# backplane.net
KiCad netlist of a schematic drawn in EAGLE
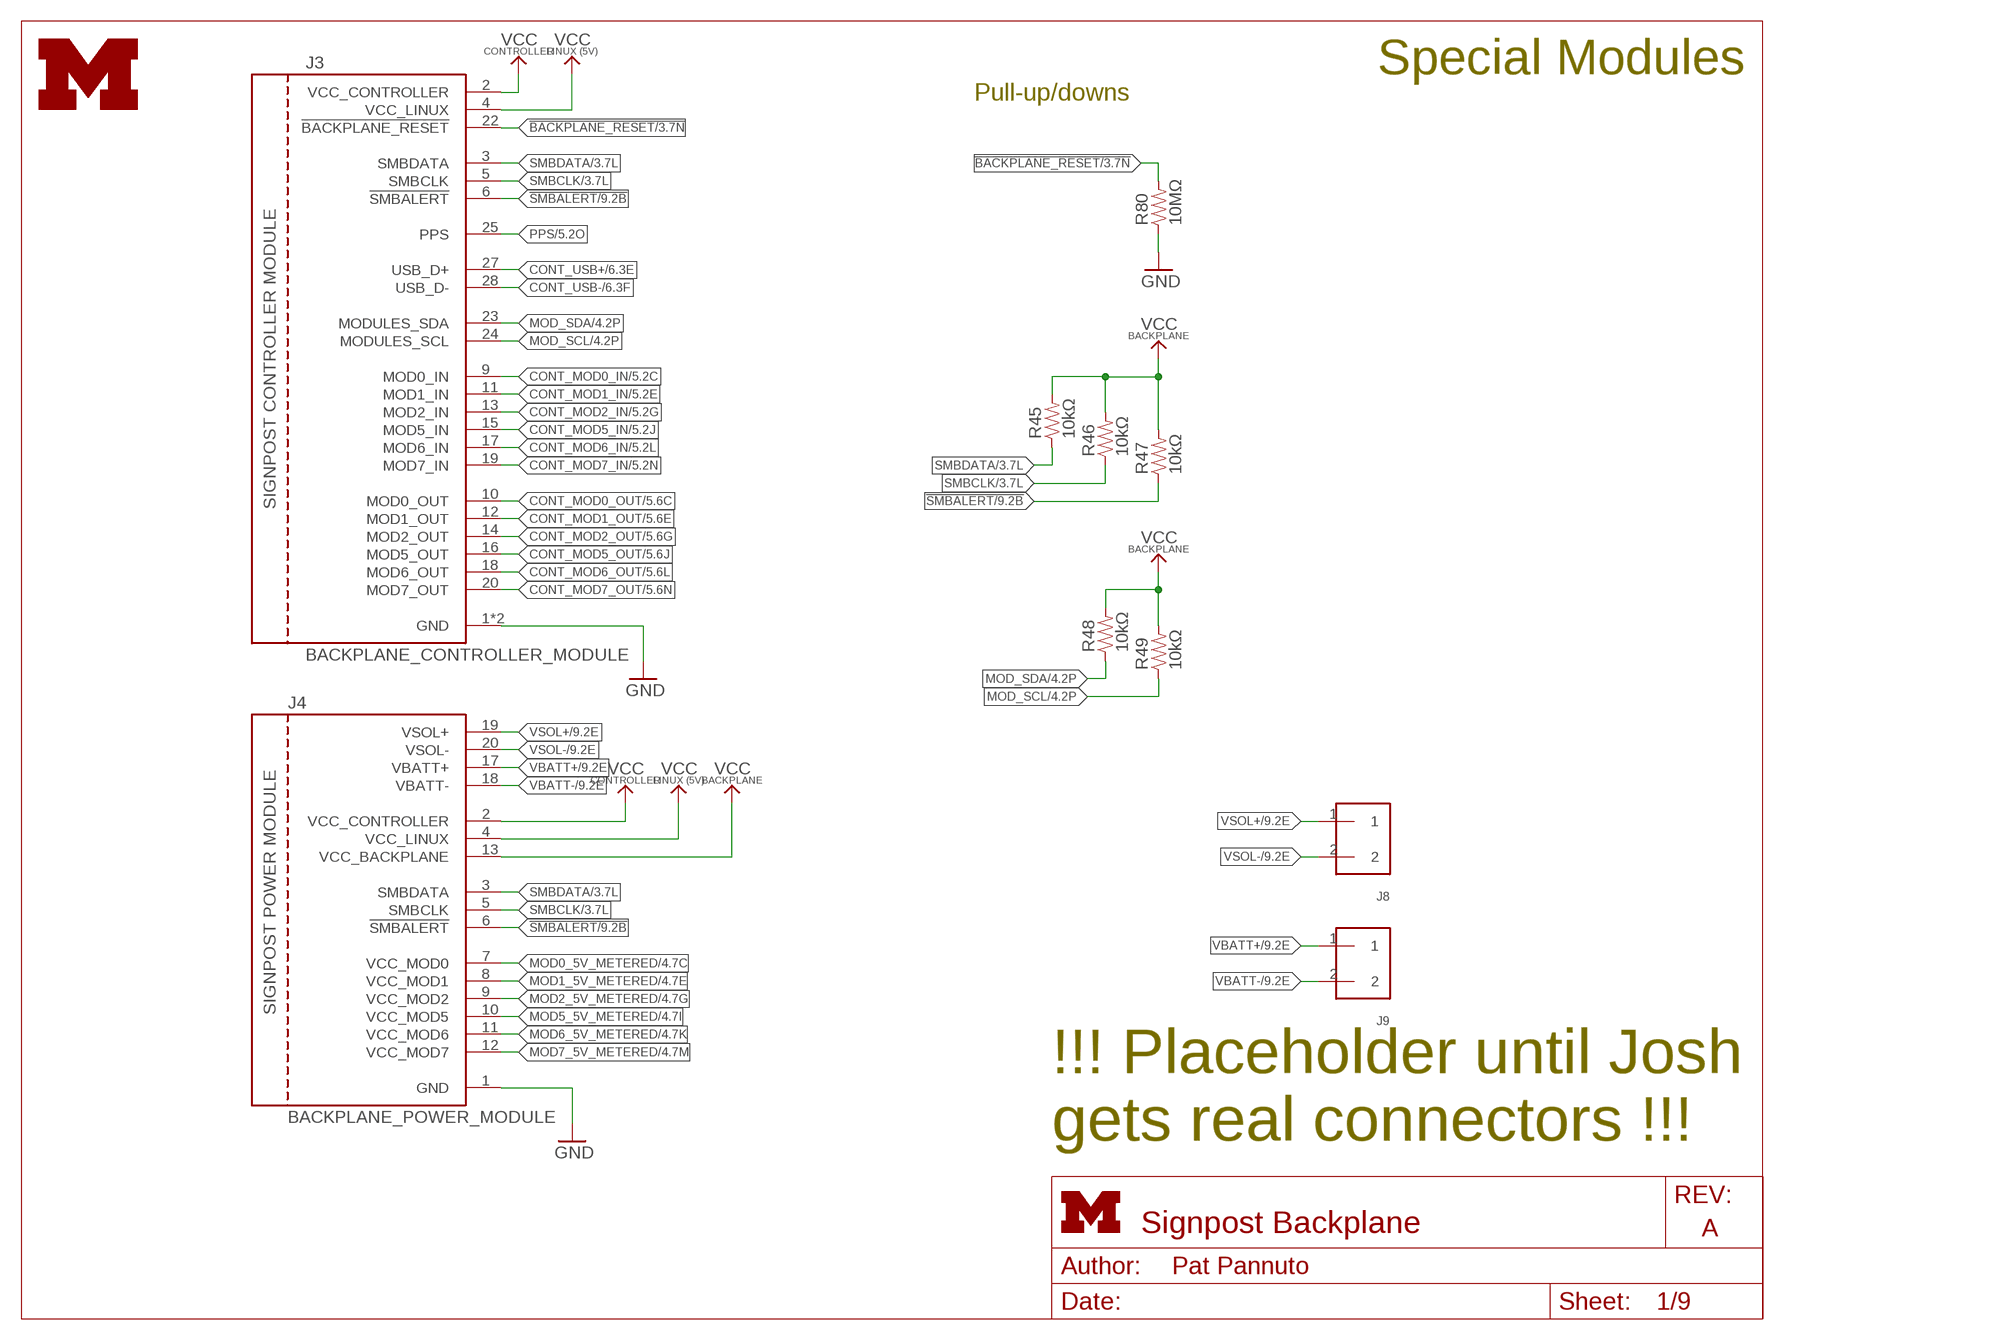
[diagram p0: schematic, sheet 1]
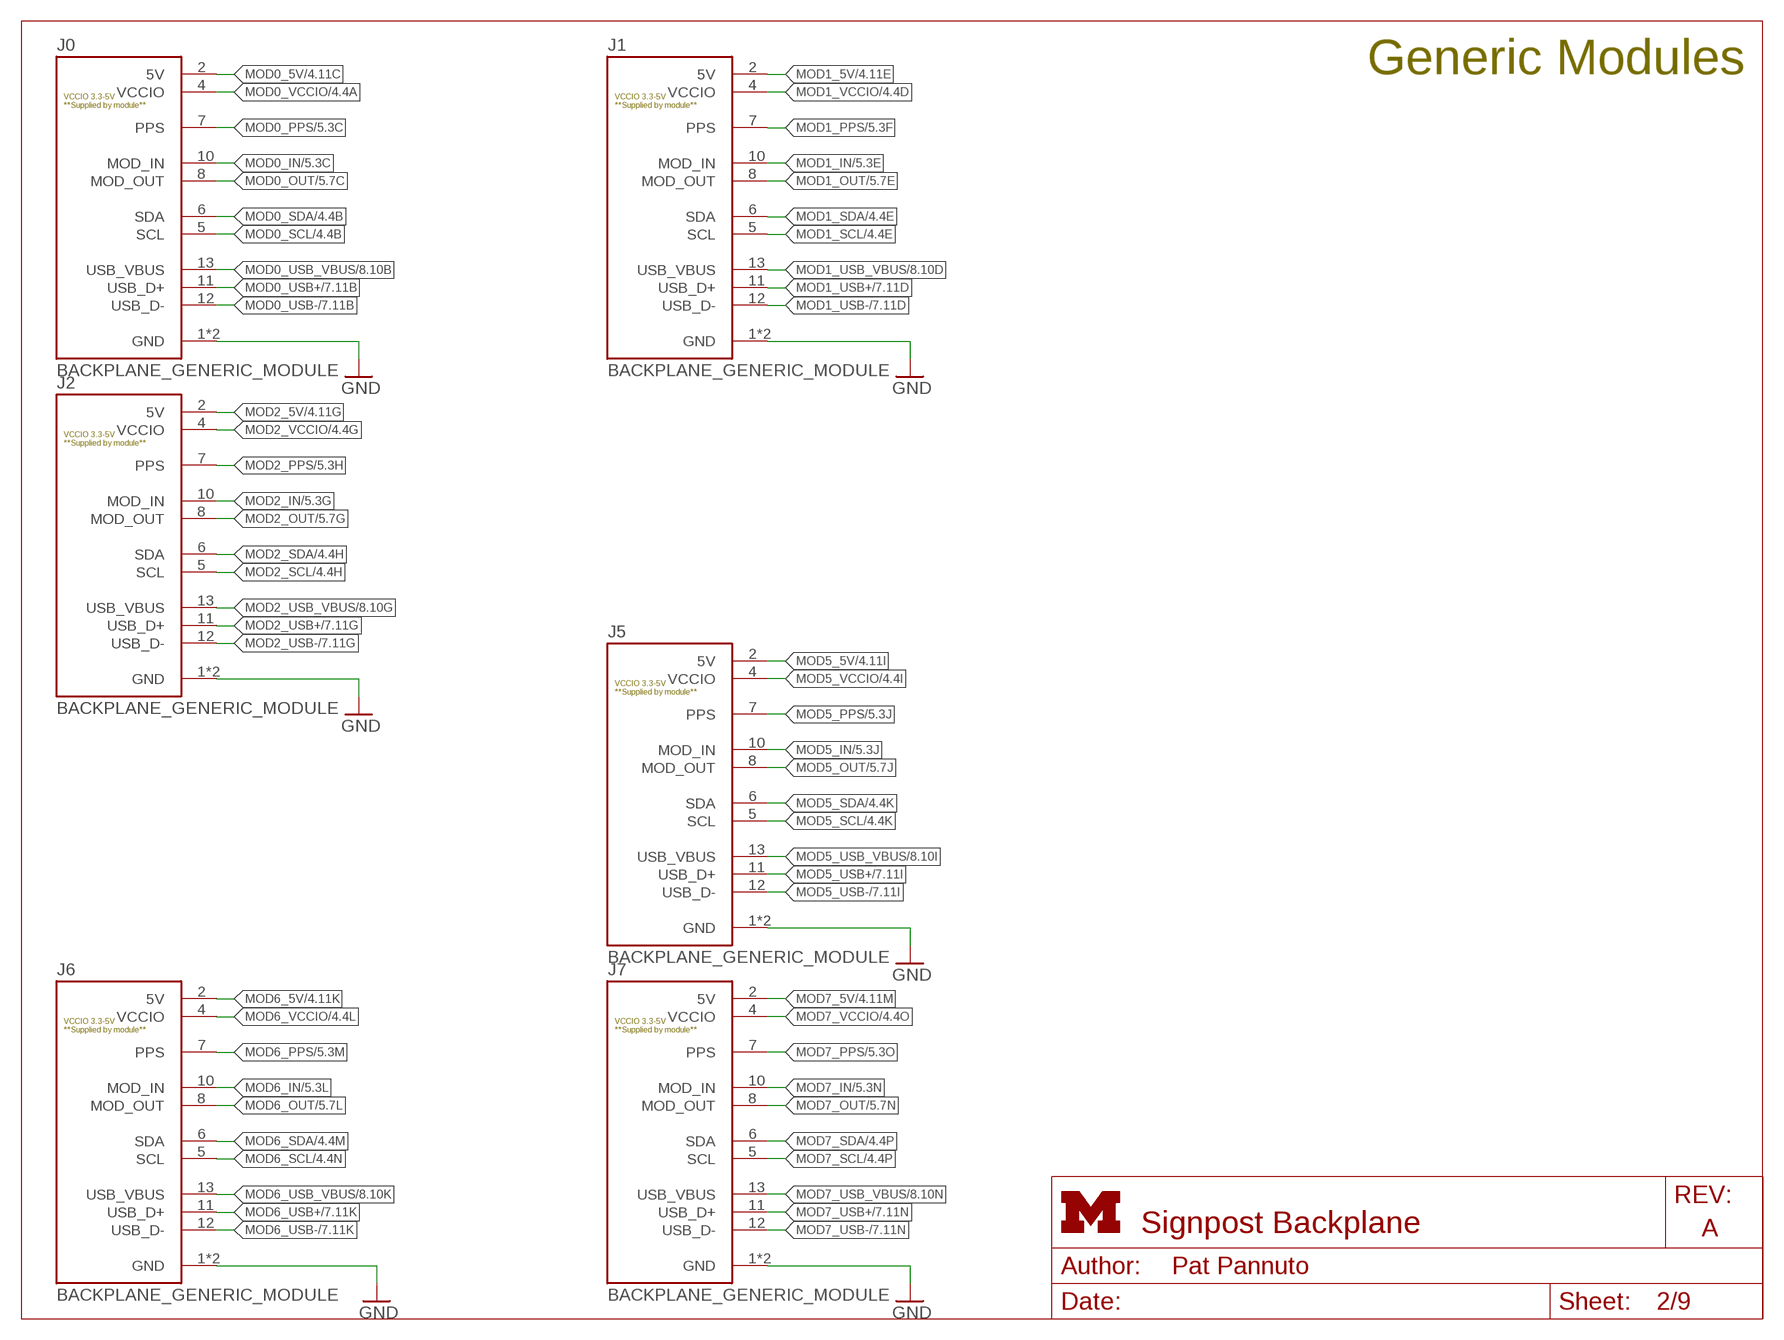
[diagram p1: schematic, sheet 2]
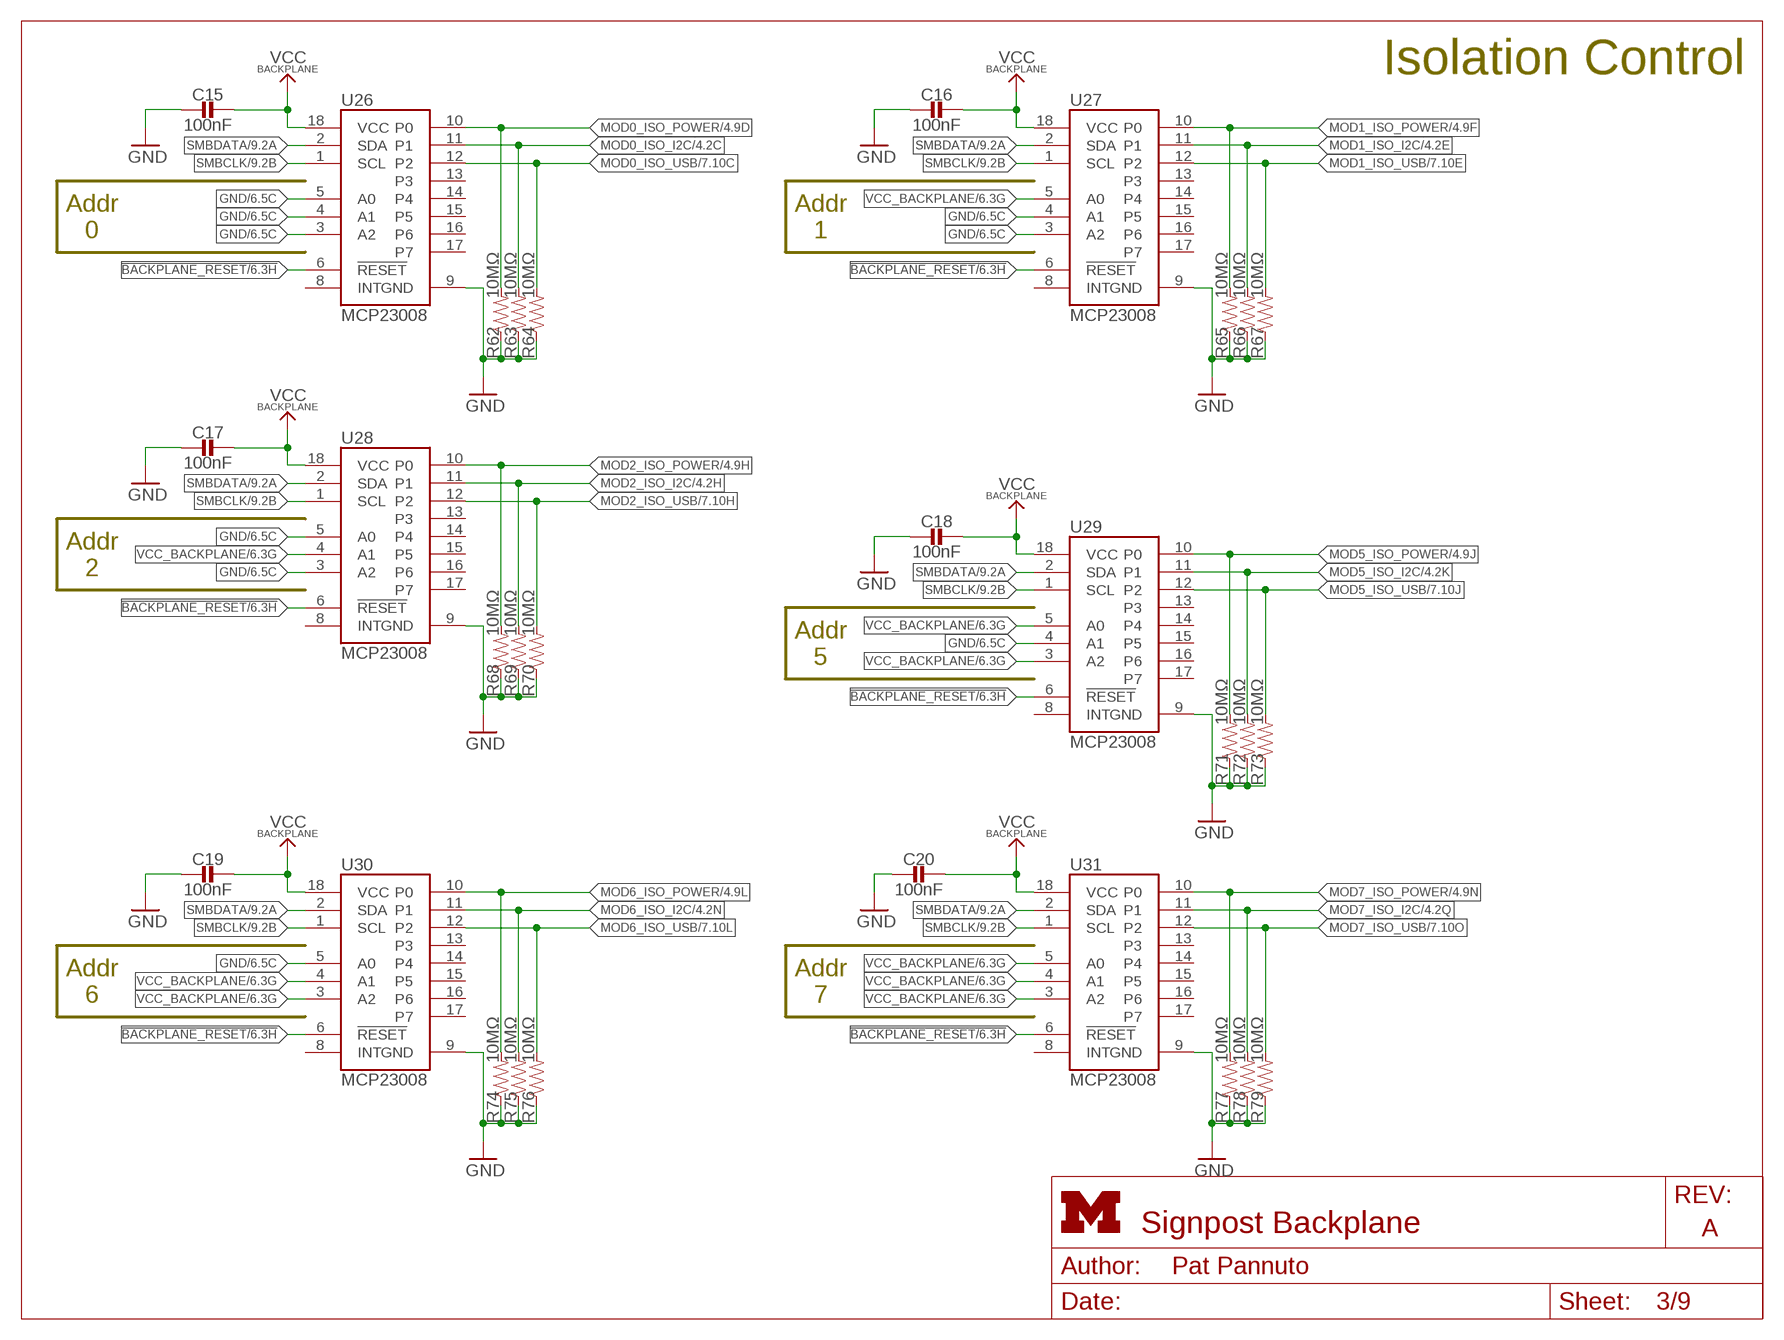
[diagram p2: schematic, sheet 3]
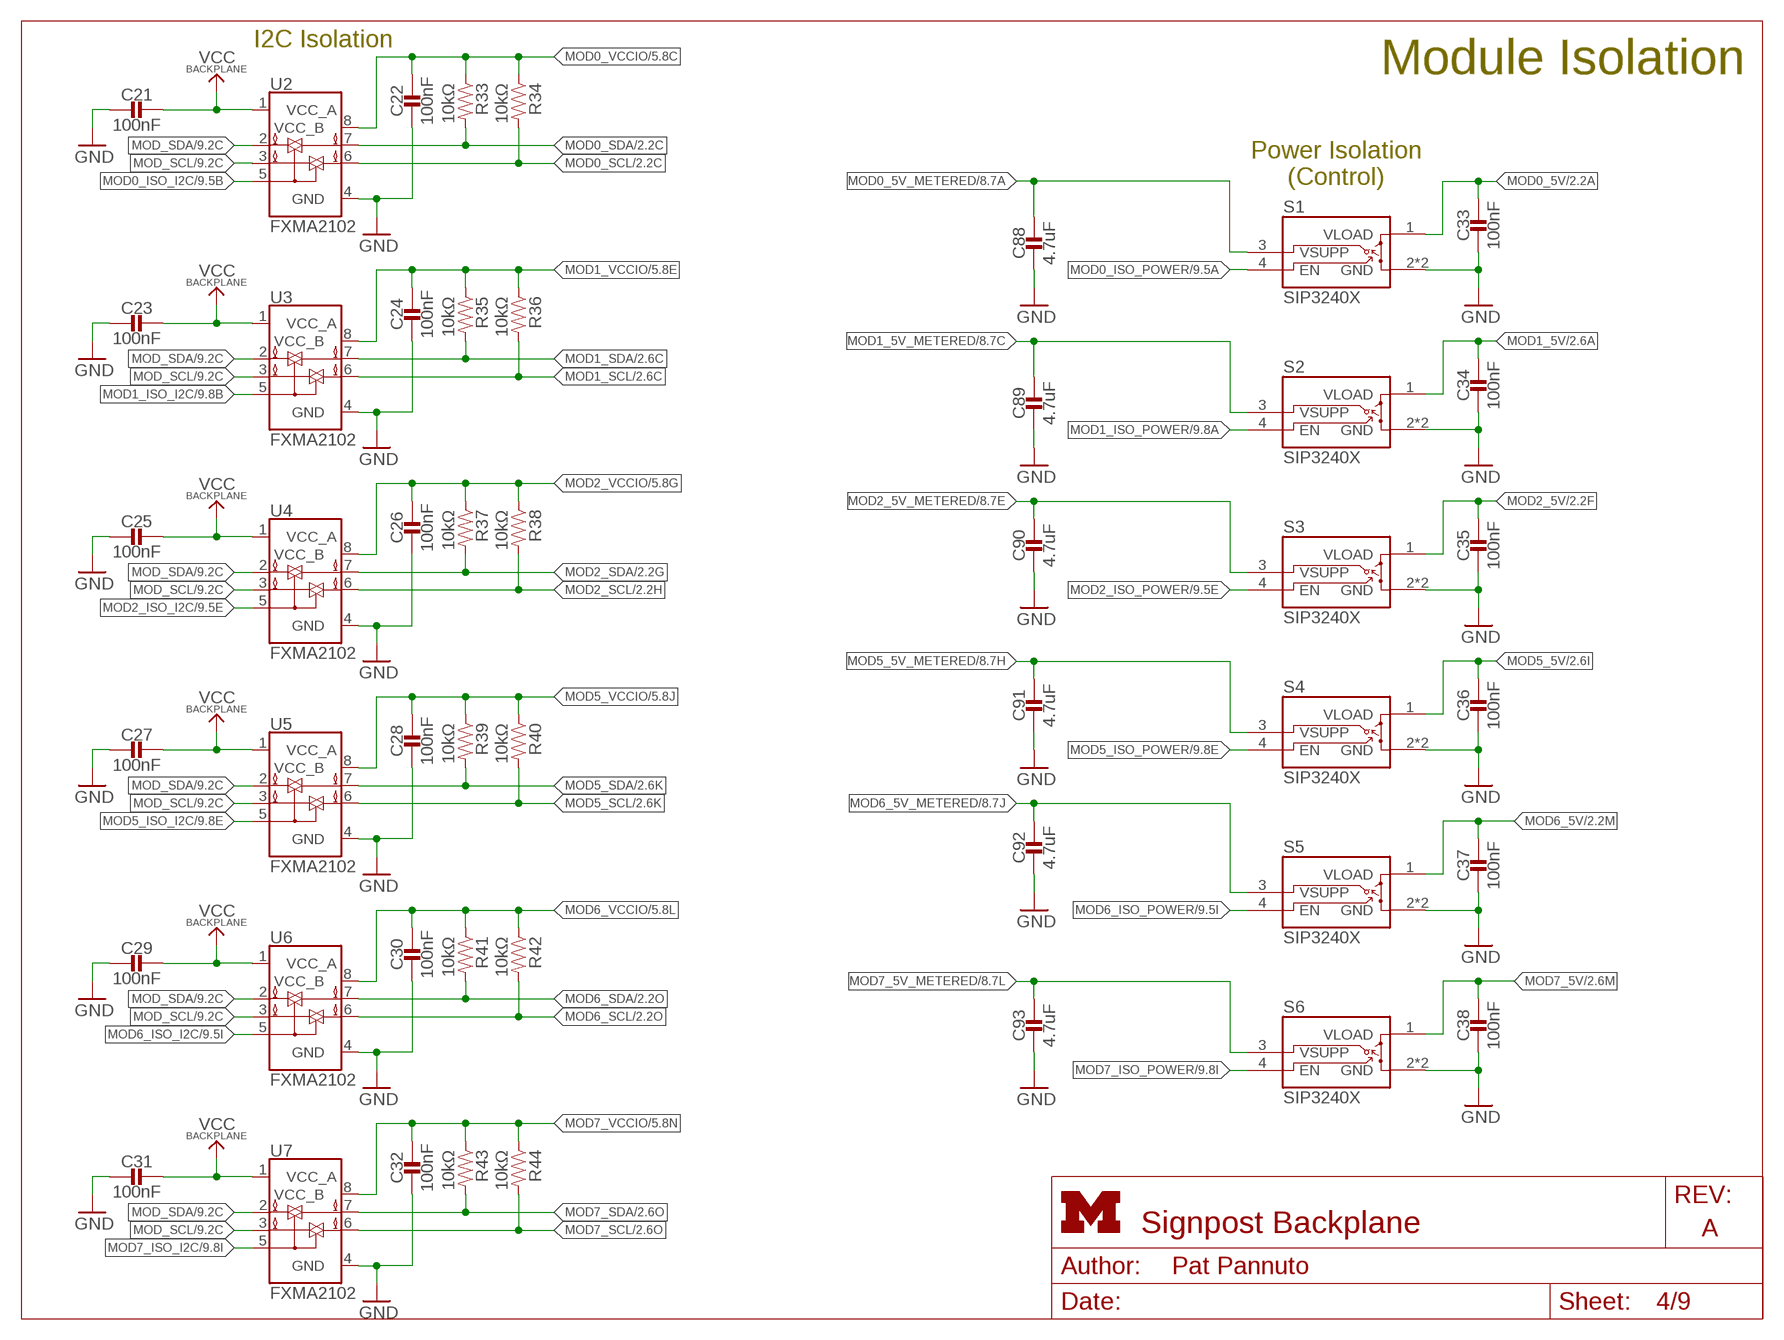
[diagram p3: schematic, sheet 4]
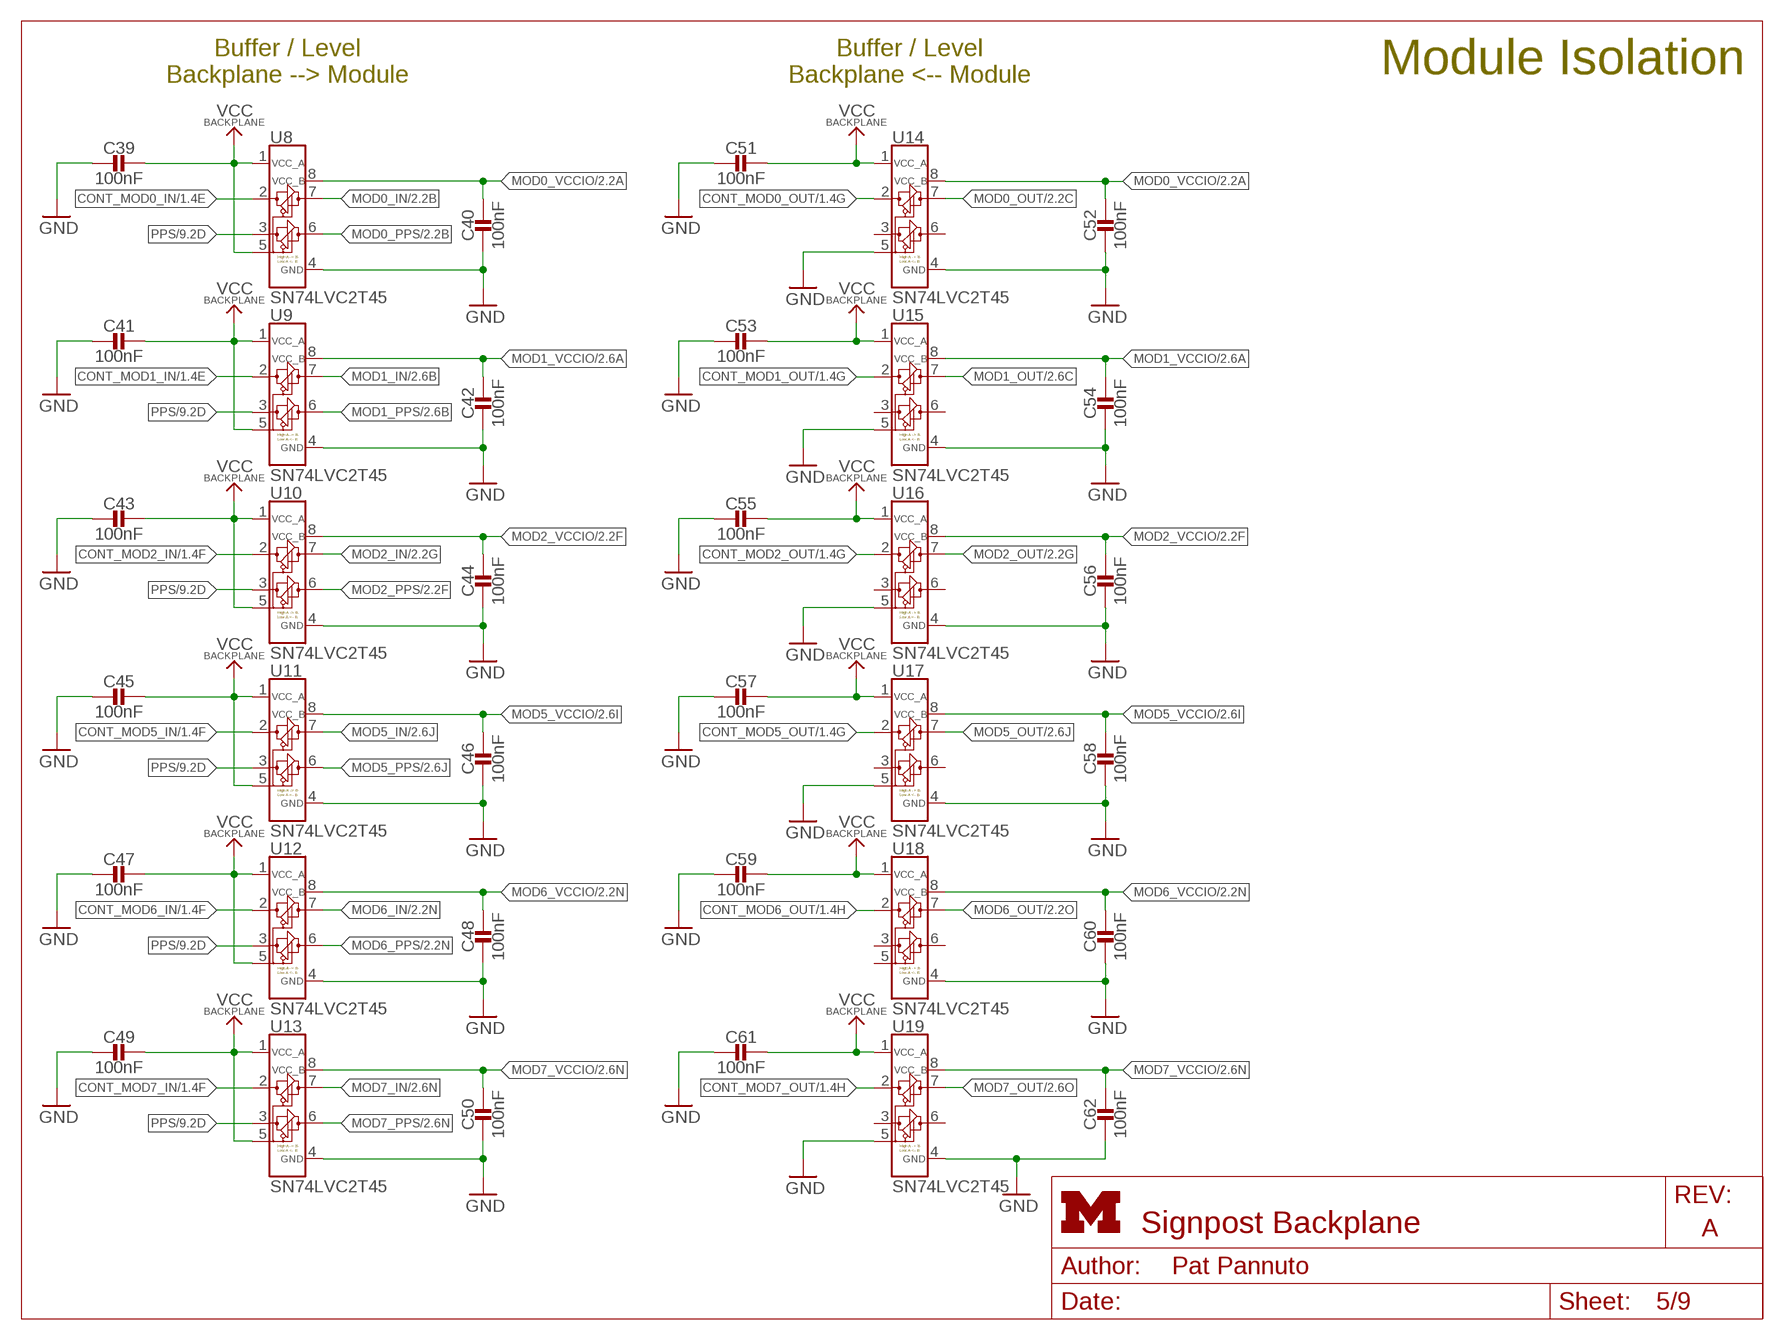
[diagram p4: schematic, sheet 5]
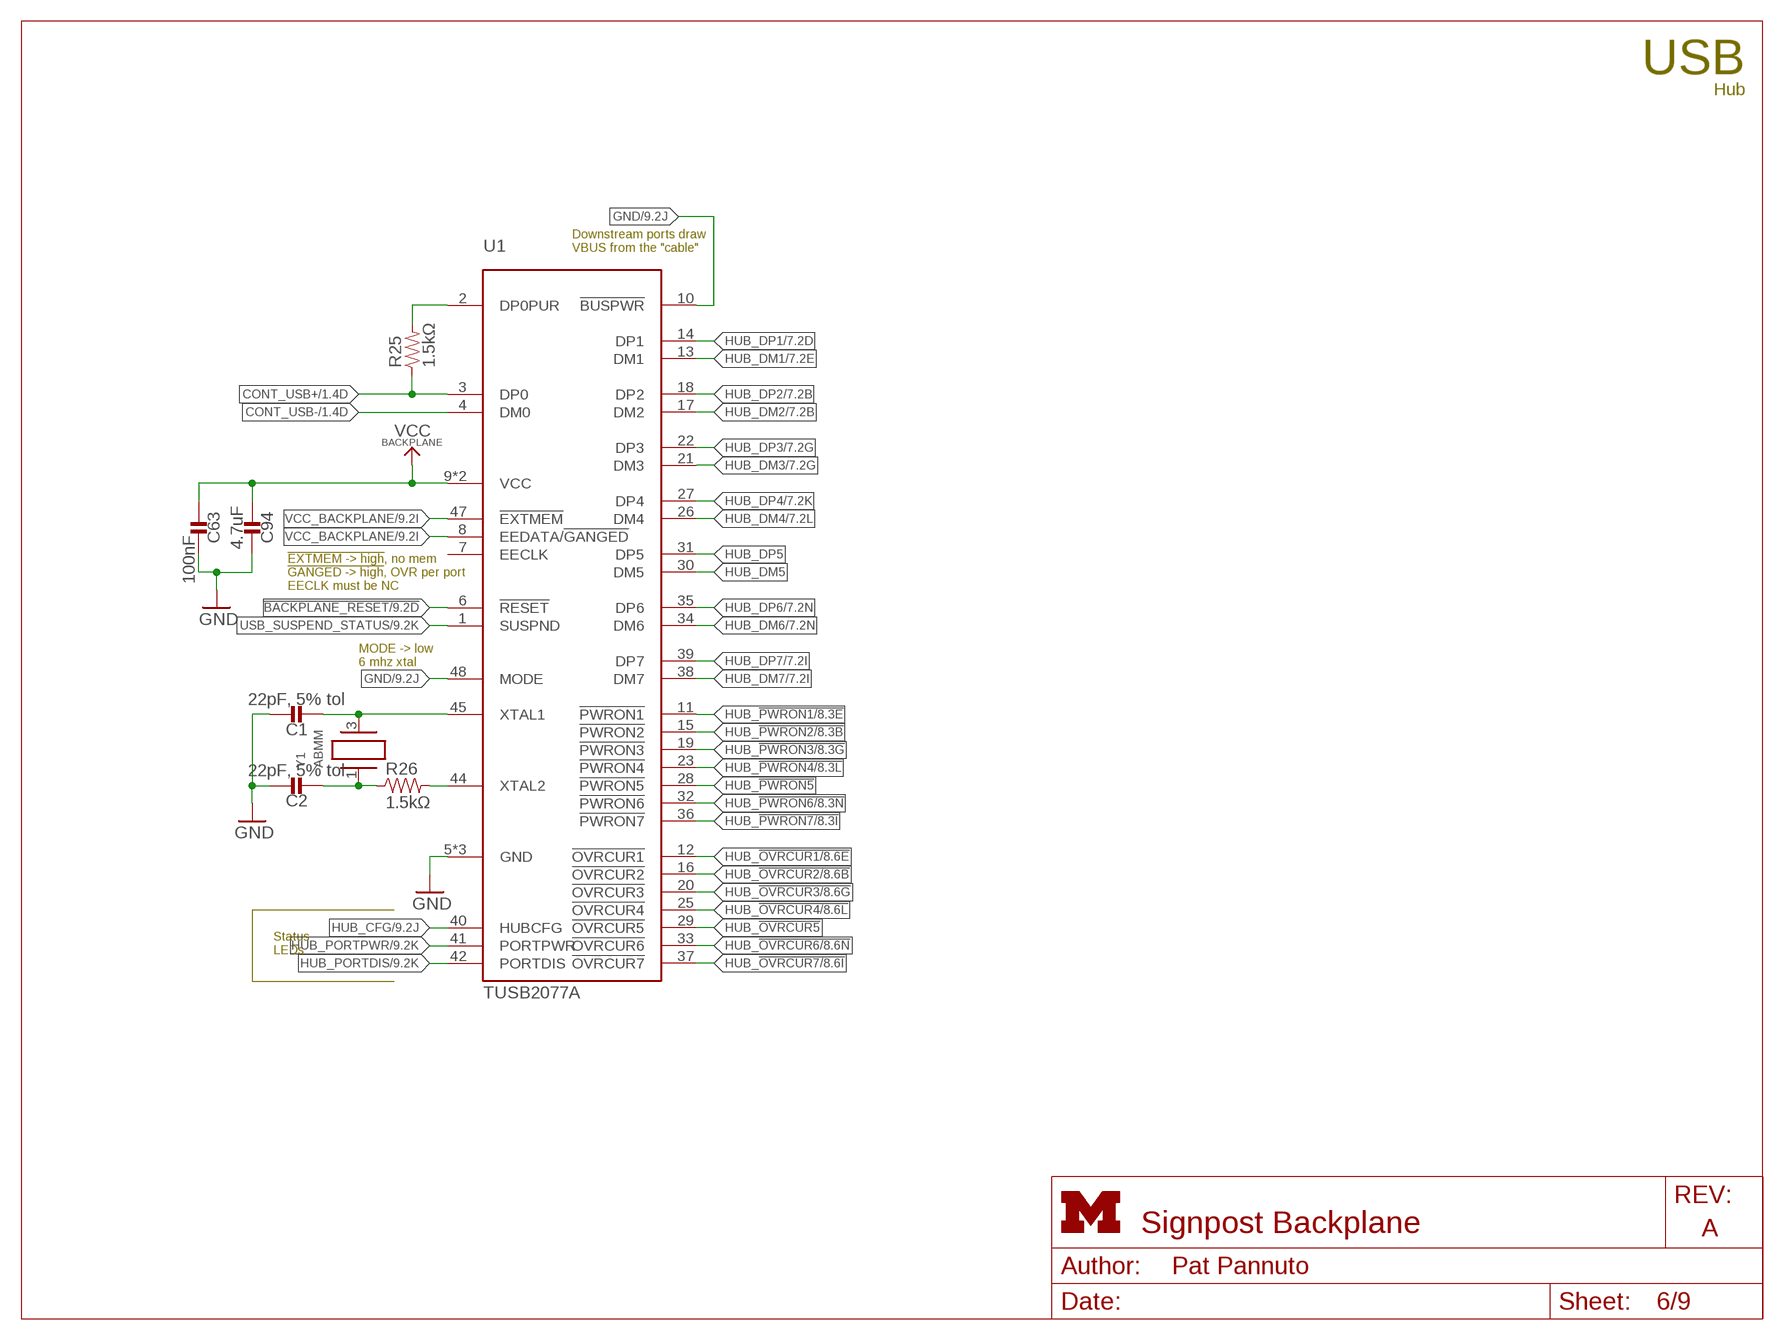
[diagram p5: schematic, sheet 6]
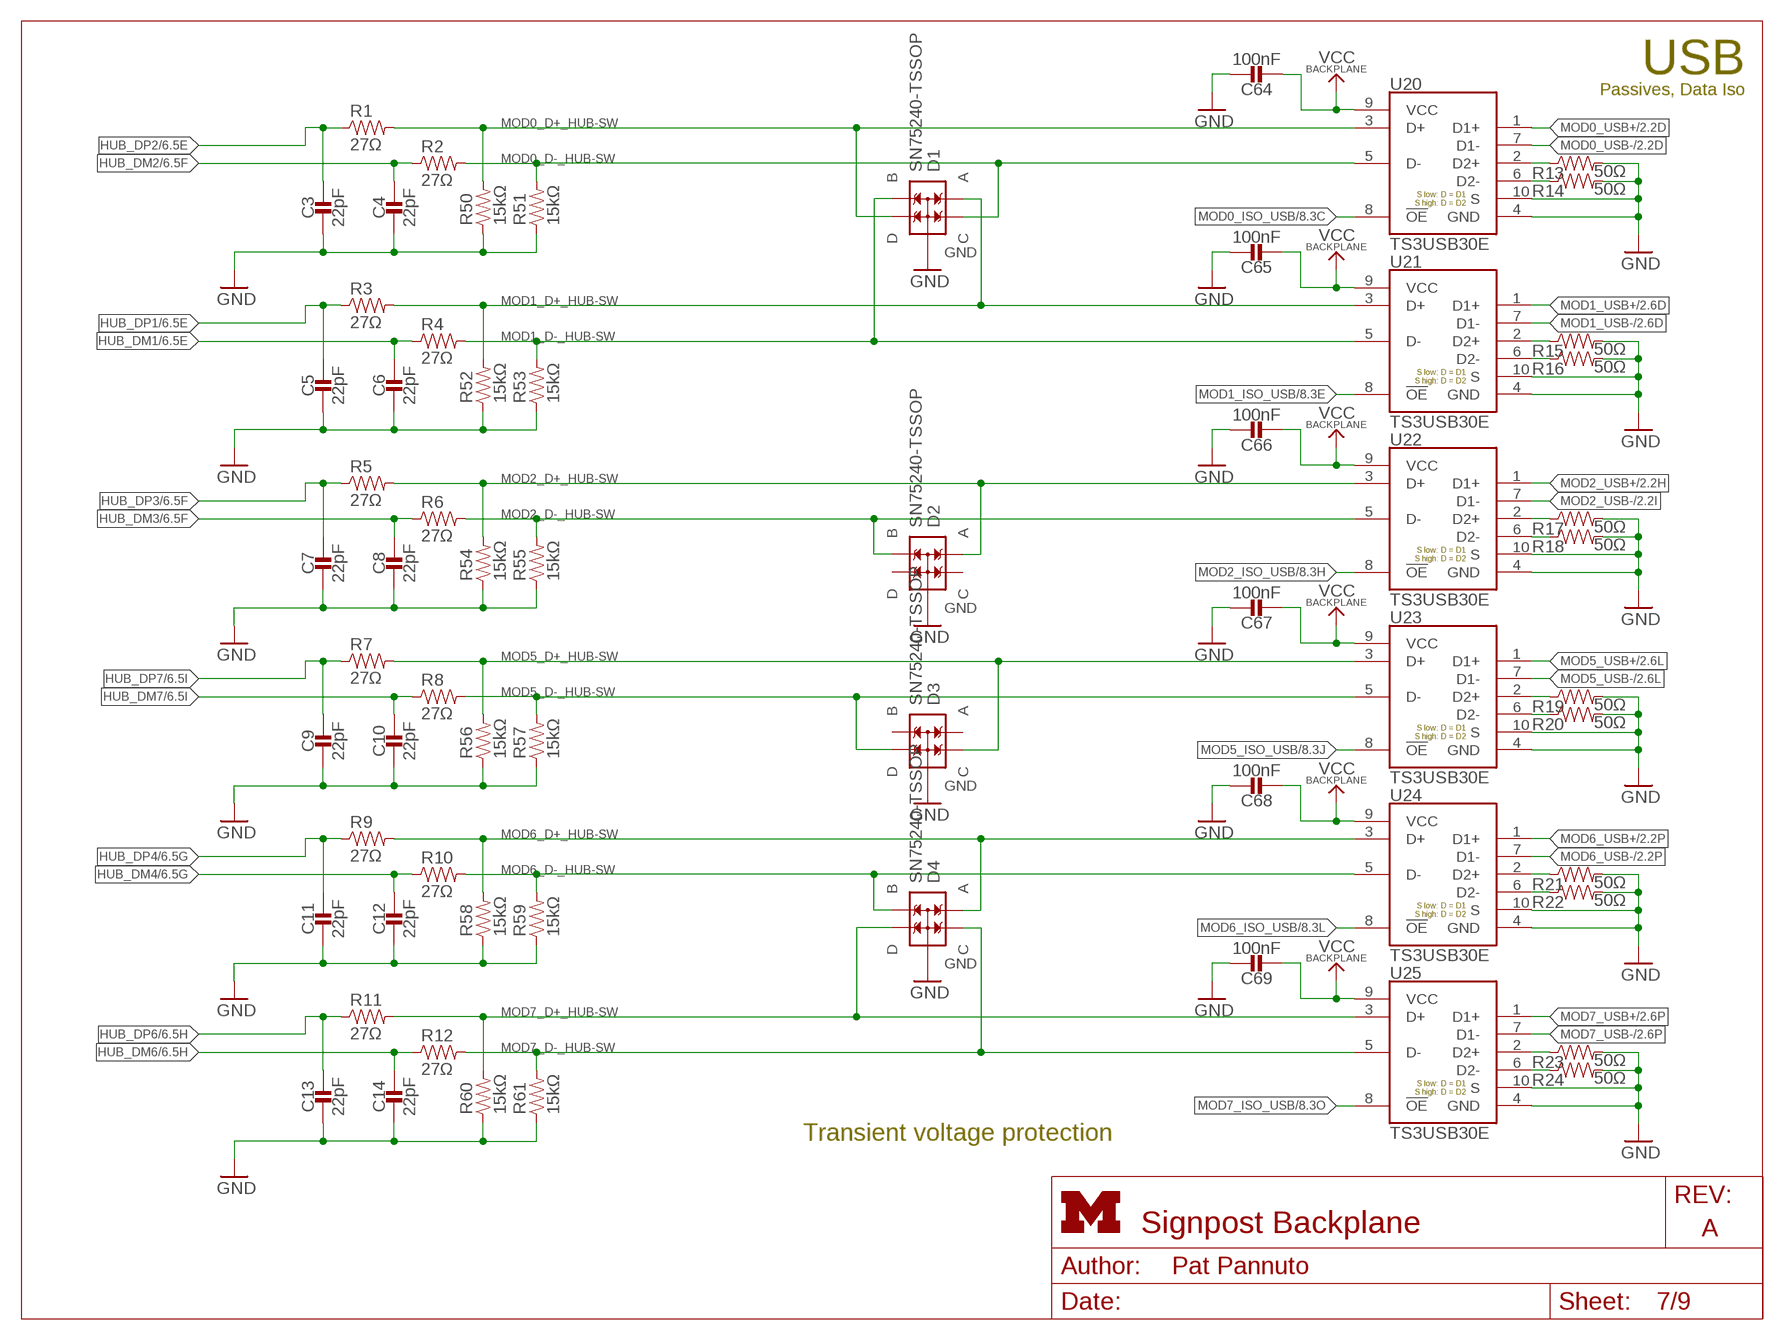
[diagram p6: schematic, sheet 7]
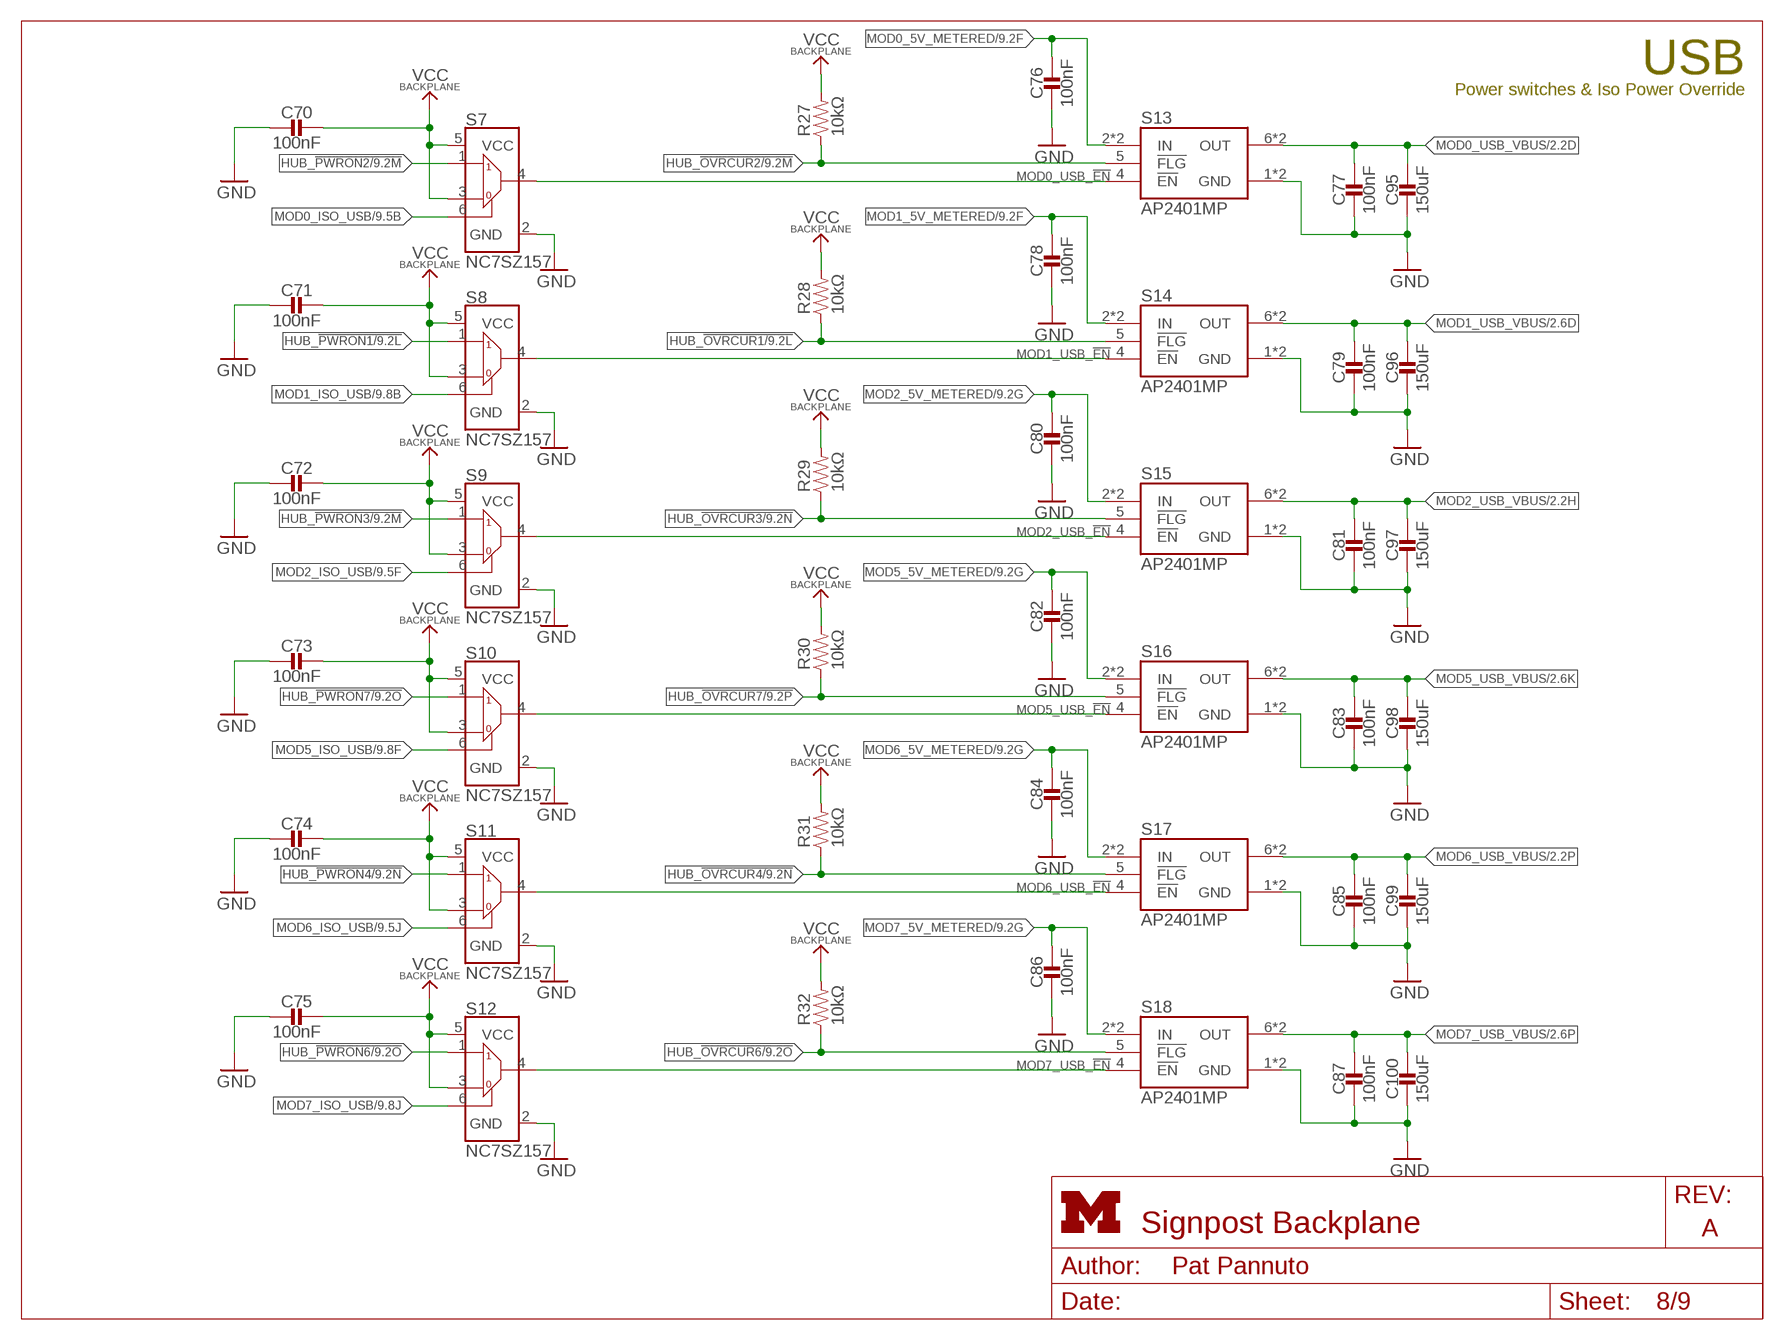
[diagram p7: schematic, sheet 8]
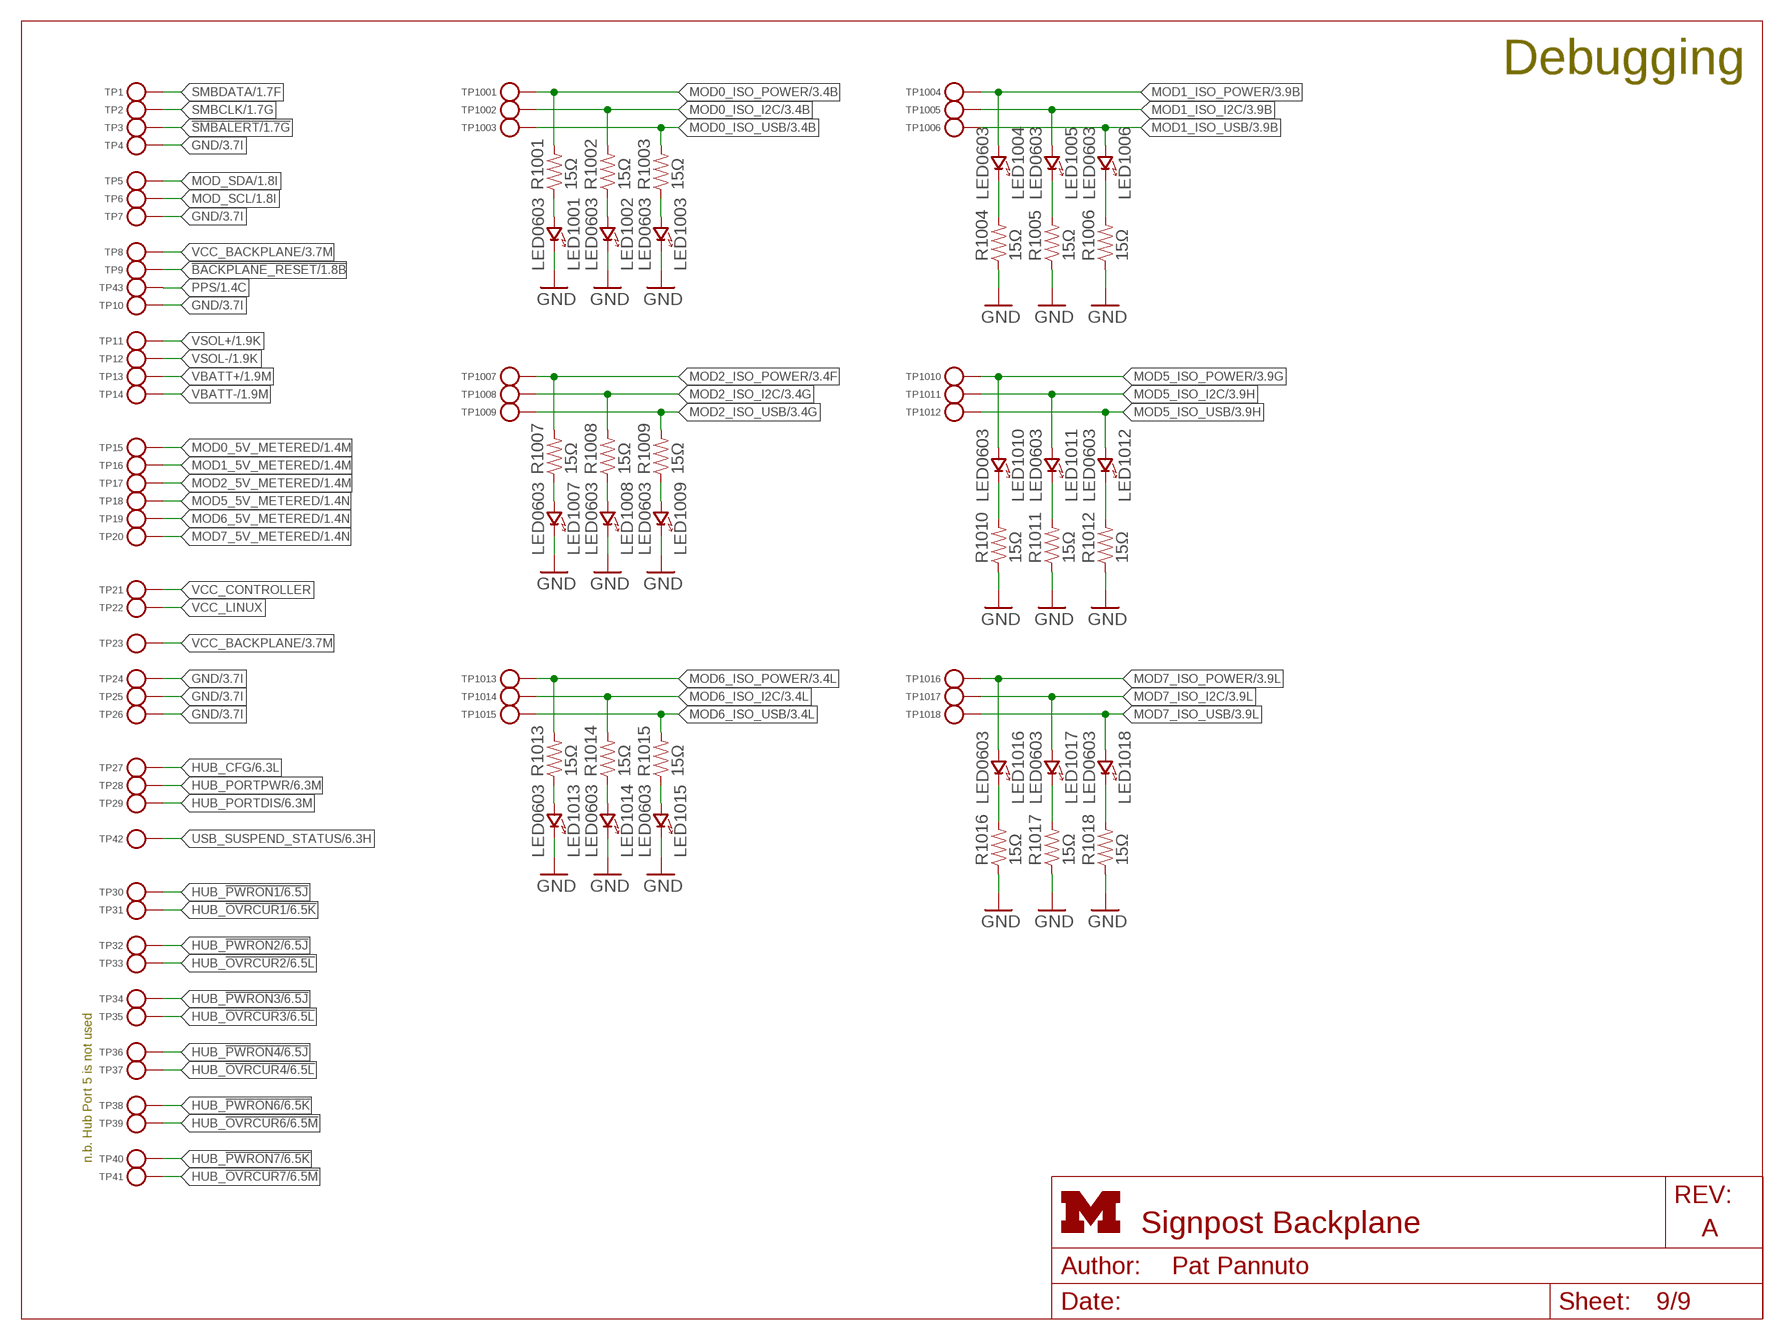
[diagram p8: schematic, sheet 9]

(export (version "E")
  (design (tool "Eeschema 10.0.6"))
  (components
    (comp (ref "C1")
      (value "22pF, 5% tol")
      (footprint "eagle-import:0603_CAP")
      (libsource (lib "eagle-import") (part "CAPACITOR0603_CAP"))
    )
    (comp (ref "C2")
      (value "22pF, 5% tol")
      (footprint "eagle-import:0603_CAP")
      (libsource (lib "eagle-import") (part "CAPACITOR0603_CAP"))
    )
    (comp (ref "C63")
      (value "100nF")
      (footprint "eagle-import:0603_CAP")
      (libsource (lib "eagle-import") (part "CAPACITOR0603_CAP"))
    )
    (comp (ref "C94")
      (value "4.7uF")
      (footprint "eagle-import:0603_CAP")
      (libsource (lib "eagle-import") (part "CAPACITOR0603_CAP"))
    )
    (comp (ref "R25")
      (value "1.5kΩ")
      (footprint "eagle-import:0603-RES")
      (libsource (lib "eagle-import") (part "RESISTOR0603_RES"))
    )
    (comp (ref "R26")
      (value "1.5kΩ")
      (footprint "eagle-import:0603-RES")
      (libsource (lib "eagle-import") (part "RESISTOR0603_RES"))
    )
    (comp (ref "U1")
      (value "TUSB2077A")
      (footprint "eagle-import:LQFP-48")
      (libsource (lib "eagle-import") (part "TUSB2077A"))
    )
    (comp (ref "Y1")
      (value "ABMM")
      (footprint "eagle-import:ABMM")
      (libsource (lib "eagle-import") (part "ABMM"))
    )
    (comp (ref "J0")
      (value "BACKPLANE_GENERIC_MODULE")
      (footprint "eagle-import:BACKPLANE_MODULE_14PIN")
      (libsource (lib "eagle-import") (part "BACKPLANE_GENERIC_MODULE"))
    )
    (comp (ref "J1")
      (value "BACKPLANE_GENERIC_MODULE")
      (footprint "eagle-import:BACKPLANE_MODULE_14PIN")
      (libsource (lib "eagle-import") (part "BACKPLANE_GENERIC_MODULE"))
    )
    (comp (ref "J2")
      (value "BACKPLANE_GENERIC_MODULE")
      (footprint "eagle-import:BACKPLANE_MODULE_14PIN")
      (libsource (lib "eagle-import") (part "BACKPLANE_GENERIC_MODULE"))
    )
    (comp (ref "J5")
      (value "BACKPLANE_GENERIC_MODULE")
      (footprint "eagle-import:BACKPLANE_MODULE_14PIN")
      (libsource (lib "eagle-import") (part "BACKPLANE_GENERIC_MODULE"))
    )
    (comp (ref "J6")
      (value "BACKPLANE_GENERIC_MODULE")
      (footprint "eagle-import:BACKPLANE_MODULE_14PIN")
      (libsource (lib "eagle-import") (part "BACKPLANE_GENERIC_MODULE"))
    )
    (comp (ref "J7")
      (value "BACKPLANE_GENERIC_MODULE")
      (footprint "eagle-import:BACKPLANE_MODULE_14PIN")
      (libsource (lib "eagle-import") (part "BACKPLANE_GENERIC_MODULE"))
    )
    (comp (ref "C15")
      (value "100nF")
      (footprint "eagle-import:0603_CAP")
      (libsource (lib "eagle-import") (part "CAPACITOR0603_CAP"))
    )
    (comp (ref "C16")
      (value "100nF")
      (footprint "eagle-import:0603_CAP")
      (libsource (lib "eagle-import") (part "CAPACITOR0603_CAP"))
    )
    (comp (ref "C17")
      (value "100nF")
      (footprint "eagle-import:0603_CAP")
      (libsource (lib "eagle-import") (part "CAPACITOR0603_CAP"))
    )
    (comp (ref "C18")
      (value "100nF")
      (footprint "eagle-import:0603_CAP")
      (libsource (lib "eagle-import") (part "CAPACITOR0603_CAP"))
    )
    (comp (ref "C19")
      (value "100nF")
      (footprint "eagle-import:0603_CAP")
      (libsource (lib "eagle-import") (part "CAPACITOR0603_CAP"))
    )
    (comp (ref "C20")
      (value "100nF")
      (footprint "eagle-import:0603_CAP")
      (libsource (lib "eagle-import") (part "CAPACITOR0603_CAP"))
    )
    (comp (ref "R62")
      (value "10MΩ")
      (footprint "eagle-import:0603-RES")
      (libsource (lib "eagle-import") (part "RESISTOR0603_RES"))
    )
    (comp (ref "R63")
      (value "10MΩ")
      (footprint "eagle-import:0603-RES")
      (libsource (lib "eagle-import") (part "RESISTOR0603_RES"))
    )
    (comp (ref "R64")
      (value "10MΩ")
      (footprint "eagle-import:0603-RES")
      (libsource (lib "eagle-import") (part "RESISTOR0603_RES"))
    )
    (comp (ref "R65")
      (value "10MΩ")
      (footprint "eagle-import:0603-RES")
      (libsource (lib "eagle-import") (part "RESISTOR0603_RES"))
    )
    (comp (ref "R66")
      (value "10MΩ")
      (footprint "eagle-import:0603-RES")
      (libsource (lib "eagle-import") (part "RESISTOR0603_RES"))
    )
    (comp (ref "R67")
      (value "10MΩ")
      (footprint "eagle-import:0603-RES")
      (libsource (lib "eagle-import") (part "RESISTOR0603_RES"))
    )
    (comp (ref "R68")
      (value "10MΩ")
      (footprint "eagle-import:0603-RES")
      (libsource (lib "eagle-import") (part "RESISTOR0603_RES"))
    )
    (comp (ref "R69")
      (value "10MΩ")
      (footprint "eagle-import:0603-RES")
      (libsource (lib "eagle-import") (part "RESISTOR0603_RES"))
    )
    (comp (ref "R70")
      (value "10MΩ")
      (footprint "eagle-import:0603-RES")
      (libsource (lib "eagle-import") (part "RESISTOR0603_RES"))
    )
    (comp (ref "R71")
      (value "10MΩ")
      (footprint "eagle-import:0603-RES")
      (libsource (lib "eagle-import") (part "RESISTOR0603_RES"))
    )
    (comp (ref "R72")
      (value "10MΩ")
      (footprint "eagle-import:0603-RES")
      (libsource (lib "eagle-import") (part "RESISTOR0603_RES"))
    )
    (comp (ref "R73")
      (value "10MΩ")
      (footprint "eagle-import:0603-RES")
      (libsource (lib "eagle-import") (part "RESISTOR0603_RES"))
    )
    (comp (ref "R74")
      (value "10MΩ")
      (footprint "eagle-import:0603-RES")
      (libsource (lib "eagle-import") (part "RESISTOR0603_RES"))
    )
    (comp (ref "R75")
      (value "10MΩ")
      (footprint "eagle-import:0603-RES")
      (libsource (lib "eagle-import") (part "RESISTOR0603_RES"))
    )
    (comp (ref "R76")
      (value "10MΩ")
      (footprint "eagle-import:0603-RES")
      (libsource (lib "eagle-import") (part "RESISTOR0603_RES"))
    )
    (comp (ref "R77")
      (value "10MΩ")
      (footprint "eagle-import:0603-RES")
      (libsource (lib "eagle-import") (part "RESISTOR0603_RES"))
    )
    (comp (ref "R78")
      (value "10MΩ")
      (footprint "eagle-import:0603-RES")
      (libsource (lib "eagle-import") (part "RESISTOR0603_RES"))
    )
    (comp (ref "R79")
      (value "10MΩ")
      (footprint "eagle-import:0603-RES")
      (libsource (lib "eagle-import") (part "RESISTOR0603_RES"))
    )
    (comp (ref "U26")
      (value "MCP23008")
      (footprint "eagle-import:SOIC-18")
      (libsource (lib "eagle-import") (part "MCP23008"))
    )
    (comp (ref "U27")
      (value "MCP23008")
      (footprint "eagle-import:SOIC-18")
      (libsource (lib "eagle-import") (part "MCP23008"))
    )
    (comp (ref "U28")
      (value "MCP23008")
      (footprint "eagle-import:SOIC-18")
      (libsource (lib "eagle-import") (part "MCP23008"))
    )
    (comp (ref "U29")
      (value "MCP23008")
      (footprint "eagle-import:SOIC-18")
      (libsource (lib "eagle-import") (part "MCP23008"))
    )
    (comp (ref "U30")
      (value "MCP23008")
      (footprint "eagle-import:SOIC-18")
      (libsource (lib "eagle-import") (part "MCP23008"))
    )
    (comp (ref "U31")
      (value "MCP23008")
      (footprint "eagle-import:SOIC-18")
      (libsource (lib "eagle-import") (part "MCP23008"))
    )
    (comp (ref "J3")
      (value "BACKPLANE_CONTROLLER_MODULE")
      (footprint "eagle-import:BACKPLANE_MODULE_20PIN_10PIN")
      (libsource (lib "eagle-import") (part "BACKPLANE_CONTROLLER_MODULE"))
    )
    (comp (ref "J4")
      (value "BACKPLANE_POWER_MODULE")
      (footprint "eagle-import:BACKPLANE_MODULE_20PIN")
      (libsource (lib "eagle-import") (part "BACKPLANE_POWER_MODULE"))
    )
    (comp (ref "J8")
      (value "SCREW_TERMINAL")
      (footprint "eagle-import:PHEONIX-1935161")
      (libsource (lib "eagle-import") (part "SCREW_TERMINAL"))
    )
    (comp (ref "J9")
      (value "SCREW_TERMINAL")
      (footprint "eagle-import:PHEONIX-1935161")
      (libsource (lib "eagle-import") (part "SCREW_TERMINAL"))
    )
    (comp (ref "LOGO1")
      (value "UMICH_SOLID_GIANT")
      (footprint "eagle-import:UMICH_SOLID_1000MIL")
      (libsource (lib "eagle-import") (part "UMICH_SOLID_GIANT"))
    )
    (comp (ref "R45")
      (value "10kΩ")
      (footprint "eagle-import:0603-RES")
      (libsource (lib "eagle-import") (part "RESISTOR0603_RES"))
    )
    (comp (ref "R46")
      (value "10kΩ")
      (footprint "eagle-import:0603-RES")
      (libsource (lib "eagle-import") (part "RESISTOR0603_RES"))
    )
    (comp (ref "R47")
      (value "10kΩ")
      (footprint "eagle-import:0603-RES")
      (libsource (lib "eagle-import") (part "RESISTOR0603_RES"))
    )
    (comp (ref "R48")
      (value "10kΩ")
      (footprint "eagle-import:0603-RES")
      (libsource (lib "eagle-import") (part "RESISTOR0603_RES"))
    )
    (comp (ref "R49")
      (value "10kΩ")
      (footprint "eagle-import:0603-RES")
      (libsource (lib "eagle-import") (part "RESISTOR0603_RES"))
    )
    (comp (ref "R80")
      (value "10MΩ")
      (footprint "eagle-import:0603-RES")
      (libsource (lib "eagle-import") (part "RESISTOR0603_RES"))
    )
    (comp (ref "C21")
      (value "100nF")
      (footprint "eagle-import:0603_CAP")
      (libsource (lib "eagle-import") (part "CAPACITOR0603_CAP"))
    )
    (comp (ref "C22")
      (value "100nF")
      (footprint "eagle-import:0603_CAP")
      (libsource (lib "eagle-import") (part "CAPACITOR0603_CAP"))
    )
    (comp (ref "C23")
      (value "100nF")
      (footprint "eagle-import:0603_CAP")
      (libsource (lib "eagle-import") (part "CAPACITOR0603_CAP"))
    )
    (comp (ref "C24")
      (value "100nF")
      (footprint "eagle-import:0603_CAP")
      (libsource (lib "eagle-import") (part "CAPACITOR0603_CAP"))
    )
    (comp (ref "C25")
      (value "100nF")
      (footprint "eagle-import:0603_CAP")
      (libsource (lib "eagle-import") (part "CAPACITOR0603_CAP"))
    )
    (comp (ref "C26")
      (value "100nF")
      (footprint "eagle-import:0603_CAP")
      (libsource (lib "eagle-import") (part "CAPACITOR0603_CAP"))
    )
    (comp (ref "C27")
      (value "100nF")
      (footprint "eagle-import:0603_CAP")
      (libsource (lib "eagle-import") (part "CAPACITOR0603_CAP"))
    )
    (comp (ref "C28")
      (value "100nF")
      (footprint "eagle-import:0603_CAP")
      (libsource (lib "eagle-import") (part "CAPACITOR0603_CAP"))
    )
    (comp (ref "C29")
      (value "100nF")
      (footprint "eagle-import:0603_CAP")
      (libsource (lib "eagle-import") (part "CAPACITOR0603_CAP"))
    )
    (comp (ref "C30")
      (value "100nF")
      (footprint "eagle-import:0603_CAP")
      (libsource (lib "eagle-import") (part "CAPACITOR0603_CAP"))
    )
    (comp (ref "C31")
      (value "100nF")
      (footprint "eagle-import:0603_CAP")
      (libsource (lib "eagle-import") (part "CAPACITOR0603_CAP"))
    )
    (comp (ref "C32")
      (value "100nF")
      (footprint "eagle-import:0603_CAP")
      (libsource (lib "eagle-import") (part "CAPACITOR0603_CAP"))
    )
    (comp (ref "C33")
      (value "100nF")
      (footprint "eagle-import:0603_CAP")
      (libsource (lib "eagle-import") (part "CAPACITOR0603_CAP"))
    )
    (comp (ref "C34")
      (value "100nF")
      (footprint "eagle-import:0603_CAP")
      (libsource (lib "eagle-import") (part "CAPACITOR0603_CAP"))
    )
    (comp (ref "C35")
      (value "100nF")
      (footprint "eagle-import:0603_CAP")
      (libsource (lib "eagle-import") (part "CAPACITOR0603_CAP"))
    )
    (comp (ref "C36")
      (value "100nF")
      (footprint "eagle-import:0603_CAP")
      (libsource (lib "eagle-import") (part "CAPACITOR0603_CAP"))
    )
    (comp (ref "C37")
      (value "100nF")
      (footprint "eagle-import:0603_CAP")
      (libsource (lib "eagle-import") (part "CAPACITOR0603_CAP"))
    )
    (comp (ref "C38")
      (value "100nF")
      (footprint "eagle-import:0603_CAP")
      (libsource (lib "eagle-import") (part "CAPACITOR0603_CAP"))
    )
    (comp (ref "C88")
      (value "4.7uF")
      (footprint "eagle-import:0603_CAP")
      (libsource (lib "eagle-import") (part "CAPACITOR0603_CAP"))
    )
    (comp (ref "C89")
      (value "4.7uF")
      (footprint "eagle-import:0603_CAP")
      (libsource (lib "eagle-import") (part "CAPACITOR0603_CAP"))
    )
    (comp (ref "C90")
      (value "4.7uF")
      (footprint "eagle-import:0603_CAP")
      (libsource (lib "eagle-import") (part "CAPACITOR0603_CAP"))
    )
    (comp (ref "C91")
      (value "4.7uF")
      (footprint "eagle-import:0603_CAP")
      (libsource (lib "eagle-import") (part "CAPACITOR0603_CAP"))
    )
    (comp (ref "C92")
      (value "4.7uF")
      (footprint "eagle-import:0603_CAP")
      (libsource (lib "eagle-import") (part "CAPACITOR0603_CAP"))
    )
    (comp (ref "C93")
      (value "4.7uF")
      (footprint "eagle-import:0603_CAP")
      (libsource (lib "eagle-import") (part "CAPACITOR0603_CAP"))
    )
    (comp (ref "R33")
      (value "10kΩ")
      (footprint "eagle-import:0603-RES")
      (libsource (lib "eagle-import") (part "RESISTOR0603_RES"))
    )
    (comp (ref "R34")
      (value "10kΩ")
      (footprint "eagle-import:0603-RES")
      (libsource (lib "eagle-import") (part "RESISTOR0603_RES"))
    )
    (comp (ref "R35")
      (value "10kΩ")
      (footprint "eagle-import:0603-RES")
      (libsource (lib "eagle-import") (part "RESISTOR0603_RES"))
    )
    (comp (ref "R36")
      (value "10kΩ")
      (footprint "eagle-import:0603-RES")
      (libsource (lib "eagle-import") (part "RESISTOR0603_RES"))
    )
    (comp (ref "R37")
      (value "10kΩ")
      (footprint "eagle-import:0603-RES")
      (libsource (lib "eagle-import") (part "RESISTOR0603_RES"))
    )
    (comp (ref "R38")
      (value "10kΩ")
      (footprint "eagle-import:0603-RES")
      (libsource (lib "eagle-import") (part "RESISTOR0603_RES"))
    )
    (comp (ref "R39")
      (value "10kΩ")
      (footprint "eagle-import:0603-RES")
      (libsource (lib "eagle-import") (part "RESISTOR0603_RES"))
    )
    (comp (ref "R40")
      (value "10kΩ")
      (footprint "eagle-import:0603-RES")
      (libsource (lib "eagle-import") (part "RESISTOR0603_RES"))
    )
    (comp (ref "R41")
      (value "10kΩ")
      (footprint "eagle-import:0603-RES")
      (libsource (lib "eagle-import") (part "RESISTOR0603_RES"))
    )
    (comp (ref "R42")
      (value "10kΩ")
      (footprint "eagle-import:0603-RES")
      (libsource (lib "eagle-import") (part "RESISTOR0603_RES"))
    )
    (comp (ref "R43")
      (value "10kΩ")
      (footprint "eagle-import:0603-RES")
      (libsource (lib "eagle-import") (part "RESISTOR0603_RES"))
    )
    (comp (ref "R44")
      (value "10kΩ")
      (footprint "eagle-import:0603-RES")
      (libsource (lib "eagle-import") (part "RESISTOR0603_RES"))
    )
    (comp (ref "S1")
      (value "SIP3240X")
      (footprint "eagle-import:TDFN4")
      (libsource (lib "eagle-import") (part "SIP3240X"))
    )
    (comp (ref "S2")
      (value "SIP3240X")
      (footprint "eagle-import:TDFN4")
      (libsource (lib "eagle-import") (part "SIP3240X"))
    )
    (comp (ref "S3")
      (value "SIP3240X")
      (footprint "eagle-import:TDFN4")
      (libsource (lib "eagle-import") (part "SIP3240X"))
    )
    (comp (ref "S4")
      (value "SIP3240X")
      (footprint "eagle-import:TDFN4")
      (libsource (lib "eagle-import") (part "SIP3240X"))
    )
    (comp (ref "S5")
      (value "SIP3240X")
      (footprint "eagle-import:TDFN4")
      (libsource (lib "eagle-import") (part "SIP3240X"))
    )
    (comp (ref "S6")
      (value "SIP3240X")
      (footprint "eagle-import:TDFN4")
      (libsource (lib "eagle-import") (part "SIP3240X"))
    )
    (comp (ref "U2")
      (value "FXMA2102")
      (footprint "eagle-import:UMLP-8")
      (libsource (lib "eagle-import") (part "FXMA2102"))
    )
    (comp (ref "U3")
      (value "FXMA2102")
      (footprint "eagle-import:UMLP-8")
      (libsource (lib "eagle-import") (part "FXMA2102"))
    )
    (comp (ref "U4")
      (value "FXMA2102")
      (footprint "eagle-import:UMLP-8")
      (libsource (lib "eagle-import") (part "FXMA2102"))
    )
    (comp (ref "U5")
      (value "FXMA2102")
      (footprint "eagle-import:UMLP-8")
      (libsource (lib "eagle-import") (part "FXMA2102"))
    )
    (comp (ref "U6")
      (value "FXMA2102")
      (footprint "eagle-import:UMLP-8")
      (libsource (lib "eagle-import") (part "FXMA2102"))
    )
    (comp (ref "U7")
      (value "FXMA2102")
      (footprint "eagle-import:UMLP-8")
      (libsource (lib "eagle-import") (part "FXMA2102"))
    )
    (comp (ref "C70")
      (value "100nF")
      (footprint "eagle-import:0603_CAP")
      (libsource (lib "eagle-import") (part "CAPACITOR0603_CAP"))
    )
    (comp (ref "C71")
      (value "100nF")
      (footprint "eagle-import:0603_CAP")
      (libsource (lib "eagle-import") (part "CAPACITOR0603_CAP"))
    )
    (comp (ref "C72")
      (value "100nF")
      (footprint "eagle-import:0603_CAP")
      (libsource (lib "eagle-import") (part "CAPACITOR0603_CAP"))
    )
    (comp (ref "C73")
      (value "100nF")
      (footprint "eagle-import:0603_CAP")
      (libsource (lib "eagle-import") (part "CAPACITOR0603_CAP"))
    )
    (comp (ref "C74")
      (value "100nF")
      (footprint "eagle-import:0603_CAP")
      (libsource (lib "eagle-import") (part "CAPACITOR0603_CAP"))
    )
    (comp (ref "C75")
      (value "100nF")
      (footprint "eagle-import:0603_CAP")
      (libsource (lib "eagle-import") (part "CAPACITOR0603_CAP"))
    )
    (comp (ref "C76")
      (value "100nF")
      (footprint "eagle-import:0603_CAP")
      (libsource (lib "eagle-import") (part "CAPACITOR0603_CAP"))
    )
    (comp (ref "C77")
      (value "100nF")
      (footprint "eagle-import:0603_CAP")
      (libsource (lib "eagle-import") (part "CAPACITOR0603_CAP"))
    )
    (comp (ref "C78")
      (value "100nF")
      (footprint "eagle-import:0603_CAP")
      (libsource (lib "eagle-import") (part "CAPACITOR0603_CAP"))
    )
    (comp (ref "C79")
      (value "100nF")
      (footprint "eagle-import:0603_CAP")
      (libsource (lib "eagle-import") (part "CAPACITOR0603_CAP"))
    )
    (comp (ref "C80")
      (value "100nF")
      (footprint "eagle-import:0603_CAP")
      (libsource (lib "eagle-import") (part "CAPACITOR0603_CAP"))
    )
    (comp (ref "C81")
      (value "100nF")
      (footprint "eagle-import:0603_CAP")
      (libsource (lib "eagle-import") (part "CAPACITOR0603_CAP"))
    )
    (comp (ref "C82")
      (value "100nF")
      (footprint "eagle-import:0603_CAP")
      (libsource (lib "eagle-import") (part "CAPACITOR0603_CAP"))
    )
    (comp (ref "C83")
      (value "100nF")
      (footprint "eagle-import:0603_CAP")
      (libsource (lib "eagle-import") (part "CAPACITOR0603_CAP"))
    )
    (comp (ref "C84")
      (value "100nF")
      (footprint "eagle-import:0603_CAP")
      (libsource (lib "eagle-import") (part "CAPACITOR0603_CAP"))
    )
    (comp (ref "C85")
      (value "100nF")
      (footprint "eagle-import:0603_CAP")
      (libsource (lib "eagle-import") (part "CAPACITOR0603_CAP"))
    )
    (comp (ref "C86")
      (value "100nF")
      (footprint "eagle-import:0603_CAP")
      (libsource (lib "eagle-import") (part "CAPACITOR0603_CAP"))
    )
    (comp (ref "C87")
      (value "100nF")
      (footprint "eagle-import:0603_CAP")
      (libsource (lib "eagle-import") (part "CAPACITOR0603_CAP"))
    )
    (comp (ref "C95")
      (value "150uF")
      (footprint "eagle-import:1210_CAP")
      (libsource (lib "eagle-import") (part "CAPACITOR1210_CAP"))
    )
    (comp (ref "C96")
      (value "150uF")
      (footprint "eagle-import:1210_CAP")
      (libsource (lib "eagle-import") (part "CAPACITOR1210_CAP"))
    )
    (comp (ref "C97")
      (value "150uF")
      (footprint "eagle-import:1210_CAP")
      (libsource (lib "eagle-import") (part "CAPACITOR1210_CAP"))
    )
    (comp (ref "C98")
      (value "150uF")
      (footprint "eagle-import:1210_CAP")
      (libsource (lib "eagle-import") (part "CAPACITOR1210_CAP"))
    )
    (comp (ref "C99")
      (value "150uF")
      (footprint "eagle-import:1210_CAP")
      (libsource (lib "eagle-import") (part "CAPACITOR1210_CAP"))
    )
    (comp (ref "C100")
      (value "150uF")
      (footprint "eagle-import:1210_CAP")
      (libsource (lib "eagle-import") (part "CAPACITOR1210_CAP"))
    )
    (comp (ref "R27")
      (value "10kΩ")
      (footprint "eagle-import:0603-RES")
      (libsource (lib "eagle-import") (part "RESISTOR0603_RES"))
    )
    (comp (ref "R28")
      (value "10kΩ")
      (footprint "eagle-import:0603-RES")
      (libsource (lib "eagle-import") (part "RESISTOR0603_RES"))
    )
    (comp (ref "R29")
      (value "10kΩ")
      (footprint "eagle-import:0603-RES")
      (libsource (lib "eagle-import") (part "RESISTOR0603_RES"))
    )
    (comp (ref "R30")
      (value "10kΩ")
      (footprint "eagle-import:0603-RES")
      (libsource (lib "eagle-import") (part "RESISTOR0603_RES"))
    )
    (comp (ref "R31")
      (value "10kΩ")
      (footprint "eagle-import:0603-RES")
      (libsource (lib "eagle-import") (part "RESISTOR0603_RES"))
    )
    (comp (ref "R32")
      (value "10kΩ")
      (footprint "eagle-import:0603-RES")
      (libsource (lib "eagle-import") (part "RESISTOR0603_RES"))
    )
    (comp (ref "S7")
      (value "NC7SZ157")
      (footprint "eagle-import:SC70-6")
      (libsource (lib "eagle-import") (part "NC7SZ157"))
    )
    (comp (ref "S8")
      (value "NC7SZ157")
      (footprint "eagle-import:SC70-6")
      (libsource (lib "eagle-import") (part "NC7SZ157"))
    )
    (comp (ref "S9")
      (value "NC7SZ157")
      (footprint "eagle-import:SC70-6")
      (libsource (lib "eagle-import") (part "NC7SZ157"))
    )
    (comp (ref "S10")
      (value "NC7SZ157")
      (footprint "eagle-import:SC70-6")
      (libsource (lib "eagle-import") (part "NC7SZ157"))
    )
    (comp (ref "S11")
      (value "NC7SZ157")
      (footprint "eagle-import:SC70-6")
      (libsource (lib "eagle-import") (part "NC7SZ157"))
    )
    (comp (ref "S12")
      (value "NC7SZ157")
      (footprint "eagle-import:SC70-6")
      (libsource (lib "eagle-import") (part "NC7SZ157"))
    )
    (comp (ref "S13")
      (value "AP2401MP")
      (footprint "eagle-import:MSOP-8EP")
      (libsource (lib "eagle-import") (part "AP2401MP"))
    )
    (comp (ref "S14")
      (value "AP2401MP")
      (footprint "eagle-import:MSOP-8EP")
      (libsource (lib "eagle-import") (part "AP2401MP"))
    )
    (comp (ref "S15")
      (value "AP2401MP")
      (footprint "eagle-import:MSOP-8EP")
      (libsource (lib "eagle-import") (part "AP2401MP"))
    )
    (comp (ref "S16")
      (value "AP2401MP")
      (footprint "eagle-import:MSOP-8EP")
      (libsource (lib "eagle-import") (part "AP2401MP"))
    )
    (comp (ref "S17")
      (value "AP2401MP")
      (footprint "eagle-import:MSOP-8EP")
      (libsource (lib "eagle-import") (part "AP2401MP"))
    )
    (comp (ref "S18")
      (value "AP2401MP")
      (footprint "eagle-import:MSOP-8EP")
      (libsource (lib "eagle-import") (part "AP2401MP"))
    )
    (comp (ref "C39")
      (value "100nF")
      (footprint "eagle-import:0603_CAP")
      (libsource (lib "eagle-import") (part "CAPACITOR0603_CAP"))
    )
    (comp (ref "C40")
      (value "100nF")
      (footprint "eagle-import:0603_CAP")
      (libsource (lib "eagle-import") (part "CAPACITOR0603_CAP"))
    )
    (comp (ref "C41")
      (value "100nF")
      (footprint "eagle-import:0603_CAP")
      (libsource (lib "eagle-import") (part "CAPACITOR0603_CAP"))
    )
    (comp (ref "C42")
      (value "100nF")
      (footprint "eagle-import:0603_CAP")
      (libsource (lib "eagle-import") (part "CAPACITOR0603_CAP"))
    )
    (comp (ref "C43")
      (value "100nF")
      (footprint "eagle-import:0603_CAP")
      (libsource (lib "eagle-import") (part "CAPACITOR0603_CAP"))
    )
    (comp (ref "C44")
      (value "100nF")
      (footprint "eagle-import:0603_CAP")
      (libsource (lib "eagle-import") (part "CAPACITOR0603_CAP"))
    )
    (comp (ref "C45")
      (value "100nF")
      (footprint "eagle-import:0603_CAP")
      (libsource (lib "eagle-import") (part "CAPACITOR0603_CAP"))
    )
    (comp (ref "C46")
      (value "100nF")
      (footprint "eagle-import:0603_CAP")
      (libsource (lib "eagle-import") (part "CAPACITOR0603_CAP"))
    )
    (comp (ref "C47")
      (value "100nF")
      (footprint "eagle-import:0603_CAP")
      (libsource (lib "eagle-import") (part "CAPACITOR0603_CAP"))
    )
    (comp (ref "C48")
      (value "100nF")
      (footprint "eagle-import:0603_CAP")
      (libsource (lib "eagle-import") (part "CAPACITOR0603_CAP"))
    )
    (comp (ref "C49")
      (value "100nF")
      (footprint "eagle-import:0603_CAP")
      (libsource (lib "eagle-import") (part "CAPACITOR0603_CAP"))
    )
    (comp (ref "C50")
      (value "100nF")
      (footprint "eagle-import:0603_CAP")
      (libsource (lib "eagle-import") (part "CAPACITOR0603_CAP"))
    )
    (comp (ref "C51")
      (value "100nF")
      (footprint "eagle-import:0603_CAP")
      (libsource (lib "eagle-import") (part "CAPACITOR0603_CAP"))
    )
    (comp (ref "C52")
      (value "100nF")
      (footprint "eagle-import:0603_CAP")
      (libsource (lib "eagle-import") (part "CAPACITOR0603_CAP"))
    )
    (comp (ref "C53")
      (value "100nF")
      (footprint "eagle-import:0603_CAP")
      (libsource (lib "eagle-import") (part "CAPACITOR0603_CAP"))
    )
    (comp (ref "C54")
      (value "100nF")
      (footprint "eagle-import:0603_CAP")
      (libsource (lib "eagle-import") (part "CAPACITOR0603_CAP"))
    )
    (comp (ref "C55")
      (value "100nF")
      (footprint "eagle-import:0603_CAP")
      (libsource (lib "eagle-import") (part "CAPACITOR0603_CAP"))
    )
    (comp (ref "C56")
      (value "100nF")
      (footprint "eagle-import:0603_CAP")
      (libsource (lib "eagle-import") (part "CAPACITOR0603_CAP"))
    )
    (comp (ref "C57")
      (value "100nF")
      (footprint "eagle-import:0603_CAP")
      (libsource (lib "eagle-import") (part "CAPACITOR0603_CAP"))
    )
    (comp (ref "C58")
      (value "100nF")
      (footprint "eagle-import:0603_CAP")
      (libsource (lib "eagle-import") (part "CAPACITOR0603_CAP"))
    )
    (comp (ref "C59")
      (value "100nF")
      (footprint "eagle-import:0603_CAP")
      (libsource (lib "eagle-import") (part "CAPACITOR0603_CAP"))
    )
    (comp (ref "C60")
      (value "100nF")
      (footprint "eagle-import:0603_CAP")
      (libsource (lib "eagle-import") (part "CAPACITOR0603_CAP"))
    )
    (comp (ref "C61")
      (value "100nF")
      (footprint "eagle-import:0603_CAP")
      (libsource (lib "eagle-import") (part "CAPACITOR0603_CAP"))
    )
    (comp (ref "C62")
      (value "100nF")
      (footprint "eagle-import:0603_CAP")
      (libsource (lib "eagle-import") (part "CAPACITOR0603_CAP"))
    )
    (comp (ref "U8")
      (value "SN74LVC2T45")
      (footprint "eagle-import:VFSOP-8")
      (libsource (lib "eagle-import") (part "SN74LVC2T45"))
    )
    (comp (ref "U9")
      (value "SN74LVC2T45")
      (footprint "eagle-import:VFSOP-8")
      (libsource (lib "eagle-import") (part "SN74LVC2T45"))
    )
    (comp (ref "U10")
      (value "SN74LVC2T45")
      (footprint "eagle-import:VFSOP-8")
      (libsource (lib "eagle-import") (part "SN74LVC2T45"))
    )
    (comp (ref "U11")
      (value "SN74LVC2T45")
      (footprint "eagle-import:VFSOP-8")
      (libsource (lib "eagle-import") (part "SN74LVC2T45"))
    )
    (comp (ref "U12")
      (value "SN74LVC2T45")
      (footprint "eagle-import:VFSOP-8")
      (libsource (lib "eagle-import") (part "SN74LVC2T45"))
    )
    (comp (ref "U13")
      (value "SN74LVC2T45")
      (footprint "eagle-import:VFSOP-8")
      (libsource (lib "eagle-import") (part "SN74LVC2T45"))
    )
    (comp (ref "U14")
      (value "SN74LVC2T45")
      (footprint "eagle-import:VFSOP-8")
      (libsource (lib "eagle-import") (part "SN74LVC2T45"))
    )
    (comp (ref "U15")
      (value "SN74LVC2T45")
      (footprint "eagle-import:VFSOP-8")
      (libsource (lib "eagle-import") (part "SN74LVC2T45"))
    )
    (comp (ref "U16")
      (value "SN74LVC2T45")
      (footprint "eagle-import:VFSOP-8")
      (libsource (lib "eagle-import") (part "SN74LVC2T45"))
    )
    (comp (ref "U17")
      (value "SN74LVC2T45")
      (footprint "eagle-import:VFSOP-8")
      (libsource (lib "eagle-import") (part "SN74LVC2T45"))
    )
    (comp (ref "U18")
      (value "SN74LVC2T45")
      (footprint "eagle-import:VFSOP-8")
      (libsource (lib "eagle-import") (part "SN74LVC2T45"))
    )
    (comp (ref "U19")
      (value "SN74LVC2T45")
      (footprint "eagle-import:VFSOP-8")
      (libsource (lib "eagle-import") (part "SN74LVC2T45"))
    )
    (comp (ref "LED1001")
      (value "LED0603")
      (footprint "eagle-import:LED-0603")
      (libsource (lib "eagle-import") (part "LED0603"))
    )
    (comp (ref "LED1002")
      (value "LED0603")
      (footprint "eagle-import:LED-0603")
      (libsource (lib "eagle-import") (part "LED0603"))
    )
    (comp (ref "LED1003")
      (value "LED0603")
      (footprint "eagle-import:LED-0603")
      (libsource (lib "eagle-import") (part "LED0603"))
    )
    (comp (ref "LED1004")
      (value "LED0603")
      (footprint "eagle-import:LED-0603")
      (libsource (lib "eagle-import") (part "LED0603"))
    )
    (comp (ref "LED1005")
      (value "LED0603")
      (footprint "eagle-import:LED-0603")
      (libsource (lib "eagle-import") (part "LED0603"))
    )
    (comp (ref "LED1006")
      (value "LED0603")
      (footprint "eagle-import:LED-0603")
      (libsource (lib "eagle-import") (part "LED0603"))
    )
    (comp (ref "LED1007")
      (value "LED0603")
      (footprint "eagle-import:LED-0603")
      (libsource (lib "eagle-import") (part "LED0603"))
    )
    (comp (ref "LED1008")
      (value "LED0603")
      (footprint "eagle-import:LED-0603")
      (libsource (lib "eagle-import") (part "LED0603"))
    )
    (comp (ref "LED1009")
      (value "LED0603")
      (footprint "eagle-import:LED-0603")
      (libsource (lib "eagle-import") (part "LED0603"))
    )
    (comp (ref "LED1010")
      (value "LED0603")
      (footprint "eagle-import:LED-0603")
      (libsource (lib "eagle-import") (part "LED0603"))
    )
    (comp (ref "LED1011")
      (value "LED0603")
      (footprint "eagle-import:LED-0603")
      (libsource (lib "eagle-import") (part "LED0603"))
    )
    (comp (ref "LED1012")
      (value "LED0603")
      (footprint "eagle-import:LED-0603")
      (libsource (lib "eagle-import") (part "LED0603"))
    )
    (comp (ref "LED1013")
      (value "LED0603")
      (footprint "eagle-import:LED-0603")
      (libsource (lib "eagle-import") (part "LED0603"))
    )
    (comp (ref "LED1014")
      (value "LED0603")
      (footprint "eagle-import:LED-0603")
      (libsource (lib "eagle-import") (part "LED0603"))
    )
    (comp (ref "LED1015")
      (value "LED0603")
      (footprint "eagle-import:LED-0603")
      (libsource (lib "eagle-import") (part "LED0603"))
    )
    (comp (ref "LED1016")
      (value "LED0603")
      (footprint "eagle-import:LED-0603")
      (libsource (lib "eagle-import") (part "LED0603"))
    )
    (comp (ref "LED1017")
      (value "LED0603")
      (footprint "eagle-import:LED-0603")
      (libsource (lib "eagle-import") (part "LED0603"))
    )
    (comp (ref "LED1018")
      (value "LED0603")
      (footprint "eagle-import:LED-0603")
      (libsource (lib "eagle-import") (part "LED0603"))
    )
    (comp (ref "R1001")
      (value "15Ω")
      (footprint "eagle-import:0603-RES")
      (libsource (lib "eagle-import") (part "RESISTOR0603_RES"))
    )
    (comp (ref "R1002")
      (value "15Ω")
      (footprint "eagle-import:0603-RES")
      (libsource (lib "eagle-import") (part "RESISTOR0603_RES"))
    )
    (comp (ref "R1003")
      (value "15Ω")
      (footprint "eagle-import:0603-RES")
      (libsource (lib "eagle-import") (part "RESISTOR0603_RES"))
    )
    (comp (ref "R1004")
      (value "15Ω")
      (footprint "eagle-import:0603-RES")
      (libsource (lib "eagle-import") (part "RESISTOR0603_RES"))
    )
    (comp (ref "R1005")
      (value "15Ω")
      (footprint "eagle-import:0603-RES")
      (libsource (lib "eagle-import") (part "RESISTOR0603_RES"))
    )
    (comp (ref "R1006")
      (value "15Ω")
      (footprint "eagle-import:0603-RES")
      (libsource (lib "eagle-import") (part "RESISTOR0603_RES"))
    )
    (comp (ref "R1007")
      (value "15Ω")
      (footprint "eagle-import:0603-RES")
      (libsource (lib "eagle-import") (part "RESISTOR0603_RES"))
    )
    (comp (ref "R1008")
      (value "15Ω")
      (footprint "eagle-import:0603-RES")
      (libsource (lib "eagle-import") (part "RESISTOR0603_RES"))
    )
    (comp (ref "R1009")
      (value "15Ω")
      (footprint "eagle-import:0603-RES")
      (libsource (lib "eagle-import") (part "RESISTOR0603_RES"))
    )
    (comp (ref "R1010")
      (value "15Ω")
      (footprint "eagle-import:0603-RES")
      (libsource (lib "eagle-import") (part "RESISTOR0603_RES"))
    )
    (comp (ref "R1011")
      (value "15Ω")
      (footprint "eagle-import:0603-RES")
      (libsource (lib "eagle-import") (part "RESISTOR0603_RES"))
    )
    (comp (ref "R1012")
      (value "15Ω")
      (footprint "eagle-import:0603-RES")
      (libsource (lib "eagle-import") (part "RESISTOR0603_RES"))
    )
    (comp (ref "R1013")
      (value "15Ω")
      (footprint "eagle-import:0603-RES")
      (libsource (lib "eagle-import") (part "RESISTOR0603_RES"))
    )
    (comp (ref "R1014")
      (value "15Ω")
      (footprint "eagle-import:0603-RES")
      (libsource (lib "eagle-import") (part "RESISTOR0603_RES"))
    )
    (comp (ref "R1015")
      (value "15Ω")
      (footprint "eagle-import:0603-RES")
      (libsource (lib "eagle-import") (part "RESISTOR0603_RES"))
    )
    (comp (ref "R1016")
      (value "15Ω")
      (footprint "eagle-import:0603-RES")
      (libsource (lib "eagle-import") (part "RESISTOR0603_RES"))
    )
    (comp (ref "R1017")
      (value "15Ω")
      (footprint "eagle-import:0603-RES")
      (libsource (lib "eagle-import") (part "RESISTOR0603_RES"))
    )
    (comp (ref "R1018")
      (value "15Ω")
      (footprint "eagle-import:0603-RES")
      (libsource (lib "eagle-import") (part "RESISTOR0603_RES"))
    )
    (comp (ref "TP1")
      (value "TEST_POINT_0.040IN")
      (footprint "eagle-import:TESTPOINT_0.040IN")
      (libsource (lib "eagle-import") (part "TEST_POINT_0.040IN"))
    )
    (comp (ref "TP2")
      (value "TEST_POINT_0.040IN")
      (footprint "eagle-import:TESTPOINT_0.040IN")
      (libsource (lib "eagle-import") (part "TEST_POINT_0.040IN"))
    )
    (comp (ref "TP3")
      (value "TEST_POINT_0.040IN")
      (footprint "eagle-import:TESTPOINT_0.040IN")
      (libsource (lib "eagle-import") (part "TEST_POINT_0.040IN"))
    )
    (comp (ref "TP4")
      (value "TEST_POINT_0.040IN")
      (footprint "eagle-import:TESTPOINT_0.040IN")
      (libsource (lib "eagle-import") (part "TEST_POINT_0.040IN"))
    )
    (comp (ref "TP5")
      (value "TEST_POINT_0.040IN")
      (footprint "eagle-import:TESTPOINT_0.040IN")
      (libsource (lib "eagle-import") (part "TEST_POINT_0.040IN"))
    )
    (comp (ref "TP6")
      (value "TEST_POINT_0.040IN")
      (footprint "eagle-import:TESTPOINT_0.040IN")
      (libsource (lib "eagle-import") (part "TEST_POINT_0.040IN"))
    )
    (comp (ref "TP7")
      (value "TEST_POINT_0.040IN")
      (footprint "eagle-import:TESTPOINT_0.040IN")
      (libsource (lib "eagle-import") (part "TEST_POINT_0.040IN"))
    )
    (comp (ref "TP8")
      (value "TEST_POINT_0.040IN")
      (footprint "eagle-import:TESTPOINT_0.040IN")
      (libsource (lib "eagle-import") (part "TEST_POINT_0.040IN"))
    )
    (comp (ref "TP9")
      (value "TEST_POINT_0.040IN")
      (footprint "eagle-import:TESTPOINT_0.040IN")
      (libsource (lib "eagle-import") (part "TEST_POINT_0.040IN"))
    )
    (comp (ref "TP10")
      (value "TEST_POINT_0.040IN")
      (footprint "eagle-import:TESTPOINT_0.040IN")
      (libsource (lib "eagle-import") (part "TEST_POINT_0.040IN"))
    )
    (comp (ref "TP11")
      (value "TEST_POINT_0.040IN")
      (footprint "eagle-import:TESTPOINT_0.040IN")
      (libsource (lib "eagle-import") (part "TEST_POINT_0.040IN"))
    )
    (comp (ref "TP12")
      (value "TEST_POINT_0.040IN")
      (footprint "eagle-import:TESTPOINT_0.040IN")
      (libsource (lib "eagle-import") (part "TEST_POINT_0.040IN"))
    )
    (comp (ref "TP13")
      (value "TEST_POINT_0.040IN")
      (footprint "eagle-import:TESTPOINT_0.040IN")
      (libsource (lib "eagle-import") (part "TEST_POINT_0.040IN"))
    )
    (comp (ref "TP14")
      (value "TEST_POINT_0.040IN")
      (footprint "eagle-import:TESTPOINT_0.040IN")
      (libsource (lib "eagle-import") (part "TEST_POINT_0.040IN"))
    )
    (comp (ref "TP15")
      (value "TEST_POINT_0.040IN")
      (footprint "eagle-import:TESTPOINT_0.040IN")
      (libsource (lib "eagle-import") (part "TEST_POINT_0.040IN"))
    )
    (comp (ref "TP16")
      (value "TEST_POINT_0.040IN")
      (footprint "eagle-import:TESTPOINT_0.040IN")
      (libsource (lib "eagle-import") (part "TEST_POINT_0.040IN"))
    )
    (comp (ref "TP17")
      (value "TEST_POINT_0.040IN")
      (footprint "eagle-import:TESTPOINT_0.040IN")
      (libsource (lib "eagle-import") (part "TEST_POINT_0.040IN"))
    )
    (comp (ref "TP18")
      (value "TEST_POINT_0.040IN")
      (footprint "eagle-import:TESTPOINT_0.040IN")
      (libsource (lib "eagle-import") (part "TEST_POINT_0.040IN"))
    )
    (comp (ref "TP19")
      (value "TEST_POINT_0.040IN")
      (footprint "eagle-import:TESTPOINT_0.040IN")
      (libsource (lib "eagle-import") (part "TEST_POINT_0.040IN"))
    )
    (comp (ref "TP20")
      (value "TEST_POINT_0.040IN")
      (footprint "eagle-import:TESTPOINT_0.040IN")
      (libsource (lib "eagle-import") (part "TEST_POINT_0.040IN"))
    )
    (comp (ref "TP21")
      (value "TEST_POINT_0.040IN")
      (footprint "eagle-import:TESTPOINT_0.040IN")
      (libsource (lib "eagle-import") (part "TEST_POINT_0.040IN"))
    )
    (comp (ref "TP22")
      (value "TEST_POINT_0.040IN")
      (footprint "eagle-import:TESTPOINT_0.040IN")
      (libsource (lib "eagle-import") (part "TEST_POINT_0.040IN"))
    )
    (comp (ref "TP23")
      (value "TEST_POINT_0.040IN")
      (footprint "eagle-import:TESTPOINT_0.040IN")
      (libsource (lib "eagle-import") (part "TEST_POINT_0.040IN"))
    )
    (comp (ref "TP24")
      (value "TEST_POINT_0.040IN")
      (footprint "eagle-import:TESTPOINT_0.040IN")
      (libsource (lib "eagle-import") (part "TEST_POINT_0.040IN"))
    )
    (comp (ref "TP25")
      (value "TEST_POINT_0.040IN")
      (footprint "eagle-import:TESTPOINT_0.040IN")
      (libsource (lib "eagle-import") (part "TEST_POINT_0.040IN"))
    )
    (comp (ref "TP26")
      (value "TEST_POINT_0.040IN")
      (footprint "eagle-import:TESTPOINT_0.040IN")
      (libsource (lib "eagle-import") (part "TEST_POINT_0.040IN"))
    )
    (comp (ref "TP27")
      (value "TEST_POINT_0.040IN")
      (footprint "eagle-import:TESTPOINT_0.040IN")
      (libsource (lib "eagle-import") (part "TEST_POINT_0.040IN"))
    )
    (comp (ref "TP28")
      (value "TEST_POINT_0.040IN")
      (footprint "eagle-import:TESTPOINT_0.040IN")
      (libsource (lib "eagle-import") (part "TEST_POINT_0.040IN"))
    )
    (comp (ref "TP29")
      (value "TEST_POINT_0.040IN")
      (footprint "eagle-import:TESTPOINT_0.040IN")
      (libsource (lib "eagle-import") (part "TEST_POINT_0.040IN"))
    )
    (comp (ref "TP30")
      (value "TEST_POINT_0.040IN")
      (footprint "eagle-import:TESTPOINT_0.040IN")
      (libsource (lib "eagle-import") (part "TEST_POINT_0.040IN"))
    )
    (comp (ref "TP31")
      (value "TEST_POINT_0.040IN")
      (footprint "eagle-import:TESTPOINT_0.040IN")
      (libsource (lib "eagle-import") (part "TEST_POINT_0.040IN"))
    )
    (comp (ref "TP32")
      (value "TEST_POINT_0.040IN")
      (footprint "eagle-import:TESTPOINT_0.040IN")
      (libsource (lib "eagle-import") (part "TEST_POINT_0.040IN"))
    )
    (comp (ref "TP33")
      (value "TEST_POINT_0.040IN")
      (footprint "eagle-import:TESTPOINT_0.040IN")
      (libsource (lib "eagle-import") (part "TEST_POINT_0.040IN"))
    )
    (comp (ref "TP34")
      (value "TEST_POINT_0.040IN")
      (footprint "eagle-import:TESTPOINT_0.040IN")
      (libsource (lib "eagle-import") (part "TEST_POINT_0.040IN"))
    )
    (comp (ref "TP35")
      (value "TEST_POINT_0.040IN")
      (footprint "eagle-import:TESTPOINT_0.040IN")
      (libsource (lib "eagle-import") (part "TEST_POINT_0.040IN"))
    )
    (comp (ref "TP36")
      (value "TEST_POINT_0.040IN")
      (footprint "eagle-import:TESTPOINT_0.040IN")
      (libsource (lib "eagle-import") (part "TEST_POINT_0.040IN"))
    )
    (comp (ref "TP37")
      (value "TEST_POINT_0.040IN")
      (footprint "eagle-import:TESTPOINT_0.040IN")
      (libsource (lib "eagle-import") (part "TEST_POINT_0.040IN"))
    )
    (comp (ref "TP38")
      (value "TEST_POINT_0.040IN")
      (footprint "eagle-import:TESTPOINT_0.040IN")
      (libsource (lib "eagle-import") (part "TEST_POINT_0.040IN"))
    )
    (comp (ref "TP39")
      (value "TEST_POINT_0.040IN")
      (footprint "eagle-import:TESTPOINT_0.040IN")
      (libsource (lib "eagle-import") (part "TEST_POINT_0.040IN"))
    )
    (comp (ref "TP40")
      (value "TEST_POINT_0.040IN")
      (footprint "eagle-import:TESTPOINT_0.040IN")
      (libsource (lib "eagle-import") (part "TEST_POINT_0.040IN"))
    )
    (comp (ref "TP41")
      (value "TEST_POINT_0.040IN")
      (footprint "eagle-import:TESTPOINT_0.040IN")
      (libsource (lib "eagle-import") (part "TEST_POINT_0.040IN"))
    )
    (comp (ref "TP42")
      (value "TEST_POINT_0.040IN")
      (footprint "eagle-import:TESTPOINT_0.040IN")
      (libsource (lib "eagle-import") (part "TEST_POINT_0.040IN"))
    )
    (comp (ref "TP43")
      (value "TEST_POINT_0.040IN")
      (footprint "eagle-import:TESTPOINT_0.040IN")
      (libsource (lib "eagle-import") (part "TEST_POINT_0.040IN"))
    )
    (comp (ref "TP1001")
      (value "TEST_POINT_0.040IN")
      (footprint "eagle-import:TESTPOINT_0.040IN")
      (libsource (lib "eagle-import") (part "TEST_POINT_0.040IN"))
    )
    (comp (ref "TP1002")
      (value "TEST_POINT_0.040IN")
      (footprint "eagle-import:TESTPOINT_0.040IN")
      (libsource (lib "eagle-import") (part "TEST_POINT_0.040IN"))
    )
    (comp (ref "TP1003")
      (value "TEST_POINT_0.040IN")
      (footprint "eagle-import:TESTPOINT_0.040IN")
      (libsource (lib "eagle-import") (part "TEST_POINT_0.040IN"))
    )
    (comp (ref "TP1004")
      (value "TEST_POINT_0.040IN")
      (footprint "eagle-import:TESTPOINT_0.040IN")
      (libsource (lib "eagle-import") (part "TEST_POINT_0.040IN"))
    )
    (comp (ref "TP1005")
      (value "TEST_POINT_0.040IN")
      (footprint "eagle-import:TESTPOINT_0.040IN")
      (libsource (lib "eagle-import") (part "TEST_POINT_0.040IN"))
    )
    (comp (ref "TP1006")
      (value "TEST_POINT_0.040IN")
      (footprint "eagle-import:TESTPOINT_0.040IN")
      (libsource (lib "eagle-import") (part "TEST_POINT_0.040IN"))
    )
    (comp (ref "TP1007")
      (value "TEST_POINT_0.040IN")
      (footprint "eagle-import:TESTPOINT_0.040IN")
      (libsource (lib "eagle-import") (part "TEST_POINT_0.040IN"))
    )
    (comp (ref "TP1008")
      (value "TEST_POINT_0.040IN")
      (footprint "eagle-import:TESTPOINT_0.040IN")
      (libsource (lib "eagle-import") (part "TEST_POINT_0.040IN"))
    )
    (comp (ref "TP1009")
      (value "TEST_POINT_0.040IN")
      (footprint "eagle-import:TESTPOINT_0.040IN")
      (libsource (lib "eagle-import") (part "TEST_POINT_0.040IN"))
    )
    (comp (ref "TP1010")
      (value "TEST_POINT_0.040IN")
      (footprint "eagle-import:TESTPOINT_0.040IN")
      (libsource (lib "eagle-import") (part "TEST_POINT_0.040IN"))
    )
    (comp (ref "TP1011")
      (value "TEST_POINT_0.040IN")
      (footprint "eagle-import:TESTPOINT_0.040IN")
      (libsource (lib "eagle-import") (part "TEST_POINT_0.040IN"))
    )
    (comp (ref "TP1012")
      (value "TEST_POINT_0.040IN")
      (footprint "eagle-import:TESTPOINT_0.040IN")
      (libsource (lib "eagle-import") (part "TEST_POINT_0.040IN"))
    )
    (comp (ref "TP1013")
      (value "TEST_POINT_0.040IN")
      (footprint "eagle-import:TESTPOINT_0.040IN")
      (libsource (lib "eagle-import") (part "TEST_POINT_0.040IN"))
    )
    (comp (ref "TP1014")
      (value "TEST_POINT_0.040IN")
      (footprint "eagle-import:TESTPOINT_0.040IN")
      (libsource (lib "eagle-import") (part "TEST_POINT_0.040IN"))
    )
    (comp (ref "TP1015")
      (value "TEST_POINT_0.040IN")
      (footprint "eagle-import:TESTPOINT_0.040IN")
      (libsource (lib "eagle-import") (part "TEST_POINT_0.040IN"))
    )
    (comp (ref "TP1016")
      (value "TEST_POINT_0.040IN")
      (footprint "eagle-import:TESTPOINT_0.040IN")
      (libsource (lib "eagle-import") (part "TEST_POINT_0.040IN"))
    )
    (comp (ref "TP1017")
      (value "TEST_POINT_0.040IN")
      (footprint "eagle-import:TESTPOINT_0.040IN")
      (libsource (lib "eagle-import") (part "TEST_POINT_0.040IN"))
    )
    (comp (ref "TP1018")
      (value "TEST_POINT_0.040IN")
      (footprint "eagle-import:TESTPOINT_0.040IN")
      (libsource (lib "eagle-import") (part "TEST_POINT_0.040IN"))
    )
    (comp (ref "C3")
      (value "22pF")
      (footprint "eagle-import:0402_CAP")
      (libsource (lib "eagle-import") (part "CAPACITOR0402_CAP"))
    )
    (comp (ref "C4")
      (value "22pF")
      (footprint "eagle-import:0402_CAP")
      (libsource (lib "eagle-import") (part "CAPACITOR0402_CAP"))
    )
    (comp (ref "C5")
      (value "22pF")
      (footprint "eagle-import:0402_CAP")
      (libsource (lib "eagle-import") (part "CAPACITOR0402_CAP"))
    )
    (comp (ref "C6")
      (value "22pF")
      (footprint "eagle-import:0402_CAP")
      (libsource (lib "eagle-import") (part "CAPACITOR0402_CAP"))
    )
    (comp (ref "C7")
      (value "22pF")
      (footprint "eagle-import:0402_CAP")
      (libsource (lib "eagle-import") (part "CAPACITOR0402_CAP"))
    )
    (comp (ref "C8")
      (value "22pF")
      (footprint "eagle-import:0402_CAP")
      (libsource (lib "eagle-import") (part "CAPACITOR0402_CAP"))
    )
    (comp (ref "C9")
      (value "22pF")
      (footprint "eagle-import:0402_CAP")
      (libsource (lib "eagle-import") (part "CAPACITOR0402_CAP"))
    )
    (comp (ref "C10")
      (value "22pF")
      (footprint "eagle-import:0402_CAP")
      (libsource (lib "eagle-import") (part "CAPACITOR0402_CAP"))
    )
    (comp (ref "C11")
      (value "22pF")
      (footprint "eagle-import:0402_CAP")
      (libsource (lib "eagle-import") (part "CAPACITOR0402_CAP"))
    )
    (comp (ref "C12")
      (value "22pF")
      (footprint "eagle-import:0402_CAP")
      (libsource (lib "eagle-import") (part "CAPACITOR0402_CAP"))
    )
    (comp (ref "C13")
      (value "22pF")
      (footprint "eagle-import:0402_CAP")
      (libsource (lib "eagle-import") (part "CAPACITOR0402_CAP"))
    )
    (comp (ref "C14")
      (value "22pF")
      (footprint "eagle-import:0402_CAP")
      (libsource (lib "eagle-import") (part "CAPACITOR0402_CAP"))
    )
    (comp (ref "C64")
      (value "100nF")
      (footprint "eagle-import:0603_CAP")
      (libsource (lib "eagle-import") (part "CAPACITOR0603_CAP"))
    )
    (comp (ref "C65")
      (value "100nF")
      (footprint "eagle-import:0603_CAP")
      (libsource (lib "eagle-import") (part "CAPACITOR0603_CAP"))
    )
    (comp (ref "C66")
      (value "100nF")
      (footprint "eagle-import:0603_CAP")
      (libsource (lib "eagle-import") (part "CAPACITOR0603_CAP"))
    )
    (comp (ref "C67")
      (value "100nF")
      (footprint "eagle-import:0603_CAP")
      (libsource (lib "eagle-import") (part "CAPACITOR0603_CAP"))
    )
    (comp (ref "C68")
      (value "100nF")
      (footprint "eagle-import:0603_CAP")
      (libsource (lib "eagle-import") (part "CAPACITOR0603_CAP"))
    )
    (comp (ref "C69")
      (value "100nF")
      (footprint "eagle-import:0603_CAP")
      (libsource (lib "eagle-import") (part "CAPACITOR0603_CAP"))
    )
    (comp (ref "D1")
      (value "SN75240-TSSOP")
      (footprint "eagle-import:TSSOP-8")
      (libsource (lib "eagle-import") (part "SN75240-TSSOP"))
    )
    (comp (ref "D2")
      (value "SN75240-TSSOP")
      (footprint "eagle-import:TSSOP-8")
      (libsource (lib "eagle-import") (part "SN75240-TSSOP"))
    )
    (comp (ref "D3")
      (value "SN75240-TSSOP")
      (footprint "eagle-import:TSSOP-8")
      (libsource (lib "eagle-import") (part "SN75240-TSSOP"))
    )
    (comp (ref "D4")
      (value "SN75240-TSSOP")
      (footprint "eagle-import:TSSOP-8")
      (libsource (lib "eagle-import") (part "SN75240-TSSOP"))
    )
    (comp (ref "R1")
      (value "27Ω")
      (footprint "eagle-import:0402_RES-HIGH_SPEED")
      (libsource (lib "eagle-import") (part "RESISTOR0402_RES-HIGH_SPEED"))
    )
    (comp (ref "R2")
      (value "27Ω")
      (footprint "eagle-import:0402_RES-HIGH_SPEED")
      (libsource (lib "eagle-import") (part "RESISTOR0402_RES-HIGH_SPEED"))
    )
    (comp (ref "R3")
      (value "27Ω")
      (footprint "eagle-import:0402_RES-HIGH_SPEED")
      (libsource (lib "eagle-import") (part "RESISTOR0402_RES-HIGH_SPEED"))
    )
    (comp (ref "R4")
      (value "27Ω")
      (footprint "eagle-import:0402_RES-HIGH_SPEED")
      (libsource (lib "eagle-import") (part "RESISTOR0402_RES-HIGH_SPEED"))
    )
    (comp (ref "R5")
      (value "27Ω")
      (footprint "eagle-import:0402_RES-HIGH_SPEED")
      (libsource (lib "eagle-import") (part "RESISTOR0402_RES-HIGH_SPEED"))
    )
    (comp (ref "R6")
      (value "27Ω")
      (footprint "eagle-import:0402_RES-HIGH_SPEED")
      (libsource (lib "eagle-import") (part "RESISTOR0402_RES-HIGH_SPEED"))
    )
    (comp (ref "R7")
      (value "27Ω")
      (footprint "eagle-import:0402_RES-HIGH_SPEED")
      (libsource (lib "eagle-import") (part "RESISTOR0402_RES-HIGH_SPEED"))
    )
    (comp (ref "R8")
      (value "27Ω")
      (footprint "eagle-import:0402_RES-HIGH_SPEED")
      (libsource (lib "eagle-import") (part "RESISTOR0402_RES-HIGH_SPEED"))
    )
    (comp (ref "R9")
      (value "27Ω")
      (footprint "eagle-import:0402_RES-HIGH_SPEED")
      (libsource (lib "eagle-import") (part "RESISTOR0402_RES-HIGH_SPEED"))
    )
    (comp (ref "R10")
      (value "27Ω")
      (footprint "eagle-import:0402_RES-HIGH_SPEED")
      (libsource (lib "eagle-import") (part "RESISTOR0402_RES-HIGH_SPEED"))
    )
    (comp (ref "R11")
      (value "27Ω")
      (footprint "eagle-import:0402_RES-HIGH_SPEED")
      (libsource (lib "eagle-import") (part "RESISTOR0402_RES-HIGH_SPEED"))
    )
    (comp (ref "R12")
      (value "27Ω")
      (footprint "eagle-import:0402_RES-HIGH_SPEED")
      (libsource (lib "eagle-import") (part "RESISTOR0402_RES-HIGH_SPEED"))
    )
    (comp (ref "R13")
      (value "50Ω")
      (footprint "eagle-import:0603-RES")
      (libsource (lib "eagle-import") (part "RESISTOR0603_RES"))
    )
    (comp (ref "R14")
      (value "50Ω")
      (footprint "eagle-import:0603-RES")
      (libsource (lib "eagle-import") (part "RESISTOR0603_RES"))
    )
    (comp (ref "R15")
      (value "50Ω")
      (footprint "eagle-import:0603-RES")
      (libsource (lib "eagle-import") (part "RESISTOR0603_RES"))
    )
    (comp (ref "R16")
      (value "50Ω")
      (footprint "eagle-import:0603-RES")
      (libsource (lib "eagle-import") (part "RESISTOR0603_RES"))
    )
    (comp (ref "R17")
      (value "50Ω")
      (footprint "eagle-import:0603-RES")
      (libsource (lib "eagle-import") (part "RESISTOR0603_RES"))
    )
    (comp (ref "R18")
      (value "50Ω")
      (footprint "eagle-import:0603-RES")
      (libsource (lib "eagle-import") (part "RESISTOR0603_RES"))
    )
    (comp (ref "R19")
      (value "50Ω")
      (footprint "eagle-import:0603-RES")
      (libsource (lib "eagle-import") (part "RESISTOR0603_RES"))
    )
    (comp (ref "R20")
      (value "50Ω")
      (footprint "eagle-import:0603-RES")
      (libsource (lib "eagle-import") (part "RESISTOR0603_RES"))
    )
    (comp (ref "R21")
      (value "50Ω")
      (footprint "eagle-import:0603-RES")
      (libsource (lib "eagle-import") (part "RESISTOR0603_RES"))
    )
    (comp (ref "R22")
      (value "50Ω")
      (footprint "eagle-import:0603-RES")
      (libsource (lib "eagle-import") (part "RESISTOR0603_RES"))
    )
    (comp (ref "R23")
      (value "50Ω")
      (footprint "eagle-import:0603-RES")
      (libsource (lib "eagle-import") (part "RESISTOR0603_RES"))
    )
    (comp (ref "R24")
      (value "50Ω")
      (footprint "eagle-import:0603-RES")
      (libsource (lib "eagle-import") (part "RESISTOR0603_RES"))
    )
    (comp (ref "R50")
      (value "15kΩ")
      (footprint "eagle-import:0603-RES")
      (libsource (lib "eagle-import") (part "RESISTOR0603_RES"))
    )
    (comp (ref "R51")
      (value "15kΩ")
      (footprint "eagle-import:0603-RES")
      (libsource (lib "eagle-import") (part "RESISTOR0603_RES"))
    )
    (comp (ref "R52")
      (value "15kΩ")
      (footprint "eagle-import:0603-RES")
      (libsource (lib "eagle-import") (part "RESISTOR0603_RES"))
    )
    (comp (ref "R53")
      (value "15kΩ")
      (footprint "eagle-import:0603-RES")
      (libsource (lib "eagle-import") (part "RESISTOR0603_RES"))
    )
    (comp (ref "R54")
      (value "15kΩ")
      (footprint "eagle-import:0603-RES")
      (libsource (lib "eagle-import") (part "RESISTOR0603_RES"))
    )
    (comp (ref "R55")
      (value "15kΩ")
      (footprint "eagle-import:0603-RES")
      (libsource (lib "eagle-import") (part "RESISTOR0603_RES"))
    )
    (comp (ref "R56")
      (value "15kΩ")
      (footprint "eagle-import:0603-RES")
      (libsource (lib "eagle-import") (part "RESISTOR0603_RES"))
    )
    (comp (ref "R57")
      (value "15kΩ")
      (footprint "eagle-import:0603-RES")
      (libsource (lib "eagle-import") (part "RESISTOR0603_RES"))
    )
    (comp (ref "R58")
      (value "15kΩ")
      (footprint "eagle-import:0603-RES")
      (libsource (lib "eagle-import") (part "RESISTOR0603_RES"))
    )
    (comp (ref "R59")
      (value "15kΩ")
      (footprint "eagle-import:0603-RES")
      (libsource (lib "eagle-import") (part "RESISTOR0603_RES"))
    )
    (comp (ref "R60")
      (value "15kΩ")
      (footprint "eagle-import:0603-RES")
      (libsource (lib "eagle-import") (part "RESISTOR0603_RES"))
    )
    (comp (ref "R61")
      (value "15kΩ")
      (footprint "eagle-import:0603-RES")
      (libsource (lib "eagle-import") (part "RESISTOR0603_RES"))
    )
    (comp (ref "U20")
      (value "TS3USB30E")
      (footprint "eagle-import:UQFN-10")
      (libsource (lib "eagle-import") (part "TS3USB30E"))
    )
    (comp (ref "U21")
      (value "TS3USB30E")
      (footprint "eagle-import:UQFN-10")
      (libsource (lib "eagle-import") (part "TS3USB30E"))
    )
    (comp (ref "U22")
      (value "TS3USB30E")
      (footprint "eagle-import:UQFN-10")
      (libsource (lib "eagle-import") (part "TS3USB30E"))
    )
    (comp (ref "U23")
      (value "TS3USB30E")
      (footprint "eagle-import:UQFN-10")
      (libsource (lib "eagle-import") (part "TS3USB30E"))
    )
    (comp (ref "U24")
      (value "TS3USB30E")
      (footprint "eagle-import:UQFN-10")
      (libsource (lib "eagle-import") (part "TS3USB30E"))
    )
    (comp (ref "U25")
      (value "TS3USB30E")
      (footprint "eagle-import:UQFN-10")
      (libsource (lib "eagle-import") (part "TS3USB30E"))
    )
  )
  (nets
    (net (code "1") (name "CONT_MOD0_IN") (class "Default")
      (node (ref "J3") (pin "9") (pinfunction "MOD0_IN_9") (pintype "bidirectional"))
      (node (ref "U8") (pin "2") (pinfunction "A1_2") (pintype "bidirectional"))
    )
    (net (code "2") (name "CONT_MOD0_OUT") (class "Default")
      (node (ref "J3") (pin "10") (pinfunction "MOD0_OUT_10") (pintype "bidirectional"))
      (node (ref "U14") (pin "2") (pinfunction "A1_2") (pintype "bidirectional"))
    )
    (net (code "3") (name "CONT_MOD1_IN") (class "Default")
      (node (ref "J3") (pin "11") (pinfunction "MOD1_IN_11") (pintype "bidirectional"))
      (node (ref "U9") (pin "2") (pinfunction "A1_2") (pintype "bidirectional"))
    )
    (net (code "4") (name "CONT_MOD1_OUT") (class "Default")
      (node (ref "J3") (pin "12") (pinfunction "MOD1_OUT_12") (pintype "bidirectional"))
      (node (ref "U15") (pin "2") (pinfunction "A1_2") (pintype "bidirectional"))
    )
    (net (code "5") (name "CONT_MOD2_IN") (class "Default")
      (node (ref "J3") (pin "13") (pinfunction "MOD2_IN_13") (pintype "bidirectional"))
      (node (ref "U10") (pin "2") (pinfunction "A1_2") (pintype "bidirectional"))
    )
    (net (code "6") (name "CONT_MOD2_OUT") (class "Default")
      (node (ref "J3") (pin "14") (pinfunction "MOD2_OUT_14") (pintype "bidirectional"))
      (node (ref "U16") (pin "2") (pinfunction "A1_2") (pintype "bidirectional"))
    )
    (net (code "7") (name "CONT_MOD5_IN") (class "Default")
      (node (ref "J3") (pin "15") (pinfunction "MOD5_IN_15") (pintype "bidirectional"))
      (node (ref "U11") (pin "2") (pinfunction "A1_2") (pintype "bidirectional"))
    )
    (net (code "8") (name "CONT_MOD5_OUT") (class "Default")
      (node (ref "J3") (pin "16") (pinfunction "MOD5_OUT_16") (pintype "bidirectional"))
      (node (ref "U17") (pin "2") (pinfunction "A1_2") (pintype "bidirectional"))
    )
    (net (code "9") (name "CONT_MOD6_IN") (class "Default")
      (node (ref "J3") (pin "17") (pinfunction "MOD6_IN_17") (pintype "bidirectional"))
      (node (ref "U12") (pin "2") (pinfunction "A1_2") (pintype "bidirectional"))
    )
    (net (code "10") (name "CONT_MOD6_OUT") (class "Default")
      (node (ref "J3") (pin "18") (pinfunction "MOD6_OUT_18") (pintype "bidirectional"))
      (node (ref "U18") (pin "2") (pinfunction "A1_2") (pintype "bidirectional"))
    )
    (net (code "11") (name "CONT_MOD7_IN") (class "Default")
      (node (ref "J3") (pin "19") (pinfunction "MOD7_IN_19") (pintype "bidirectional"))
      (node (ref "U13") (pin "2") (pinfunction "A1_2") (pintype "bidirectional"))
    )
    (net (code "12") (name "CONT_MOD7_OUT") (class "Default")
      (node (ref "J3") (pin "20") (pinfunction "MOD7_OUT_20") (pintype "bidirectional"))
      (node (ref "U19") (pin "2") (pinfunction "A1_2") (pintype "bidirectional"))
    )
    (net (code "13") (name "CONT_USB+") (class "Default")
      (node (ref "J3") (pin "27") (pinfunction "USB_D+_27") (pintype "bidirectional"))
      (node (ref "R25") (pin "1") (pinfunction "1_1") (pintype "passive"))
      (node (ref "U1") (pin "3") (pinfunction "DP0_3") (pintype "bidirectional"))
    )
    (net (code "14") (name "CONT_USB-") (class "Default")
      (node (ref "J3") (pin "28") (pinfunction "USB_D-_28") (pintype "bidirectional"))
      (node (ref "U1") (pin "4") (pinfunction "DM0_4") (pintype "bidirectional"))
    )
    (net (code "15") (name "GND") (class "Default")
      (node (ref "C1") (pin "1") (pinfunction "1_1") (pintype "bidirectional"))
      (node (ref "C10") (pin "2") (pinfunction "2_2") (pintype "bidirectional"))
      (node (ref "C100") (pin "2") (pinfunction "2_2") (pintype "bidirectional"))
      (node (ref "C11") (pin "2") (pinfunction "2_2") (pintype "bidirectional"))
      (node (ref "C12") (pin "2") (pinfunction "2_2") (pintype "bidirectional"))
      (node (ref "C13") (pin "2") (pinfunction "2_2") (pintype "bidirectional"))
      (node (ref "C14") (pin "2") (pinfunction "2_2") (pintype "bidirectional"))
      (node (ref "C15") (pin "2") (pinfunction "2_2") (pintype "bidirectional"))
      (node (ref "C16") (pin "2") (pinfunction "2_2") (pintype "bidirectional"))
      (node (ref "C17") (pin "2") (pinfunction "2_2") (pintype "bidirectional"))
      (node (ref "C18") (pin "2") (pinfunction "2_2") (pintype "bidirectional"))
      (node (ref "C19") (pin "2") (pinfunction "2_2") (pintype "bidirectional"))
      (node (ref "C2") (pin "1") (pinfunction "1_1") (pintype "bidirectional"))
      (node (ref "C20") (pin "2") (pinfunction "2_2") (pintype "bidirectional"))
      (node (ref "C21") (pin "2") (pinfunction "2_2") (pintype "bidirectional"))
      (node (ref "C22") (pin "2") (pinfunction "2_2") (pintype "bidirectional"))
      (node (ref "C23") (pin "2") (pinfunction "2_2") (pintype "bidirectional"))
      (node (ref "C24") (pin "2") (pinfunction "2_2") (pintype "bidirectional"))
      (node (ref "C25") (pin "2") (pinfunction "2_2") (pintype "bidirectional"))
      (node (ref "C26") (pin "2") (pinfunction "2_2") (pintype "bidirectional"))
      (node (ref "C27") (pin "2") (pinfunction "2_2") (pintype "bidirectional"))
      (node (ref "C28") (pin "2") (pinfunction "2_2") (pintype "bidirectional"))
      (node (ref "C29") (pin "2") (pinfunction "2_2") (pintype "bidirectional"))
      (node (ref "C3") (pin "2") (pinfunction "2_2") (pintype "bidirectional"))
      (node (ref "C30") (pin "2") (pinfunction "2_2") (pintype "bidirectional"))
      (node (ref "C31") (pin "2") (pinfunction "2_2") (pintype "bidirectional"))
      (node (ref "C32") (pin "2") (pinfunction "2_2") (pintype "bidirectional"))
      (node (ref "C33") (pin "2") (pinfunction "2_2") (pintype "bidirectional"))
      (node (ref "C34") (pin "2") (pinfunction "2_2") (pintype "bidirectional"))
      (node (ref "C35") (pin "2") (pinfunction "2_2") (pintype "bidirectional"))
      (node (ref "C36") (pin "2") (pinfunction "2_2") (pintype "bidirectional"))
      (node (ref "C37") (pin "2") (pinfunction "2_2") (pintype "bidirectional"))
      (node (ref "C38") (pin "2") (pinfunction "2_2") (pintype "bidirectional"))
      (node (ref "C39") (pin "2") (pinfunction "2_2") (pintype "bidirectional"))
      (node (ref "C4") (pin "2") (pinfunction "2_2") (pintype "bidirectional"))
      (node (ref "C40") (pin "2") (pinfunction "2_2") (pintype "bidirectional"))
      (node (ref "C41") (pin "2") (pinfunction "2_2") (pintype "bidirectional"))
      (node (ref "C42") (pin "2") (pinfunction "2_2") (pintype "bidirectional"))
      (node (ref "C43") (pin "2") (pinfunction "2_2") (pintype "bidirectional"))
      (node (ref "C44") (pin "2") (pinfunction "2_2") (pintype "bidirectional"))
      (node (ref "C45") (pin "2") (pinfunction "2_2") (pintype "bidirectional"))
      (node (ref "C46") (pin "2") (pinfunction "2_2") (pintype "bidirectional"))
      (node (ref "C47") (pin "2") (pinfunction "2_2") (pintype "bidirectional"))
      (node (ref "C48") (pin "2") (pinfunction "2_2") (pintype "bidirectional"))
      (node (ref "C49") (pin "2") (pinfunction "2_2") (pintype "bidirectional"))
      (node (ref "C5") (pin "2") (pinfunction "2_2") (pintype "bidirectional"))
      (node (ref "C50") (pin "2") (pinfunction "2_2") (pintype "bidirectional"))
      (node (ref "C51") (pin "2") (pinfunction "2_2") (pintype "bidirectional"))
      (node (ref "C52") (pin "2") (pinfunction "2_2") (pintype "bidirectional"))
      (node (ref "C53") (pin "2") (pinfunction "2_2") (pintype "bidirectional"))
      (node (ref "C54") (pin "2") (pinfunction "2_2") (pintype "bidirectional"))
      (node (ref "C55") (pin "2") (pinfunction "2_2") (pintype "bidirectional"))
      (node (ref "C56") (pin "2") (pinfunction "2_2") (pintype "bidirectional"))
      (node (ref "C57") (pin "2") (pinfunction "2_2") (pintype "bidirectional"))
      (node (ref "C58") (pin "2") (pinfunction "2_2") (pintype "bidirectional"))
      (node (ref "C59") (pin "2") (pinfunction "2_2") (pintype "bidirectional"))
      (node (ref "C6") (pin "2") (pinfunction "2_2") (pintype "bidirectional"))
      (node (ref "C60") (pin "2") (pinfunction "2_2") (pintype "bidirectional"))
      (node (ref "C61") (pin "2") (pinfunction "2_2") (pintype "bidirectional"))
      (node (ref "C62") (pin "2") (pinfunction "2_2") (pintype "bidirectional"))
      (node (ref "C63") (pin "1") (pinfunction "1_1") (pintype "bidirectional"))
      (node (ref "C64") (pin "1") (pinfunction "1_1") (pintype "bidirectional"))
      (node (ref "C65") (pin "1") (pinfunction "1_1") (pintype "bidirectional"))
      (node (ref "C66") (pin "1") (pinfunction "1_1") (pintype "bidirectional"))
      (node (ref "C67") (pin "1") (pinfunction "1_1") (pintype "bidirectional"))
      (node (ref "C68") (pin "1") (pinfunction "1_1") (pintype "bidirectional"))
      (node (ref "C69") (pin "1") (pinfunction "1_1") (pintype "bidirectional"))
      (node (ref "C7") (pin "2") (pinfunction "2_2") (pintype "bidirectional"))
      (node (ref "C70") (pin "2") (pinfunction "2_2") (pintype "bidirectional"))
      (node (ref "C71") (pin "2") (pinfunction "2_2") (pintype "bidirectional"))
      (node (ref "C72") (pin "2") (pinfunction "2_2") (pintype "bidirectional"))
      (node (ref "C73") (pin "2") (pinfunction "2_2") (pintype "bidirectional"))
      (node (ref "C74") (pin "2") (pinfunction "2_2") (pintype "bidirectional"))
      (node (ref "C75") (pin "2") (pinfunction "2_2") (pintype "bidirectional"))
      (node (ref "C76") (pin "2") (pinfunction "2_2") (pintype "bidirectional"))
      (node (ref "C77") (pin "2") (pinfunction "2_2") (pintype "bidirectional"))
      (node (ref "C78") (pin "2") (pinfunction "2_2") (pintype "bidirectional"))
      (node (ref "C79") (pin "2") (pinfunction "2_2") (pintype "bidirectional"))
      (node (ref "C8") (pin "2") (pinfunction "2_2") (pintype "bidirectional"))
      (node (ref "C80") (pin "2") (pinfunction "2_2") (pintype "bidirectional"))
      (node (ref "C81") (pin "2") (pinfunction "2_2") (pintype "bidirectional"))
      (node (ref "C82") (pin "2") (pinfunction "2_2") (pintype "bidirectional"))
      (node (ref "C83") (pin "2") (pinfunction "2_2") (pintype "bidirectional"))
      (node (ref "C84") (pin "2") (pinfunction "2_2") (pintype "bidirectional"))
      (node (ref "C85") (pin "2") (pinfunction "2_2") (pintype "bidirectional"))
      (node (ref "C86") (pin "2") (pinfunction "2_2") (pintype "bidirectional"))
      (node (ref "C87") (pin "2") (pinfunction "2_2") (pintype "bidirectional"))
      (node (ref "C88") (pin "2") (pinfunction "2_2") (pintype "bidirectional"))
      (node (ref "C89") (pin "2") (pinfunction "2_2") (pintype "bidirectional"))
      (node (ref "C9") (pin "2") (pinfunction "2_2") (pintype "bidirectional"))
      (node (ref "C90") (pin "2") (pinfunction "2_2") (pintype "bidirectional"))
      (node (ref "C91") (pin "2") (pinfunction "2_2") (pintype "bidirectional"))
      (node (ref "C92") (pin "2") (pinfunction "2_2") (pintype "bidirectional"))
      (node (ref "C93") (pin "2") (pinfunction "2_2") (pintype "bidirectional"))
      (node (ref "C94") (pin "1") (pinfunction "1_1") (pintype "bidirectional"))
      (node (ref "C95") (pin "2") (pinfunction "2_2") (pintype "bidirectional"))
      (node (ref "C96") (pin "2") (pinfunction "2_2") (pintype "bidirectional"))
      (node (ref "C97") (pin "2") (pinfunction "2_2") (pintype "bidirectional"))
      (node (ref "C98") (pin "2") (pinfunction "2_2") (pintype "bidirectional"))
      (node (ref "C99") (pin "2") (pinfunction "2_2") (pintype "bidirectional"))
      (node (ref "D1") (pin "1") (pinfunction "GND_1") (pintype "bidirectional"))
      (node (ref "D1") (pin "3") (pinfunction "GND_3") (pintype "bidirectional"))
      (node (ref "D1") (pin "5") (pinfunction "GND_5") (pintype "bidirectional"))
      (node (ref "D1") (pin "7") (pinfunction "GND_7") (pintype "bidirectional"))
      (node (ref "D2") (pin "1") (pinfunction "GND_1") (pintype "bidirectional"))
      (node (ref "D2") (pin "3") (pinfunction "GND_3") (pintype "bidirectional"))
      (node (ref "D2") (pin "5") (pinfunction "GND_5") (pintype "bidirectional"))
      (node (ref "D2") (pin "7") (pinfunction "GND_7") (pintype "bidirectional"))
      (node (ref "D3") (pin "1") (pinfunction "GND_1") (pintype "bidirectional"))
      (node (ref "D3") (pin "3") (pinfunction "GND_3") (pintype "bidirectional"))
      (node (ref "D3") (pin "5") (pinfunction "GND_5") (pintype "bidirectional"))
      (node (ref "D3") (pin "7") (pinfunction "GND_7") (pintype "bidirectional"))
      (node (ref "D4") (pin "1") (pinfunction "GND_1") (pintype "bidirectional"))
      (node (ref "D4") (pin "3") (pinfunction "GND_3") (pintype "bidirectional"))
      (node (ref "D4") (pin "5") (pinfunction "GND_5") (pintype "bidirectional"))
      (node (ref "D4") (pin "7") (pinfunction "GND_7") (pintype "bidirectional"))
      (node (ref "J0") (pin "1") (pinfunction "GND_1") (pintype "bidirectional"))
      (node (ref "J0") (pin "14") (pinfunction "GND_14") (pintype "bidirectional"))
      (node (ref "J1") (pin "1") (pinfunction "GND_1") (pintype "bidirectional"))
      (node (ref "J1") (pin "14") (pinfunction "GND_14") (pintype "bidirectional"))
      (node (ref "J2") (pin "1") (pinfunction "GND_1") (pintype "bidirectional"))
      (node (ref "J2") (pin "14") (pinfunction "GND_14") (pintype "bidirectional"))
      (node (ref "J3") (pin "1") (pinfunction "GND_1") (pintype "bidirectional"))
      (node (ref "J3") (pin "21") (pinfunction "GND_21") (pintype "bidirectional"))
      (node (ref "J4") (pin "1") (pinfunction "GND_1") (pintype "power_in"))
      (node (ref "J5") (pin "1") (pinfunction "GND_1") (pintype "bidirectional"))
      (node (ref "J5") (pin "14") (pinfunction "GND_14") (pintype "bidirectional"))
      (node (ref "J6") (pin "1") (pinfunction "GND_1") (pintype "bidirectional"))
      (node (ref "J6") (pin "14") (pinfunction "GND_14") (pintype "bidirectional"))
      (node (ref "J7") (pin "1") (pinfunction "GND_1") (pintype "bidirectional"))
      (node (ref "J7") (pin "14") (pinfunction "GND_14") (pintype "bidirectional"))
      (node (ref "LED1001") (pin "C") (pinfunction "CATHODE_C") (pintype "bidirectional"))
      (node (ref "LED1002") (pin "C") (pinfunction "CATHODE_C") (pintype "bidirectional"))
      (node (ref "LED1003") (pin "C") (pinfunction "CATHODE_C") (pintype "bidirectional"))
      (node (ref "LED1007") (pin "C") (pinfunction "CATHODE_C") (pintype "bidirectional"))
      (node (ref "LED1008") (pin "C") (pinfunction "CATHODE_C") (pintype "bidirectional"))
      (node (ref "LED1009") (pin "C") (pinfunction "CATHODE_C") (pintype "bidirectional"))
      (node (ref "LED1013") (pin "C") (pinfunction "CATHODE_C") (pintype "bidirectional"))
      (node (ref "LED1014") (pin "C") (pinfunction "CATHODE_C") (pintype "bidirectional"))
      (node (ref "LED1015") (pin "C") (pinfunction "CATHODE_C") (pintype "bidirectional"))
      (node (ref "R1004") (pin "1") (pinfunction "1_1") (pintype "passive"))
      (node (ref "R1005") (pin "1") (pinfunction "1_1") (pintype "passive"))
      (node (ref "R1006") (pin "1") (pinfunction "1_1") (pintype "passive"))
      (node (ref "R1010") (pin "1") (pinfunction "1_1") (pintype "passive"))
      (node (ref "R1011") (pin "1") (pinfunction "1_1") (pintype "passive"))
      (node (ref "R1012") (pin "1") (pinfunction "1_1") (pintype "passive"))
      (node (ref "R1016") (pin "1") (pinfunction "1_1") (pintype "passive"))
      (node (ref "R1017") (pin "1") (pinfunction "1_1") (pintype "passive"))
      (node (ref "R1018") (pin "1") (pinfunction "1_1") (pintype "passive"))
      (node (ref "R13") (pin "2") (pinfunction "2_2") (pintype "passive"))
      (node (ref "R14") (pin "2") (pinfunction "2_2") (pintype "passive"))
      (node (ref "R15") (pin "2") (pinfunction "2_2") (pintype "passive"))
      (node (ref "R16") (pin "2") (pinfunction "2_2") (pintype "passive"))
      (node (ref "R17") (pin "2") (pinfunction "2_2") (pintype "passive"))
      (node (ref "R18") (pin "2") (pinfunction "2_2") (pintype "passive"))
      (node (ref "R19") (pin "2") (pinfunction "2_2") (pintype "passive"))
      (node (ref "R20") (pin "2") (pinfunction "2_2") (pintype "passive"))
      (node (ref "R21") (pin "2") (pinfunction "2_2") (pintype "passive"))
      (node (ref "R22") (pin "2") (pinfunction "2_2") (pintype "passive"))
      (node (ref "R23") (pin "2") (pinfunction "2_2") (pintype "passive"))
      (node (ref "R24") (pin "2") (pinfunction "2_2") (pintype "passive"))
      (node (ref "R50") (pin "1") (pinfunction "1_1") (pintype "passive"))
      (node (ref "R51") (pin "1") (pinfunction "1_1") (pintype "passive"))
      (node (ref "R52") (pin "1") (pinfunction "1_1") (pintype "passive"))
      (node (ref "R53") (pin "1") (pinfunction "1_1") (pintype "passive"))
      (node (ref "R54") (pin "1") (pinfunction "1_1") (pintype "passive"))
      (node (ref "R55") (pin "1") (pinfunction "1_1") (pintype "passive"))
      (node (ref "R56") (pin "1") (pinfunction "1_1") (pintype "passive"))
      (node (ref "R57") (pin "1") (pinfunction "1_1") (pintype "passive"))
      (node (ref "R58") (pin "1") (pinfunction "1_1") (pintype "passive"))
      (node (ref "R59") (pin "1") (pinfunction "1_1") (pintype "passive"))
      (node (ref "R60") (pin "1") (pinfunction "1_1") (pintype "passive"))
      (node (ref "R61") (pin "1") (pinfunction "1_1") (pintype "passive"))
      (node (ref "R62") (pin "1") (pinfunction "1_1") (pintype "passive"))
      (node (ref "R63") (pin "1") (pinfunction "1_1") (pintype "passive"))
      (node (ref "R64") (pin "1") (pinfunction "1_1") (pintype "passive"))
      (node (ref "R65") (pin "1") (pinfunction "1_1") (pintype "passive"))
      (node (ref "R66") (pin "1") (pinfunction "1_1") (pintype "passive"))
      (node (ref "R67") (pin "1") (pinfunction "1_1") (pintype "passive"))
      (node (ref "R68") (pin "1") (pinfunction "1_1") (pintype "passive"))
      (node (ref "R69") (pin "1") (pinfunction "1_1") (pintype "passive"))
      (node (ref "R70") (pin "1") (pinfunction "1_1") (pintype "passive"))
      (node (ref "R71") (pin "1") (pinfunction "1_1") (pintype "passive"))
      (node (ref "R72") (pin "1") (pinfunction "1_1") (pintype "passive"))
      (node (ref "R73") (pin "1") (pinfunction "1_1") (pintype "passive"))
      (node (ref "R74") (pin "1") (pinfunction "1_1") (pintype "passive"))
      (node (ref "R75") (pin "1") (pinfunction "1_1") (pintype "passive"))
      (node (ref "R76") (pin "1") (pinfunction "1_1") (pintype "passive"))
      (node (ref "R77") (pin "1") (pinfunction "1_1") (pintype "passive"))
      (node (ref "R78") (pin "1") (pinfunction "1_1") (pintype "passive"))
      (node (ref "R79") (pin "1") (pinfunction "1_1") (pintype "passive"))
      (node (ref "R80") (pin "1") (pinfunction "1_1") (pintype "passive"))
      (node (ref "S1") (pin "2") (pinfunction "GND_2") (pintype "bidirectional"))
      (node (ref "S1") (pin "PAD") (pinfunction "GND_PAD") (pintype "bidirectional"))
      (node (ref "S10") (pin "2") (pinfunction "GND_2") (pintype "bidirectional"))
      (node (ref "S11") (pin "2") (pinfunction "GND_2") (pintype "bidirectional"))
      (node (ref "S12") (pin "2") (pinfunction "GND_2") (pintype "bidirectional"))
      (node (ref "S13") (pin "1") (pinfunction "GND_1") (pintype "bidirectional"))
      (node (ref "S13") (pin "PAD") (pinfunction "GND_PAD") (pintype "bidirectional"))
      (node (ref "S14") (pin "1") (pinfunction "GND_1") (pintype "bidirectional"))
      (node (ref "S14") (pin "PAD") (pinfunction "GND_PAD") (pintype "bidirectional"))
      (node (ref "S15") (pin "1") (pinfunction "GND_1") (pintype "bidirectional"))
      (node (ref "S15") (pin "PAD") (pinfunction "GND_PAD") (pintype "bidirectional"))
      (node (ref "S16") (pin "1") (pinfunction "GND_1") (pintype "bidirectional"))
      (node (ref "S16") (pin "PAD") (pinfunction "GND_PAD") (pintype "bidirectional"))
      (node (ref "S17") (pin "1") (pinfunction "GND_1") (pintype "bidirectional"))
      (node (ref "S17") (pin "PAD") (pinfunction "GND_PAD") (pintype "bidirectional"))
      (node (ref "S18") (pin "1") (pinfunction "GND_1") (pintype "bidirectional"))
      (node (ref "S18") (pin "PAD") (pinfunction "GND_PAD") (pintype "bidirectional"))
      (node (ref "S2") (pin "2") (pinfunction "GND_2") (pintype "bidirectional"))
      (node (ref "S2") (pin "PAD") (pinfunction "GND_PAD") (pintype "bidirectional"))
      (node (ref "S3") (pin "2") (pinfunction "GND_2") (pintype "bidirectional"))
      (node (ref "S3") (pin "PAD") (pinfunction "GND_PAD") (pintype "bidirectional"))
      (node (ref "S4") (pin "2") (pinfunction "GND_2") (pintype "bidirectional"))
      (node (ref "S4") (pin "PAD") (pinfunction "GND_PAD") (pintype "bidirectional"))
      (node (ref "S5") (pin "2") (pinfunction "GND_2") (pintype "bidirectional"))
      (node (ref "S5") (pin "PAD") (pinfunction "GND_PAD") (pintype "bidirectional"))
      (node (ref "S6") (pin "2") (pinfunction "GND_2") (pintype "bidirectional"))
      (node (ref "S6") (pin "PAD") (pinfunction "GND_PAD") (pintype "bidirectional"))
      (node (ref "S7") (pin "2") (pinfunction "GND_2") (pintype "bidirectional"))
      (node (ref "S8") (pin "2") (pinfunction "GND_2") (pintype "bidirectional"))
      (node (ref "S9") (pin "2") (pinfunction "GND_2") (pintype "bidirectional"))
      (node (ref "TP10") (pin "TESTPOINT") (pinfunction "TESTPOINT_TESTPOINT") (pintype "bidirectional"))
      (node (ref "TP24") (pin "TESTPOINT") (pinfunction "TESTPOINT_TESTPOINT") (pintype "bidirectional"))
      (node (ref "TP25") (pin "TESTPOINT") (pinfunction "TESTPOINT_TESTPOINT") (pintype "bidirectional"))
      (node (ref "TP26") (pin "TESTPOINT") (pinfunction "TESTPOINT_TESTPOINT") (pintype "bidirectional"))
      (node (ref "TP4") (pin "TESTPOINT") (pinfunction "TESTPOINT_TESTPOINT") (pintype "bidirectional"))
      (node (ref "TP7") (pin "TESTPOINT") (pinfunction "TESTPOINT_TESTPOINT") (pintype "bidirectional"))
      (node (ref "U1") (pin "10") (pinfunction "~{BUSPWR}_10") (pintype "bidirectional"))
      (node (ref "U1") (pin "24") (pinfunction "GND_24") (pintype "bidirectional"))
      (node (ref "U1") (pin "43") (pinfunction "GND_43") (pintype "bidirectional"))
      (node (ref "U1") (pin "48") (pinfunction "MODE_48") (pintype "bidirectional"))
      (node (ref "U1") (pin "5") (pinfunction "GND_5") (pintype "bidirectional"))
      (node (ref "U10") (pin "4") (pinfunction "GND_4") (pintype "bidirectional"))
      (node (ref "U11") (pin "4") (pinfunction "GND_4") (pintype "bidirectional"))
      (node (ref "U12") (pin "4") (pinfunction "GND_4") (pintype "bidirectional"))
      (node (ref "U13") (pin "4") (pinfunction "GND_4") (pintype "bidirectional"))
      (node (ref "U14") (pin "4") (pinfunction "GND_4") (pintype "bidirectional"))
      (node (ref "U14") (pin "5") (pinfunction "DIR_5") (pintype "bidirectional"))
      (node (ref "U15") (pin "4") (pinfunction "GND_4") (pintype "bidirectional"))
      (node (ref "U15") (pin "5") (pinfunction "DIR_5") (pintype "bidirectional"))
      (node (ref "U16") (pin "4") (pinfunction "GND_4") (pintype "bidirectional"))
      (node (ref "U16") (pin "5") (pinfunction "DIR_5") (pintype "bidirectional"))
      (node (ref "U17") (pin "4") (pinfunction "GND_4") (pintype "bidirectional"))
      (node (ref "U17") (pin "5") (pinfunction "DIR_5") (pintype "bidirectional"))
      (node (ref "U18") (pin "4") (pinfunction "GND_4") (pintype "bidirectional"))
      (node (ref "U19") (pin "4") (pinfunction "GND_4") (pintype "bidirectional"))
      (node (ref "U19") (pin "5") (pinfunction "DIR_5") (pintype "bidirectional"))
      (node (ref "U2") (pin "4") (pinfunction "GND_4") (pintype "bidirectional"))
      (node (ref "U20") (pin "10") (pinfunction "S_10") (pintype "bidirectional"))
      (node (ref "U20") (pin "4") (pinfunction "GND_4") (pintype "bidirectional"))
      (node (ref "U21") (pin "10") (pinfunction "S_10") (pintype "bidirectional"))
      (node (ref "U21") (pin "4") (pinfunction "GND_4") (pintype "bidirectional"))
      (node (ref "U22") (pin "10") (pinfunction "S_10") (pintype "bidirectional"))
      (node (ref "U22") (pin "4") (pinfunction "GND_4") (pintype "bidirectional"))
      (node (ref "U23") (pin "10") (pinfunction "S_10") (pintype "bidirectional"))
      (node (ref "U23") (pin "4") (pinfunction "GND_4") (pintype "bidirectional"))
      (node (ref "U24") (pin "10") (pinfunction "S_10") (pintype "bidirectional"))
      (node (ref "U24") (pin "4") (pinfunction "GND_4") (pintype "bidirectional"))
      (node (ref "U25") (pin "10") (pinfunction "S_10") (pintype "bidirectional"))
      (node (ref "U25") (pin "4") (pinfunction "GND_4") (pintype "bidirectional"))
      (node (ref "U26") (pin "3") (pinfunction "A2_3") (pintype "bidirectional"))
      (node (ref "U26") (pin "4") (pinfunction "A1_4") (pintype "bidirectional"))
      (node (ref "U26") (pin "5") (pinfunction "A0_5") (pintype "bidirectional"))
      (node (ref "U26") (pin "9") (pinfunction "GND_9") (pintype "bidirectional"))
      (node (ref "U27") (pin "3") (pinfunction "A2_3") (pintype "bidirectional"))
      (node (ref "U27") (pin "4") (pinfunction "A1_4") (pintype "bidirectional"))
      (node (ref "U27") (pin "9") (pinfunction "GND_9") (pintype "bidirectional"))
      (node (ref "U28") (pin "3") (pinfunction "A2_3") (pintype "bidirectional"))
      (node (ref "U28") (pin "5") (pinfunction "A0_5") (pintype "bidirectional"))
      (node (ref "U28") (pin "9") (pinfunction "GND_9") (pintype "bidirectional"))
      (node (ref "U29") (pin "4") (pinfunction "A1_4") (pintype "bidirectional"))
      (node (ref "U29") (pin "9") (pinfunction "GND_9") (pintype "bidirectional"))
      (node (ref "U3") (pin "4") (pinfunction "GND_4") (pintype "bidirectional"))
      (node (ref "U30") (pin "5") (pinfunction "A0_5") (pintype "bidirectional"))
      (node (ref "U30") (pin "9") (pinfunction "GND_9") (pintype "bidirectional"))
      (node (ref "U31") (pin "9") (pinfunction "GND_9") (pintype "bidirectional"))
      (node (ref "U4") (pin "4") (pinfunction "GND_4") (pintype "bidirectional"))
      (node (ref "U5") (pin "4") (pinfunction "GND_4") (pintype "bidirectional"))
      (node (ref "U6") (pin "4") (pinfunction "GND_4") (pintype "bidirectional"))
      (node (ref "U7") (pin "4") (pinfunction "GND_4") (pintype "bidirectional"))
      (node (ref "U8") (pin "4") (pinfunction "GND_4") (pintype "bidirectional"))
      (node (ref "U9") (pin "4") (pinfunction "GND_4") (pintype "bidirectional"))
    )
    (net (code "16") (name "HUB_CFG") (class "Default")
      (node (ref "TP27") (pin "TESTPOINT") (pinfunction "TESTPOINT_TESTPOINT") (pintype "bidirectional"))
      (node (ref "U1") (pin "40") (pinfunction "HUBCFG_40") (pintype "bidirectional"))
    )
    (net (code "17") (name "HUB_DM1") (class "Default")
      (node (ref "C6") (pin "1") (pinfunction "1_1") (pintype "bidirectional"))
      (node (ref "R4") (pin "1") (pinfunction "1_1") (pintype "passive"))
      (node (ref "U1") (pin "13") (pinfunction "DM1_13") (pintype "bidirectional"))
    )
    (net (code "18") (name "HUB_DM2") (class "Default")
      (node (ref "C4") (pin "1") (pinfunction "1_1") (pintype "bidirectional"))
      (node (ref "R2") (pin "1") (pinfunction "1_1") (pintype "passive"))
      (node (ref "U1") (pin "17") (pinfunction "DM2_17") (pintype "bidirectional"))
    )
    (net (code "19") (name "HUB_DM3") (class "Default")
      (node (ref "C8") (pin "1") (pinfunction "1_1") (pintype "bidirectional"))
      (node (ref "R6") (pin "1") (pinfunction "1_1") (pintype "passive"))
      (node (ref "U1") (pin "21") (pinfunction "DM3_21") (pintype "bidirectional"))
    )
    (net (code "20") (name "HUB_DM4") (class "Default")
      (node (ref "C12") (pin "1") (pinfunction "1_1") (pintype "bidirectional"))
      (node (ref "R10") (pin "1") (pinfunction "1_1") (pintype "passive"))
      (node (ref "U1") (pin "26") (pinfunction "DM4_26") (pintype "bidirectional"))
    )
    (net (code "21") (name "HUB_DM5") (class "Default")
      (node (ref "U1") (pin "30") (pinfunction "DM5_30") (pintype "bidirectional"))
    )
    (net (code "22") (name "HUB_DM6") (class "Default")
      (node (ref "C14") (pin "1") (pinfunction "1_1") (pintype "bidirectional"))
      (node (ref "R12") (pin "1") (pinfunction "1_1") (pintype "passive"))
      (node (ref "U1") (pin "34") (pinfunction "DM6_34") (pintype "bidirectional"))
    )
    (net (code "23") (name "HUB_DM7") (class "Default")
      (node (ref "C10") (pin "1") (pinfunction "1_1") (pintype "bidirectional"))
      (node (ref "R8") (pin "1") (pinfunction "1_1") (pintype "passive"))
      (node (ref "U1") (pin "38") (pinfunction "DM7_38") (pintype "bidirectional"))
    )
    (net (code "24") (name "HUB_DP1") (class "Default")
      (node (ref "C5") (pin "1") (pinfunction "1_1") (pintype "bidirectional"))
      (node (ref "R3") (pin "1") (pinfunction "1_1") (pintype "passive"))
      (node (ref "U1") (pin "14") (pinfunction "DP1_14") (pintype "bidirectional"))
    )
    (net (code "25") (name "HUB_DP2") (class "Default")
      (node (ref "C3") (pin "1") (pinfunction "1_1") (pintype "bidirectional"))
      (node (ref "R1") (pin "1") (pinfunction "1_1") (pintype "passive"))
      (node (ref "U1") (pin "18") (pinfunction "DP2_18") (pintype "bidirectional"))
    )
    (net (code "26") (name "HUB_DP3") (class "Default")
      (node (ref "C7") (pin "1") (pinfunction "1_1") (pintype "bidirectional"))
      (node (ref "R5") (pin "1") (pinfunction "1_1") (pintype "passive"))
      (node (ref "U1") (pin "22") (pinfunction "DP3_22") (pintype "bidirectional"))
    )
    (net (code "27") (name "HUB_DP4") (class "Default")
      (node (ref "C11") (pin "1") (pinfunction "1_1") (pintype "bidirectional"))
      (node (ref "R9") (pin "1") (pinfunction "1_1") (pintype "passive"))
      (node (ref "U1") (pin "27") (pinfunction "DP4_27") (pintype "bidirectional"))
    )
    (net (code "28") (name "HUB_DP5") (class "Default")
      (node (ref "U1") (pin "31") (pinfunction "DP5_31") (pintype "bidirectional"))
    )
    (net (code "29") (name "HUB_DP6") (class "Default")
      (node (ref "C13") (pin "1") (pinfunction "1_1") (pintype "bidirectional"))
      (node (ref "R11") (pin "1") (pinfunction "1_1") (pintype "passive"))
      (node (ref "U1") (pin "35") (pinfunction "DP6_35") (pintype "bidirectional"))
    )
    (net (code "30") (name "HUB_DP7") (class "Default")
      (node (ref "C9") (pin "1") (pinfunction "1_1") (pintype "bidirectional"))
      (node (ref "R7") (pin "1") (pinfunction "1_1") (pintype "passive"))
      (node (ref "U1") (pin "39") (pinfunction "DP7_39") (pintype "bidirectional"))
    )
    (net (code "31") (name "HUB_PORTDIS") (class "Default")
      (node (ref "TP29") (pin "TESTPOINT") (pinfunction "TESTPOINT_TESTPOINT") (pintype "bidirectional"))
      (node (ref "U1") (pin "42") (pinfunction "PORTDIS_42") (pintype "bidirectional"))
    )
    (net (code "32") (name "HUB_PORTPWR") (class "Default")
      (node (ref "TP28") (pin "TESTPOINT") (pinfunction "TESTPOINT_TESTPOINT") (pintype "bidirectional"))
      (node (ref "U1") (pin "41") (pinfunction "PORTPWR_41") (pintype "bidirectional"))
    )
    (net (code "33") (name "HUB_~{OVRCUR1}") (class "Default")
      (node (ref "R28") (pin "1") (pinfunction "1_1") (pintype "passive"))
      (node (ref "S14") (pin "5") (pinfunction "~{FLG}_5") (pintype "bidirectional"))
      (node (ref "TP31") (pin "TESTPOINT") (pinfunction "TESTPOINT_TESTPOINT") (pintype "bidirectional"))
      (node (ref "U1") (pin "12") (pinfunction "~{OVRCUR1}_12") (pintype "bidirectional"))
    )
    (net (code "34") (name "HUB_~{OVRCUR2}") (class "Default")
      (node (ref "R27") (pin "1") (pinfunction "1_1") (pintype "passive"))
      (node (ref "S13") (pin "5") (pinfunction "~{FLG}_5") (pintype "bidirectional"))
      (node (ref "TP33") (pin "TESTPOINT") (pinfunction "TESTPOINT_TESTPOINT") (pintype "bidirectional"))
      (node (ref "U1") (pin "16") (pinfunction "~{OVRCUR2}_16") (pintype "bidirectional"))
    )
    (net (code "35") (name "HUB_~{OVRCUR3}") (class "Default")
      (node (ref "R29") (pin "1") (pinfunction "1_1") (pintype "passive"))
      (node (ref "S15") (pin "5") (pinfunction "~{FLG}_5") (pintype "bidirectional"))
      (node (ref "TP35") (pin "TESTPOINT") (pinfunction "TESTPOINT_TESTPOINT") (pintype "bidirectional"))
      (node (ref "U1") (pin "20") (pinfunction "~{OVRCUR3}_20") (pintype "bidirectional"))
    )
    (net (code "36") (name "HUB_~{OVRCUR4}") (class "Default")
      (node (ref "R31") (pin "1") (pinfunction "1_1") (pintype "passive"))
      (node (ref "S17") (pin "5") (pinfunction "~{FLG}_5") (pintype "bidirectional"))
      (node (ref "TP37") (pin "TESTPOINT") (pinfunction "TESTPOINT_TESTPOINT") (pintype "bidirectional"))
      (node (ref "U1") (pin "25") (pinfunction "~{OVRCUR4}_25") (pintype "bidirectional"))
    )
    (net (code "37") (name "HUB_~{OVRCUR5}") (class "Default")
      (node (ref "U1") (pin "29") (pinfunction "~{OVRCUR5}_29") (pintype "bidirectional"))
    )
    (net (code "38") (name "HUB_~{OVRCUR6}") (class "Default")
      (node (ref "R32") (pin "1") (pinfunction "1_1") (pintype "passive"))
      (node (ref "S18") (pin "5") (pinfunction "~{FLG}_5") (pintype "bidirectional"))
      (node (ref "TP39") (pin "TESTPOINT") (pinfunction "TESTPOINT_TESTPOINT") (pintype "bidirectional"))
      (node (ref "U1") (pin "33") (pinfunction "~{OVRCUR6}_33") (pintype "bidirectional"))
    )
    (net (code "39") (name "HUB_~{OVRCUR7}") (class "Default")
      (node (ref "R30") (pin "1") (pinfunction "1_1") (pintype "passive"))
      (node (ref "S16") (pin "5") (pinfunction "~{FLG}_5") (pintype "bidirectional"))
      (node (ref "TP41") (pin "TESTPOINT") (pinfunction "TESTPOINT_TESTPOINT") (pintype "bidirectional"))
      (node (ref "U1") (pin "37") (pinfunction "~{OVRCUR7}_37") (pintype "bidirectional"))
    )
    (net (code "40") (name "HUB_~{PWRON1}") (class "Default")
      (node (ref "S8") (pin "1") (pinfunction "I1_1") (pintype "bidirectional"))
      (node (ref "TP30") (pin "TESTPOINT") (pinfunction "TESTPOINT_TESTPOINT") (pintype "bidirectional"))
      (node (ref "U1") (pin "11") (pinfunction "~{PWRON1}_11") (pintype "bidirectional"))
    )
    (net (code "41") (name "HUB_~{PWRON2}") (class "Default")
      (node (ref "S7") (pin "1") (pinfunction "I1_1") (pintype "bidirectional"))
      (node (ref "TP32") (pin "TESTPOINT") (pinfunction "TESTPOINT_TESTPOINT") (pintype "bidirectional"))
      (node (ref "U1") (pin "15") (pinfunction "~{PWRON2}_15") (pintype "bidirectional"))
    )
    (net (code "42") (name "HUB_~{PWRON3}") (class "Default")
      (node (ref "S9") (pin "1") (pinfunction "I1_1") (pintype "bidirectional"))
      (node (ref "TP34") (pin "TESTPOINT") (pinfunction "TESTPOINT_TESTPOINT") (pintype "bidirectional"))
      (node (ref "U1") (pin "19") (pinfunction "~{PWRON3}_19") (pintype "bidirectional"))
    )
    (net (code "43") (name "HUB_~{PWRON4}") (class "Default")
      (node (ref "S11") (pin "1") (pinfunction "I1_1") (pintype "bidirectional"))
      (node (ref "TP36") (pin "TESTPOINT") (pinfunction "TESTPOINT_TESTPOINT") (pintype "bidirectional"))
      (node (ref "U1") (pin "23") (pinfunction "~{PWRON4}_23") (pintype "bidirectional"))
    )
    (net (code "44") (name "HUB_~{PWRON5}") (class "Default")
      (node (ref "U1") (pin "28") (pinfunction "~{PWRON5}_28") (pintype "bidirectional"))
    )
    (net (code "45") (name "HUB_~{PWRON6}") (class "Default")
      (node (ref "S12") (pin "1") (pinfunction "I1_1") (pintype "bidirectional"))
      (node (ref "TP38") (pin "TESTPOINT") (pinfunction "TESTPOINT_TESTPOINT") (pintype "bidirectional"))
      (node (ref "U1") (pin "32") (pinfunction "~{PWRON6}_32") (pintype "bidirectional"))
    )
    (net (code "46") (name "HUB_~{PWRON7}") (class "Default")
      (node (ref "S10") (pin "1") (pinfunction "I1_1") (pintype "bidirectional"))
      (node (ref "TP40") (pin "TESTPOINT") (pinfunction "TESTPOINT_TESTPOINT") (pintype "bidirectional"))
      (node (ref "U1") (pin "36") (pinfunction "~{PWRON7}_36") (pintype "bidirectional"))
    )
    (net (code "47") (name "MOD0_5V") (class "Default")
      (node (ref "C33") (pin "1") (pinfunction "1_1") (pintype "bidirectional"))
      (node (ref "J0") (pin "2") (pinfunction "5V_2") (pintype "bidirectional"))
      (node (ref "S1") (pin "1") (pinfunction "VLOAD_1") (pintype "bidirectional"))
    )
    (net (code "48") (name "MOD0_5V_METERED") (class "Default")
      (node (ref "C76") (pin "1") (pinfunction "1_1") (pintype "bidirectional"))
      (node (ref "C88") (pin "1") (pinfunction "1_1") (pintype "bidirectional"))
      (node (ref "J4") (pin "7") (pinfunction "VCC_MOD0_7") (pintype "power_in"))
      (node (ref "S1") (pin "3") (pinfunction "VSUPP_3") (pintype "bidirectional"))
      (node (ref "S13") (pin "2") (pinfunction "IN_2") (pintype "bidirectional"))
      (node (ref "S13") (pin "3") (pinfunction "IN_3") (pintype "bidirectional"))
      (node (ref "TP15") (pin "TESTPOINT") (pinfunction "TESTPOINT_TESTPOINT") (pintype "bidirectional"))
    )
    (net (code "49") (name "MOD0_D+_HUB-SW") (class "Default")
      (node (ref "D1") (pin "4") (pinfunction "D_4") (pintype "bidirectional"))
      (node (ref "R1") (pin "2") (pinfunction "2_2") (pintype "passive"))
      (node (ref "R50") (pin "2") (pinfunction "2_2") (pintype "passive"))
      (node (ref "U20") (pin "3") (pinfunction "D+_3") (pintype "bidirectional"))
    )
    (net (code "50") (name "MOD0_D-_HUB-SW") (class "Default")
      (node (ref "D1") (pin "2") (pinfunction "C_2") (pintype "bidirectional"))
      (node (ref "R2") (pin "2") (pinfunction "2_2") (pintype "passive"))
      (node (ref "R51") (pin "2") (pinfunction "2_2") (pintype "passive"))
      (node (ref "U20") (pin "5") (pinfunction "D-_5") (pintype "bidirectional"))
    )
    (net (code "51") (name "MOD0_IN") (class "Default")
      (node (ref "J0") (pin "10") (pinfunction "MOD_IN_10") (pintype "bidirectional"))
      (node (ref "U8") (pin "7") (pinfunction "B1_7") (pintype "bidirectional"))
    )
    (net (code "52") (name "MOD0_ISO_I2C") (class "Default")
      (node (ref "R1002") (pin "2") (pinfunction "2_2") (pintype "passive"))
      (node (ref "R63") (pin "2") (pinfunction "2_2") (pintype "passive"))
      (node (ref "TP1002") (pin "TESTPOINT") (pinfunction "TESTPOINT_TESTPOINT") (pintype "bidirectional"))
      (node (ref "U2") (pin "5") (pinfunction "OE_5") (pintype "bidirectional"))
      (node (ref "U26") (pin "11") (pinfunction "P1_11") (pintype "bidirectional"))
    )
    (net (code "53") (name "MOD0_ISO_POWER") (class "Default")
      (node (ref "R1001") (pin "2") (pinfunction "2_2") (pintype "passive"))
      (node (ref "R62") (pin "2") (pinfunction "2_2") (pintype "passive"))
      (node (ref "S1") (pin "4") (pinfunction "EN_4") (pintype "bidirectional"))
      (node (ref "TP1001") (pin "TESTPOINT") (pinfunction "TESTPOINT_TESTPOINT") (pintype "bidirectional"))
      (node (ref "U26") (pin "10") (pinfunction "P0_10") (pintype "bidirectional"))
    )
    (net (code "54") (name "MOD0_ISO_USB") (class "Default")
      (node (ref "R1003") (pin "2") (pinfunction "2_2") (pintype "passive"))
      (node (ref "R64") (pin "2") (pinfunction "2_2") (pintype "passive"))
      (node (ref "S7") (pin "6") (pinfunction "S_6") (pintype "bidirectional"))
      (node (ref "TP1003") (pin "TESTPOINT") (pinfunction "TESTPOINT_TESTPOINT") (pintype "bidirectional"))
      (node (ref "U20") (pin "8") (pinfunction "~{OE}_8") (pintype "bidirectional"))
      (node (ref "U26") (pin "12") (pinfunction "P2_12") (pintype "bidirectional"))
    )
    (net (code "55") (name "MOD0_OUT") (class "Default")
      (node (ref "J0") (pin "8") (pinfunction "MOD_OUT_8") (pintype "bidirectional"))
      (node (ref "U14") (pin "7") (pinfunction "B1_7") (pintype "bidirectional"))
    )
    (net (code "56") (name "MOD0_PPS") (class "Default")
      (node (ref "J0") (pin "7") (pinfunction "PPS_7") (pintype "bidirectional"))
      (node (ref "U8") (pin "6") (pinfunction "B2_6") (pintype "bidirectional"))
    )
    (net (code "57") (name "MOD0_SCL") (class "Default")
      (node (ref "J0") (pin "5") (pinfunction "SCL_5") (pintype "bidirectional"))
      (node (ref "R34") (pin "2") (pinfunction "2_2") (pintype "passive"))
      (node (ref "U2") (pin "6") (pinfunction "B1_6") (pintype "bidirectional"))
    )
    (net (code "58") (name "MOD0_SDA") (class "Default")
      (node (ref "J0") (pin "6") (pinfunction "SDA_6") (pintype "bidirectional"))
      (node (ref "R33") (pin "2") (pinfunction "2_2") (pintype "passive"))
      (node (ref "U2") (pin "7") (pinfunction "B0_7") (pintype "bidirectional"))
    )
    (net (code "59") (name "MOD0_USB+") (class "Default")
      (node (ref "J0") (pin "11") (pinfunction "USB_D+_11") (pintype "bidirectional"))
      (node (ref "U20") (pin "1") (pinfunction "D1+_1") (pintype "bidirectional"))
    )
    (net (code "60") (name "MOD0_USB-") (class "Default")
      (node (ref "J0") (pin "12") (pinfunction "USB_D-_12") (pintype "bidirectional"))
      (node (ref "U20") (pin "7") (pinfunction "D1-_7") (pintype "bidirectional"))
    )
    (net (code "61") (name "MOD0_USB_VBUS") (class "Default")
      (node (ref "C77") (pin "1") (pinfunction "1_1") (pintype "bidirectional"))
      (node (ref "C95") (pin "1") (pinfunction "1_1") (pintype "bidirectional"))
      (node (ref "J0") (pin "13") (pinfunction "USB_VBUS_13") (pintype "bidirectional"))
      (node (ref "S13") (pin "6") (pinfunction "OUT_6") (pintype "bidirectional"))
      (node (ref "S13") (pin "7") (pinfunction "OUT_7") (pintype "bidirectional"))
    )
    (net (code "62") (name "MOD0_USB_~{EN}") (class "Default")
      (node (ref "S13") (pin "4") (pinfunction "~{EN}_4") (pintype "bidirectional"))
      (node (ref "S7") (pin "4") (pinfunction "Z_4") (pintype "bidirectional"))
    )
    (net (code "63") (name "MOD0_VCCIO") (class "Default")
      (node (ref "C22") (pin "1") (pinfunction "1_1") (pintype "bidirectional"))
      (node (ref "C40") (pin "1") (pinfunction "1_1") (pintype "bidirectional"))
      (node (ref "C52") (pin "1") (pinfunction "1_1") (pintype "bidirectional"))
      (node (ref "J0") (pin "4") (pinfunction "VCCIO_4") (pintype "bidirectional"))
      (node (ref "R33") (pin "1") (pinfunction "1_1") (pintype "passive"))
      (node (ref "R34") (pin "1") (pinfunction "1_1") (pintype "passive"))
      (node (ref "U14") (pin "8") (pinfunction "VCC_B_8") (pintype "bidirectional"))
      (node (ref "U2") (pin "8") (pinfunction "VCC_B_8") (pintype "bidirectional"))
      (node (ref "U8") (pin "8") (pinfunction "VCC_B_8") (pintype "bidirectional"))
    )
    (net (code "64") (name "MOD1_5V") (class "Default")
      (node (ref "C34") (pin "1") (pinfunction "1_1") (pintype "bidirectional"))
      (node (ref "J1") (pin "2") (pinfunction "5V_2") (pintype "bidirectional"))
      (node (ref "S2") (pin "1") (pinfunction "VLOAD_1") (pintype "bidirectional"))
    )
    (net (code "65") (name "MOD1_5V_METERED") (class "Default")
      (node (ref "C78") (pin "1") (pinfunction "1_1") (pintype "bidirectional"))
      (node (ref "C89") (pin "1") (pinfunction "1_1") (pintype "bidirectional"))
      (node (ref "J4") (pin "8") (pinfunction "VCC_MOD1_8") (pintype "power_in"))
      (node (ref "S14") (pin "2") (pinfunction "IN_2") (pintype "bidirectional"))
      (node (ref "S14") (pin "3") (pinfunction "IN_3") (pintype "bidirectional"))
      (node (ref "S2") (pin "3") (pinfunction "VSUPP_3") (pintype "bidirectional"))
      (node (ref "TP16") (pin "TESTPOINT") (pinfunction "TESTPOINT_TESTPOINT") (pintype "bidirectional"))
    )
    (net (code "66") (name "MOD1_D+_HUB-SW") (class "Default")
      (node (ref "D1") (pin "8") (pinfunction "A_8") (pintype "bidirectional"))
      (node (ref "R3") (pin "2") (pinfunction "2_2") (pintype "passive"))
      (node (ref "R52") (pin "2") (pinfunction "2_2") (pintype "passive"))
      (node (ref "U21") (pin "3") (pinfunction "D+_3") (pintype "bidirectional"))
    )
    (net (code "67") (name "MOD1_D-_HUB-SW") (class "Default")
      (node (ref "D1") (pin "6") (pinfunction "B_6") (pintype "bidirectional"))
      (node (ref "R4") (pin "2") (pinfunction "2_2") (pintype "passive"))
      (node (ref "R53") (pin "2") (pinfunction "2_2") (pintype "passive"))
      (node (ref "U21") (pin "5") (pinfunction "D-_5") (pintype "bidirectional"))
    )
    (net (code "68") (name "MOD1_IN") (class "Default")
      (node (ref "J1") (pin "10") (pinfunction "MOD_IN_10") (pintype "bidirectional"))
      (node (ref "U9") (pin "7") (pinfunction "B1_7") (pintype "bidirectional"))
    )
    (net (code "69") (name "MOD1_ISO_I2C") (class "Default")
      (node (ref "LED1005") (pin "A") (pinfunction "ANODE_A") (pintype "bidirectional"))
      (node (ref "R66") (pin "2") (pinfunction "2_2") (pintype "passive"))
      (node (ref "TP1005") (pin "TESTPOINT") (pinfunction "TESTPOINT_TESTPOINT") (pintype "bidirectional"))
      (node (ref "U27") (pin "11") (pinfunction "P1_11") (pintype "bidirectional"))
      (node (ref "U3") (pin "5") (pinfunction "OE_5") (pintype "bidirectional"))
    )
    (net (code "70") (name "MOD1_ISO_POWER") (class "Default")
      (node (ref "LED1004") (pin "A") (pinfunction "ANODE_A") (pintype "bidirectional"))
      (node (ref "R65") (pin "2") (pinfunction "2_2") (pintype "passive"))
      (node (ref "S2") (pin "4") (pinfunction "EN_4") (pintype "bidirectional"))
      (node (ref "TP1004") (pin "TESTPOINT") (pinfunction "TESTPOINT_TESTPOINT") (pintype "bidirectional"))
      (node (ref "U27") (pin "10") (pinfunction "P0_10") (pintype "bidirectional"))
    )
    (net (code "71") (name "MOD1_ISO_USB") (class "Default")
      (node (ref "LED1006") (pin "A") (pinfunction "ANODE_A") (pintype "bidirectional"))
      (node (ref "R67") (pin "2") (pinfunction "2_2") (pintype "passive"))
      (node (ref "S8") (pin "6") (pinfunction "S_6") (pintype "bidirectional"))
      (node (ref "TP1006") (pin "TESTPOINT") (pinfunction "TESTPOINT_TESTPOINT") (pintype "bidirectional"))
      (node (ref "U21") (pin "8") (pinfunction "~{OE}_8") (pintype "bidirectional"))
      (node (ref "U27") (pin "12") (pinfunction "P2_12") (pintype "bidirectional"))
    )
    (net (code "72") (name "MOD1_OUT") (class "Default")
      (node (ref "J1") (pin "8") (pinfunction "MOD_OUT_8") (pintype "bidirectional"))
      (node (ref "U15") (pin "7") (pinfunction "B1_7") (pintype "bidirectional"))
    )
    (net (code "73") (name "MOD1_PPS") (class "Default")
      (node (ref "J1") (pin "7") (pinfunction "PPS_7") (pintype "bidirectional"))
      (node (ref "U9") (pin "6") (pinfunction "B2_6") (pintype "bidirectional"))
    )
    (net (code "74") (name "MOD1_SCL") (class "Default")
      (node (ref "J1") (pin "5") (pinfunction "SCL_5") (pintype "bidirectional"))
      (node (ref "R36") (pin "2") (pinfunction "2_2") (pintype "passive"))
      (node (ref "U3") (pin "6") (pinfunction "B1_6") (pintype "bidirectional"))
    )
    (net (code "75") (name "MOD1_SDA") (class "Default")
      (node (ref "J1") (pin "6") (pinfunction "SDA_6") (pintype "bidirectional"))
      (node (ref "R35") (pin "2") (pinfunction "2_2") (pintype "passive"))
      (node (ref "U3") (pin "7") (pinfunction "B0_7") (pintype "bidirectional"))
    )
    (net (code "76") (name "MOD1_USB+") (class "Default")
      (node (ref "J1") (pin "11") (pinfunction "USB_D+_11") (pintype "bidirectional"))
      (node (ref "U21") (pin "1") (pinfunction "D1+_1") (pintype "bidirectional"))
    )
    (net (code "77") (name "MOD1_USB-") (class "Default")
      (node (ref "J1") (pin "12") (pinfunction "USB_D-_12") (pintype "bidirectional"))
      (node (ref "U21") (pin "7") (pinfunction "D1-_7") (pintype "bidirectional"))
    )
    (net (code "78") (name "MOD1_USB_VBUS") (class "Default")
      (node (ref "C79") (pin "1") (pinfunction "1_1") (pintype "bidirectional"))
      (node (ref "C96") (pin "1") (pinfunction "1_1") (pintype "bidirectional"))
      (node (ref "J1") (pin "13") (pinfunction "USB_VBUS_13") (pintype "bidirectional"))
      (node (ref "S14") (pin "6") (pinfunction "OUT_6") (pintype "bidirectional"))
      (node (ref "S14") (pin "7") (pinfunction "OUT_7") (pintype "bidirectional"))
    )
    (net (code "79") (name "MOD1_USB_~{EN}") (class "Default")
      (node (ref "S14") (pin "4") (pinfunction "~{EN}_4") (pintype "bidirectional"))
      (node (ref "S8") (pin "4") (pinfunction "Z_4") (pintype "bidirectional"))
    )
    (net (code "80") (name "MOD1_VCCIO") (class "Default")
      (node (ref "C24") (pin "1") (pinfunction "1_1") (pintype "bidirectional"))
      (node (ref "C42") (pin "1") (pinfunction "1_1") (pintype "bidirectional"))
      (node (ref "C54") (pin "1") (pinfunction "1_1") (pintype "bidirectional"))
      (node (ref "J1") (pin "4") (pinfunction "VCCIO_4") (pintype "bidirectional"))
      (node (ref "R35") (pin "1") (pinfunction "1_1") (pintype "passive"))
      (node (ref "R36") (pin "1") (pinfunction "1_1") (pintype "passive"))
      (node (ref "U15") (pin "8") (pinfunction "VCC_B_8") (pintype "bidirectional"))
      (node (ref "U3") (pin "8") (pinfunction "VCC_B_8") (pintype "bidirectional"))
      (node (ref "U9") (pin "8") (pinfunction "VCC_B_8") (pintype "bidirectional"))
    )
    (net (code "81") (name "MOD2_5V") (class "Default")
      (node (ref "C35") (pin "1") (pinfunction "1_1") (pintype "bidirectional"))
      (node (ref "J2") (pin "2") (pinfunction "5V_2") (pintype "bidirectional"))
      (node (ref "S3") (pin "1") (pinfunction "VLOAD_1") (pintype "bidirectional"))
    )
    (net (code "82") (name "MOD2_5V_METERED") (class "Default")
      (node (ref "C80") (pin "1") (pinfunction "1_1") (pintype "bidirectional"))
      (node (ref "C90") (pin "1") (pinfunction "1_1") (pintype "bidirectional"))
      (node (ref "J4") (pin "9") (pinfunction "VCC_MOD2_9") (pintype "power_in"))
      (node (ref "S15") (pin "2") (pinfunction "IN_2") (pintype "bidirectional"))
      (node (ref "S15") (pin "3") (pinfunction "IN_3") (pintype "bidirectional"))
      (node (ref "S3") (pin "3") (pinfunction "VSUPP_3") (pintype "bidirectional"))
      (node (ref "TP17") (pin "TESTPOINT") (pinfunction "TESTPOINT_TESTPOINT") (pintype "bidirectional"))
    )
    (net (code "83") (name "MOD2_D+_HUB-SW") (class "Default")
      (node (ref "D2") (pin "8") (pinfunction "A_8") (pintype "bidirectional"))
      (node (ref "R5") (pin "2") (pinfunction "2_2") (pintype "passive"))
      (node (ref "R54") (pin "2") (pinfunction "2_2") (pintype "passive"))
      (node (ref "U22") (pin "3") (pinfunction "D+_3") (pintype "bidirectional"))
    )
    (net (code "84") (name "MOD2_D-_HUB-SW") (class "Default")
      (node (ref "D2") (pin "6") (pinfunction "B_6") (pintype "bidirectional"))
      (node (ref "R55") (pin "2") (pinfunction "2_2") (pintype "passive"))
      (node (ref "R6") (pin "2") (pinfunction "2_2") (pintype "passive"))
      (node (ref "U22") (pin "5") (pinfunction "D-_5") (pintype "bidirectional"))
    )
    (net (code "85") (name "MOD2_IN") (class "Default")
      (node (ref "J2") (pin "10") (pinfunction "MOD_IN_10") (pintype "bidirectional"))
      (node (ref "U10") (pin "7") (pinfunction "B1_7") (pintype "bidirectional"))
    )
    (net (code "86") (name "MOD2_ISO_I2C") (class "Default")
      (node (ref "R1008") (pin "2") (pinfunction "2_2") (pintype "passive"))
      (node (ref "R69") (pin "2") (pinfunction "2_2") (pintype "passive"))
      (node (ref "TP1008") (pin "TESTPOINT") (pinfunction "TESTPOINT_TESTPOINT") (pintype "bidirectional"))
      (node (ref "U28") (pin "11") (pinfunction "P1_11") (pintype "bidirectional"))
      (node (ref "U4") (pin "5") (pinfunction "OE_5") (pintype "bidirectional"))
    )
    (net (code "87") (name "MOD2_ISO_POWER") (class "Default")
      (node (ref "R1007") (pin "2") (pinfunction "2_2") (pintype "passive"))
      (node (ref "R68") (pin "2") (pinfunction "2_2") (pintype "passive"))
      (node (ref "S3") (pin "4") (pinfunction "EN_4") (pintype "bidirectional"))
      (node (ref "TP1007") (pin "TESTPOINT") (pinfunction "TESTPOINT_TESTPOINT") (pintype "bidirectional"))
      (node (ref "U28") (pin "10") (pinfunction "P0_10") (pintype "bidirectional"))
    )
    (net (code "88") (name "MOD2_ISO_USB") (class "Default")
      (node (ref "R1009") (pin "2") (pinfunction "2_2") (pintype "passive"))
      (node (ref "R70") (pin "2") (pinfunction "2_2") (pintype "passive"))
      (node (ref "S9") (pin "6") (pinfunction "S_6") (pintype "bidirectional"))
      (node (ref "TP1009") (pin "TESTPOINT") (pinfunction "TESTPOINT_TESTPOINT") (pintype "bidirectional"))
      (node (ref "U22") (pin "8") (pinfunction "~{OE}_8") (pintype "bidirectional"))
      (node (ref "U28") (pin "12") (pinfunction "P2_12") (pintype "bidirectional"))
    )
    (net (code "89") (name "MOD2_OUT") (class "Default")
      (node (ref "J2") (pin "8") (pinfunction "MOD_OUT_8") (pintype "bidirectional"))
      (node (ref "U16") (pin "7") (pinfunction "B1_7") (pintype "bidirectional"))
    )
    (net (code "90") (name "MOD2_PPS") (class "Default")
      (node (ref "J2") (pin "7") (pinfunction "PPS_7") (pintype "bidirectional"))
      (node (ref "U10") (pin "6") (pinfunction "B2_6") (pintype "bidirectional"))
    )
    (net (code "91") (name "MOD2_SCL") (class "Default")
      (node (ref "J2") (pin "5") (pinfunction "SCL_5") (pintype "bidirectional"))
      (node (ref "R38") (pin "2") (pinfunction "2_2") (pintype "passive"))
      (node (ref "U4") (pin "6") (pinfunction "B1_6") (pintype "bidirectional"))
    )
    (net (code "92") (name "MOD2_SDA") (class "Default")
      (node (ref "J2") (pin "6") (pinfunction "SDA_6") (pintype "bidirectional"))
      (node (ref "R37") (pin "2") (pinfunction "2_2") (pintype "passive"))
      (node (ref "U4") (pin "7") (pinfunction "B0_7") (pintype "bidirectional"))
    )
    (net (code "93") (name "MOD2_USB+") (class "Default")
      (node (ref "J2") (pin "11") (pinfunction "USB_D+_11") (pintype "bidirectional"))
      (node (ref "U22") (pin "1") (pinfunction "D1+_1") (pintype "bidirectional"))
    )
    (net (code "94") (name "MOD2_USB-") (class "Default")
      (node (ref "J2") (pin "12") (pinfunction "USB_D-_12") (pintype "bidirectional"))
      (node (ref "U22") (pin "7") (pinfunction "D1-_7") (pintype "bidirectional"))
    )
    (net (code "95") (name "MOD2_USB_VBUS") (class "Default")
      (node (ref "C81") (pin "1") (pinfunction "1_1") (pintype "bidirectional"))
      (node (ref "C97") (pin "1") (pinfunction "1_1") (pintype "bidirectional"))
      (node (ref "J2") (pin "13") (pinfunction "USB_VBUS_13") (pintype "bidirectional"))
      (node (ref "S15") (pin "6") (pinfunction "OUT_6") (pintype "bidirectional"))
      (node (ref "S15") (pin "7") (pinfunction "OUT_7") (pintype "bidirectional"))
    )
    (net (code "96") (name "MOD2_USB_~{EN}") (class "Default")
      (node (ref "S15") (pin "4") (pinfunction "~{EN}_4") (pintype "bidirectional"))
      (node (ref "S9") (pin "4") (pinfunction "Z_4") (pintype "bidirectional"))
    )
    (net (code "97") (name "MOD2_VCCIO") (class "Default")
      (node (ref "C26") (pin "1") (pinfunction "1_1") (pintype "bidirectional"))
      (node (ref "C44") (pin "1") (pinfunction "1_1") (pintype "bidirectional"))
      (node (ref "C56") (pin "1") (pinfunction "1_1") (pintype "bidirectional"))
      (node (ref "J2") (pin "4") (pinfunction "VCCIO_4") (pintype "bidirectional"))
      (node (ref "R37") (pin "1") (pinfunction "1_1") (pintype "passive"))
      (node (ref "R38") (pin "1") (pinfunction "1_1") (pintype "passive"))
      (node (ref "U10") (pin "8") (pinfunction "VCC_B_8") (pintype "bidirectional"))
      (node (ref "U16") (pin "8") (pinfunction "VCC_B_8") (pintype "bidirectional"))
      (node (ref "U4") (pin "8") (pinfunction "VCC_B_8") (pintype "bidirectional"))
    )
    (net (code "98") (name "MOD5_5V") (class "Default")
      (node (ref "C36") (pin "1") (pinfunction "1_1") (pintype "bidirectional"))
      (node (ref "J5") (pin "2") (pinfunction "5V_2") (pintype "bidirectional"))
      (node (ref "S4") (pin "1") (pinfunction "VLOAD_1") (pintype "bidirectional"))
    )
    (net (code "99") (name "MOD5_5V_METERED") (class "Default")
      (node (ref "C82") (pin "1") (pinfunction "1_1") (pintype "bidirectional"))
      (node (ref "C91") (pin "1") (pinfunction "1_1") (pintype "bidirectional"))
      (node (ref "J4") (pin "10") (pinfunction "VCC_MOD5_10") (pintype "power_in"))
      (node (ref "S16") (pin "2") (pinfunction "IN_2") (pintype "bidirectional"))
      (node (ref "S16") (pin "3") (pinfunction "IN_3") (pintype "bidirectional"))
      (node (ref "S4") (pin "3") (pinfunction "VSUPP_3") (pintype "bidirectional"))
      (node (ref "TP18") (pin "TESTPOINT") (pinfunction "TESTPOINT_TESTPOINT") (pintype "bidirectional"))
    )
    (net (code "100") (name "MOD5_D+_HUB-SW") (class "Default")
      (node (ref "D3") (pin "2") (pinfunction "C_2") (pintype "bidirectional"))
      (node (ref "R56") (pin "2") (pinfunction "2_2") (pintype "passive"))
      (node (ref "R7") (pin "2") (pinfunction "2_2") (pintype "passive"))
      (node (ref "U23") (pin "3") (pinfunction "D+_3") (pintype "bidirectional"))
    )
    (net (code "101") (name "MOD5_D-_HUB-SW") (class "Default")
      (node (ref "D3") (pin "4") (pinfunction "D_4") (pintype "bidirectional"))
      (node (ref "R57") (pin "2") (pinfunction "2_2") (pintype "passive"))
      (node (ref "R8") (pin "2") (pinfunction "2_2") (pintype "passive"))
      (node (ref "U23") (pin "5") (pinfunction "D-_5") (pintype "bidirectional"))
    )
    (net (code "102") (name "MOD5_IN") (class "Default")
      (node (ref "J5") (pin "10") (pinfunction "MOD_IN_10") (pintype "bidirectional"))
      (node (ref "U11") (pin "7") (pinfunction "B1_7") (pintype "bidirectional"))
    )
    (net (code "103") (name "MOD5_ISO_I2C") (class "Default")
      (node (ref "LED1011") (pin "A") (pinfunction "ANODE_A") (pintype "bidirectional"))
      (node (ref "R72") (pin "2") (pinfunction "2_2") (pintype "passive"))
      (node (ref "TP1011") (pin "TESTPOINT") (pinfunction "TESTPOINT_TESTPOINT") (pintype "bidirectional"))
      (node (ref "U29") (pin "11") (pinfunction "P1_11") (pintype "bidirectional"))
      (node (ref "U5") (pin "5") (pinfunction "OE_5") (pintype "bidirectional"))
    )
    (net (code "104") (name "MOD5_ISO_POWER") (class "Default")
      (node (ref "LED1010") (pin "A") (pinfunction "ANODE_A") (pintype "bidirectional"))
      (node (ref "R71") (pin "2") (pinfunction "2_2") (pintype "passive"))
      (node (ref "S4") (pin "4") (pinfunction "EN_4") (pintype "bidirectional"))
      (node (ref "TP1010") (pin "TESTPOINT") (pinfunction "TESTPOINT_TESTPOINT") (pintype "bidirectional"))
      (node (ref "U29") (pin "10") (pinfunction "P0_10") (pintype "bidirectional"))
    )
    (net (code "105") (name "MOD5_ISO_USB") (class "Default")
      (node (ref "LED1012") (pin "A") (pinfunction "ANODE_A") (pintype "bidirectional"))
      (node (ref "R73") (pin "2") (pinfunction "2_2") (pintype "passive"))
      (node (ref "S10") (pin "6") (pinfunction "S_6") (pintype "bidirectional"))
      (node (ref "TP1012") (pin "TESTPOINT") (pinfunction "TESTPOINT_TESTPOINT") (pintype "bidirectional"))
      (node (ref "U23") (pin "8") (pinfunction "~{OE}_8") (pintype "bidirectional"))
      (node (ref "U29") (pin "12") (pinfunction "P2_12") (pintype "bidirectional"))
    )
    (net (code "106") (name "MOD5_OUT") (class "Default")
      (node (ref "J5") (pin "8") (pinfunction "MOD_OUT_8") (pintype "bidirectional"))
      (node (ref "U17") (pin "7") (pinfunction "B1_7") (pintype "bidirectional"))
    )
    (net (code "107") (name "MOD5_PPS") (class "Default")
      (node (ref "J5") (pin "7") (pinfunction "PPS_7") (pintype "bidirectional"))
      (node (ref "U11") (pin "6") (pinfunction "B2_6") (pintype "bidirectional"))
    )
    (net (code "108") (name "MOD5_SCL") (class "Default")
      (node (ref "J5") (pin "5") (pinfunction "SCL_5") (pintype "bidirectional"))
      (node (ref "R40") (pin "2") (pinfunction "2_2") (pintype "passive"))
      (node (ref "U5") (pin "6") (pinfunction "B1_6") (pintype "bidirectional"))
    )
    (net (code "109") (name "MOD5_SDA") (class "Default")
      (node (ref "J5") (pin "6") (pinfunction "SDA_6") (pintype "bidirectional"))
      (node (ref "R39") (pin "2") (pinfunction "2_2") (pintype "passive"))
      (node (ref "U5") (pin "7") (pinfunction "B0_7") (pintype "bidirectional"))
    )
    (net (code "110") (name "MOD5_USB+") (class "Default")
      (node (ref "J5") (pin "11") (pinfunction "USB_D+_11") (pintype "bidirectional"))
      (node (ref "U23") (pin "1") (pinfunction "D1+_1") (pintype "bidirectional"))
    )
    (net (code "111") (name "MOD5_USB-") (class "Default")
      (node (ref "J5") (pin "12") (pinfunction "USB_D-_12") (pintype "bidirectional"))
      (node (ref "U23") (pin "7") (pinfunction "D1-_7") (pintype "bidirectional"))
    )
    (net (code "112") (name "MOD5_USB_VBUS") (class "Default")
      (node (ref "C83") (pin "1") (pinfunction "1_1") (pintype "bidirectional"))
      (node (ref "C98") (pin "1") (pinfunction "1_1") (pintype "bidirectional"))
      (node (ref "J5") (pin "13") (pinfunction "USB_VBUS_13") (pintype "bidirectional"))
      (node (ref "S16") (pin "6") (pinfunction "OUT_6") (pintype "bidirectional"))
      (node (ref "S16") (pin "7") (pinfunction "OUT_7") (pintype "bidirectional"))
    )
    (net (code "113") (name "MOD5_USB_~{EN}") (class "Default")
      (node (ref "S10") (pin "4") (pinfunction "Z_4") (pintype "bidirectional"))
      (node (ref "S16") (pin "4") (pinfunction "~{EN}_4") (pintype "bidirectional"))
    )
    (net (code "114") (name "MOD5_VCCIO") (class "Default")
      (node (ref "C28") (pin "1") (pinfunction "1_1") (pintype "bidirectional"))
      (node (ref "C46") (pin "1") (pinfunction "1_1") (pintype "bidirectional"))
      (node (ref "C58") (pin "1") (pinfunction "1_1") (pintype "bidirectional"))
      (node (ref "J5") (pin "4") (pinfunction "VCCIO_4") (pintype "bidirectional"))
      (node (ref "R39") (pin "1") (pinfunction "1_1") (pintype "passive"))
      (node (ref "R40") (pin "1") (pinfunction "1_1") (pintype "passive"))
      (node (ref "U11") (pin "8") (pinfunction "VCC_B_8") (pintype "bidirectional"))
      (node (ref "U17") (pin "8") (pinfunction "VCC_B_8") (pintype "bidirectional"))
      (node (ref "U5") (pin "8") (pinfunction "VCC_B_8") (pintype "bidirectional"))
    )
    (net (code "115") (name "MOD6_5V") (class "Default")
      (node (ref "C37") (pin "1") (pinfunction "1_1") (pintype "bidirectional"))
      (node (ref "J6") (pin "2") (pinfunction "5V_2") (pintype "bidirectional"))
      (node (ref "S5") (pin "1") (pinfunction "VLOAD_1") (pintype "bidirectional"))
    )
    (net (code "116") (name "MOD6_5V_METERED") (class "Default")
      (node (ref "C84") (pin "1") (pinfunction "1_1") (pintype "bidirectional"))
      (node (ref "C92") (pin "1") (pinfunction "1_1") (pintype "bidirectional"))
      (node (ref "J4") (pin "11") (pinfunction "VCC_MOD6_11") (pintype "power_in"))
      (node (ref "S17") (pin "2") (pinfunction "IN_2") (pintype "bidirectional"))
      (node (ref "S17") (pin "3") (pinfunction "IN_3") (pintype "bidirectional"))
      (node (ref "S5") (pin "3") (pinfunction "VSUPP_3") (pintype "bidirectional"))
      (node (ref "TP19") (pin "TESTPOINT") (pinfunction "TESTPOINT_TESTPOINT") (pintype "bidirectional"))
    )
    (net (code "117") (name "MOD6_D+_HUB-SW") (class "Default")
      (node (ref "D4") (pin "8") (pinfunction "A_8") (pintype "bidirectional"))
      (node (ref "R58") (pin "2") (pinfunction "2_2") (pintype "passive"))
      (node (ref "R9") (pin "2") (pinfunction "2_2") (pintype "passive"))
      (node (ref "U24") (pin "3") (pinfunction "D+_3") (pintype "bidirectional"))
    )
    (net (code "118") (name "MOD6_D-_HUB-SW") (class "Default")
      (node (ref "D4") (pin "6") (pinfunction "B_6") (pintype "bidirectional"))
      (node (ref "R10") (pin "2") (pinfunction "2_2") (pintype "passive"))
      (node (ref "R59") (pin "2") (pinfunction "2_2") (pintype "passive"))
      (node (ref "U24") (pin "5") (pinfunction "D-_5") (pintype "bidirectional"))
    )
    (net (code "119") (name "MOD6_IN") (class "Default")
      (node (ref "J6") (pin "10") (pinfunction "MOD_IN_10") (pintype "bidirectional"))
      (node (ref "U12") (pin "7") (pinfunction "B1_7") (pintype "bidirectional"))
    )
    (net (code "120") (name "MOD6_ISO_I2C") (class "Default")
      (node (ref "R1014") (pin "2") (pinfunction "2_2") (pintype "passive"))
      (node (ref "R75") (pin "2") (pinfunction "2_2") (pintype "passive"))
      (node (ref "TP1014") (pin "TESTPOINT") (pinfunction "TESTPOINT_TESTPOINT") (pintype "bidirectional"))
      (node (ref "U30") (pin "11") (pinfunction "P1_11") (pintype "bidirectional"))
      (node (ref "U6") (pin "5") (pinfunction "OE_5") (pintype "bidirectional"))
    )
    (net (code "121") (name "MOD6_ISO_POWER") (class "Default")
      (node (ref "R1013") (pin "2") (pinfunction "2_2") (pintype "passive"))
      (node (ref "R74") (pin "2") (pinfunction "2_2") (pintype "passive"))
      (node (ref "S5") (pin "4") (pinfunction "EN_4") (pintype "bidirectional"))
      (node (ref "TP1013") (pin "TESTPOINT") (pinfunction "TESTPOINT_TESTPOINT") (pintype "bidirectional"))
      (node (ref "U30") (pin "10") (pinfunction "P0_10") (pintype "bidirectional"))
    )
    (net (code "122") (name "MOD6_ISO_USB") (class "Default")
      (node (ref "R1015") (pin "2") (pinfunction "2_2") (pintype "passive"))
      (node (ref "R76") (pin "2") (pinfunction "2_2") (pintype "passive"))
      (node (ref "S11") (pin "6") (pinfunction "S_6") (pintype "bidirectional"))
      (node (ref "TP1015") (pin "TESTPOINT") (pinfunction "TESTPOINT_TESTPOINT") (pintype "bidirectional"))
      (node (ref "U24") (pin "8") (pinfunction "~{OE}_8") (pintype "bidirectional"))
      (node (ref "U30") (pin "12") (pinfunction "P2_12") (pintype "bidirectional"))
    )
    (net (code "123") (name "MOD6_OUT") (class "Default")
      (node (ref "J6") (pin "8") (pinfunction "MOD_OUT_8") (pintype "bidirectional"))
      (node (ref "U18") (pin "7") (pinfunction "B1_7") (pintype "bidirectional"))
    )
    (net (code "124") (name "MOD6_PPS") (class "Default")
      (node (ref "J6") (pin "7") (pinfunction "PPS_7") (pintype "bidirectional"))
      (node (ref "U12") (pin "6") (pinfunction "B2_6") (pintype "bidirectional"))
    )
    (net (code "125") (name "MOD6_SCL") (class "Default")
      (node (ref "J6") (pin "5") (pinfunction "SCL_5") (pintype "bidirectional"))
      (node (ref "R42") (pin "2") (pinfunction "2_2") (pintype "passive"))
      (node (ref "U6") (pin "6") (pinfunction "B1_6") (pintype "bidirectional"))
    )
    (net (code "126") (name "MOD6_SDA") (class "Default")
      (node (ref "J6") (pin "6") (pinfunction "SDA_6") (pintype "bidirectional"))
      (node (ref "R41") (pin "2") (pinfunction "2_2") (pintype "passive"))
      (node (ref "U6") (pin "7") (pinfunction "B0_7") (pintype "bidirectional"))
    )
    (net (code "127") (name "MOD6_USB+") (class "Default")
      (node (ref "J6") (pin "11") (pinfunction "USB_D+_11") (pintype "bidirectional"))
      (node (ref "U24") (pin "1") (pinfunction "D1+_1") (pintype "bidirectional"))
    )
    (net (code "128") (name "MOD6_USB-") (class "Default")
      (node (ref "J6") (pin "12") (pinfunction "USB_D-_12") (pintype "bidirectional"))
      (node (ref "U24") (pin "7") (pinfunction "D1-_7") (pintype "bidirectional"))
    )
    (net (code "129") (name "MOD6_USB_VBUS") (class "Default")
      (node (ref "C85") (pin "1") (pinfunction "1_1") (pintype "bidirectional"))
      (node (ref "C99") (pin "1") (pinfunction "1_1") (pintype "bidirectional"))
      (node (ref "J6") (pin "13") (pinfunction "USB_VBUS_13") (pintype "bidirectional"))
      (node (ref "S17") (pin "6") (pinfunction "OUT_6") (pintype "bidirectional"))
      (node (ref "S17") (pin "7") (pinfunction "OUT_7") (pintype "bidirectional"))
    )
    (net (code "130") (name "MOD6_USB_~{EN}") (class "Default")
      (node (ref "S11") (pin "4") (pinfunction "Z_4") (pintype "bidirectional"))
      (node (ref "S17") (pin "4") (pinfunction "~{EN}_4") (pintype "bidirectional"))
    )
    (net (code "131") (name "MOD6_VCCIO") (class "Default")
      (node (ref "C30") (pin "1") (pinfunction "1_1") (pintype "bidirectional"))
      (node (ref "C48") (pin "1") (pinfunction "1_1") (pintype "bidirectional"))
      (node (ref "C60") (pin "1") (pinfunction "1_1") (pintype "bidirectional"))
      (node (ref "J6") (pin "4") (pinfunction "VCCIO_4") (pintype "bidirectional"))
      (node (ref "R41") (pin "1") (pinfunction "1_1") (pintype "passive"))
      (node (ref "R42") (pin "1") (pinfunction "1_1") (pintype "passive"))
      (node (ref "U12") (pin "8") (pinfunction "VCC_B_8") (pintype "bidirectional"))
      (node (ref "U18") (pin "8") (pinfunction "VCC_B_8") (pintype "bidirectional"))
      (node (ref "U6") (pin "8") (pinfunction "VCC_B_8") (pintype "bidirectional"))
    )
    (net (code "132") (name "MOD7_5V") (class "Default")
      (node (ref "C38") (pin "1") (pinfunction "1_1") (pintype "bidirectional"))
      (node (ref "J7") (pin "2") (pinfunction "5V_2") (pintype "bidirectional"))
      (node (ref "S6") (pin "1") (pinfunction "VLOAD_1") (pintype "bidirectional"))
    )
    (net (code "133") (name "MOD7_5V_METERED") (class "Default")
      (node (ref "C86") (pin "1") (pinfunction "1_1") (pintype "bidirectional"))
      (node (ref "C93") (pin "1") (pinfunction "1_1") (pintype "bidirectional"))
      (node (ref "J4") (pin "12") (pinfunction "VCC_MOD7_12") (pintype "power_in"))
      (node (ref "S18") (pin "2") (pinfunction "IN_2") (pintype "bidirectional"))
      (node (ref "S18") (pin "3") (pinfunction "IN_3") (pintype "bidirectional"))
      (node (ref "S6") (pin "3") (pinfunction "VSUPP_3") (pintype "bidirectional"))
      (node (ref "TP20") (pin "TESTPOINT") (pinfunction "TESTPOINT_TESTPOINT") (pintype "bidirectional"))
    )
    (net (code "134") (name "MOD7_D+_HUB-SW") (class "Default")
      (node (ref "D4") (pin "4") (pinfunction "D_4") (pintype "bidirectional"))
      (node (ref "R11") (pin "2") (pinfunction "2_2") (pintype "passive"))
      (node (ref "R60") (pin "2") (pinfunction "2_2") (pintype "passive"))
      (node (ref "U25") (pin "3") (pinfunction "D+_3") (pintype "bidirectional"))
    )
    (net (code "135") (name "MOD7_D-_HUB-SW") (class "Default")
      (node (ref "D4") (pin "2") (pinfunction "C_2") (pintype "bidirectional"))
      (node (ref "R12") (pin "2") (pinfunction "2_2") (pintype "passive"))
      (node (ref "R61") (pin "2") (pinfunction "2_2") (pintype "passive"))
      (node (ref "U25") (pin "5") (pinfunction "D-_5") (pintype "bidirectional"))
    )
    (net (code "136") (name "MOD7_IN") (class "Default")
      (node (ref "J7") (pin "10") (pinfunction "MOD_IN_10") (pintype "bidirectional"))
      (node (ref "U13") (pin "7") (pinfunction "B1_7") (pintype "bidirectional"))
    )
    (net (code "137") (name "MOD7_ISO_I2C") (class "Default")
      (node (ref "LED1017") (pin "A") (pinfunction "ANODE_A") (pintype "bidirectional"))
      (node (ref "R78") (pin "2") (pinfunction "2_2") (pintype "passive"))
      (node (ref "TP1017") (pin "TESTPOINT") (pinfunction "TESTPOINT_TESTPOINT") (pintype "bidirectional"))
      (node (ref "U31") (pin "11") (pinfunction "P1_11") (pintype "bidirectional"))
      (node (ref "U7") (pin "5") (pinfunction "OE_5") (pintype "bidirectional"))
    )
    (net (code "138") (name "MOD7_ISO_POWER") (class "Default")
      (node (ref "LED1016") (pin "A") (pinfunction "ANODE_A") (pintype "bidirectional"))
      (node (ref "R77") (pin "2") (pinfunction "2_2") (pintype "passive"))
      (node (ref "S6") (pin "4") (pinfunction "EN_4") (pintype "bidirectional"))
      (node (ref "TP1016") (pin "TESTPOINT") (pinfunction "TESTPOINT_TESTPOINT") (pintype "bidirectional"))
      (node (ref "U31") (pin "10") (pinfunction "P0_10") (pintype "bidirectional"))
    )
    (net (code "139") (name "MOD7_ISO_USB") (class "Default")
      (node (ref "LED1018") (pin "A") (pinfunction "ANODE_A") (pintype "bidirectional"))
      (node (ref "R79") (pin "2") (pinfunction "2_2") (pintype "passive"))
      (node (ref "S12") (pin "6") (pinfunction "S_6") (pintype "bidirectional"))
      (node (ref "TP1018") (pin "TESTPOINT") (pinfunction "TESTPOINT_TESTPOINT") (pintype "bidirectional"))
      (node (ref "U25") (pin "8") (pinfunction "~{OE}_8") (pintype "bidirectional"))
      (node (ref "U31") (pin "12") (pinfunction "P2_12") (pintype "bidirectional"))
    )
    (net (code "140") (name "MOD7_OUT") (class "Default")
      (node (ref "J7") (pin "8") (pinfunction "MOD_OUT_8") (pintype "bidirectional"))
      (node (ref "U19") (pin "7") (pinfunction "B1_7") (pintype "bidirectional"))
    )
    (net (code "141") (name "MOD7_PPS") (class "Default")
      (node (ref "J7") (pin "7") (pinfunction "PPS_7") (pintype "bidirectional"))
      (node (ref "U13") (pin "6") (pinfunction "B2_6") (pintype "bidirectional"))
    )
    (net (code "142") (name "MOD7_SCL") (class "Default")
      (node (ref "J7") (pin "5") (pinfunction "SCL_5") (pintype "bidirectional"))
      (node (ref "R44") (pin "2") (pinfunction "2_2") (pintype "passive"))
      (node (ref "U7") (pin "6") (pinfunction "B1_6") (pintype "bidirectional"))
    )
    (net (code "143") (name "MOD7_SDA") (class "Default")
      (node (ref "J7") (pin "6") (pinfunction "SDA_6") (pintype "bidirectional"))
      (node (ref "R43") (pin "2") (pinfunction "2_2") (pintype "passive"))
      (node (ref "U7") (pin "7") (pinfunction "B0_7") (pintype "bidirectional"))
    )
    (net (code "144") (name "MOD7_USB+") (class "Default")
      (node (ref "J7") (pin "11") (pinfunction "USB_D+_11") (pintype "bidirectional"))
      (node (ref "U25") (pin "1") (pinfunction "D1+_1") (pintype "bidirectional"))
    )
    (net (code "145") (name "MOD7_USB-") (class "Default")
      (node (ref "J7") (pin "12") (pinfunction "USB_D-_12") (pintype "bidirectional"))
      (node (ref "U25") (pin "7") (pinfunction "D1-_7") (pintype "bidirectional"))
    )
    (net (code "146") (name "MOD7_USB_VBUS") (class "Default")
      (node (ref "C100") (pin "1") (pinfunction "1_1") (pintype "bidirectional"))
      (node (ref "C87") (pin "1") (pinfunction "1_1") (pintype "bidirectional"))
      (node (ref "J7") (pin "13") (pinfunction "USB_VBUS_13") (pintype "bidirectional"))
      (node (ref "S18") (pin "6") (pinfunction "OUT_6") (pintype "bidirectional"))
      (node (ref "S18") (pin "7") (pinfunction "OUT_7") (pintype "bidirectional"))
    )
    (net (code "147") (name "MOD7_USB_~{EN}") (class "Default")
      (node (ref "S12") (pin "4") (pinfunction "Z_4") (pintype "bidirectional"))
      (node (ref "S18") (pin "4") (pinfunction "~{EN}_4") (pintype "bidirectional"))
    )
    (net (code "148") (name "MOD7_VCCIO") (class "Default")
      (node (ref "C32") (pin "1") (pinfunction "1_1") (pintype "bidirectional"))
      (node (ref "C50") (pin "1") (pinfunction "1_1") (pintype "bidirectional"))
      (node (ref "C62") (pin "1") (pinfunction "1_1") (pintype "bidirectional"))
      (node (ref "J7") (pin "4") (pinfunction "VCCIO_4") (pintype "bidirectional"))
      (node (ref "R43") (pin "1") (pinfunction "1_1") (pintype "passive"))
      (node (ref "R44") (pin "1") (pinfunction "1_1") (pintype "passive"))
      (node (ref "U13") (pin "8") (pinfunction "VCC_B_8") (pintype "bidirectional"))
      (node (ref "U19") (pin "8") (pinfunction "VCC_B_8") (pintype "bidirectional"))
      (node (ref "U7") (pin "8") (pinfunction "VCC_B_8") (pintype "bidirectional"))
    )
    (net (code "149") (name "MOD_SCL") (class "Default")
      (node (ref "J3") (pin "24") (pinfunction "MODULES_SCL_24") (pintype "bidirectional"))
      (node (ref "R49") (pin "1") (pinfunction "1_1") (pintype "passive"))
      (node (ref "TP6") (pin "TESTPOINT") (pinfunction "TESTPOINT_TESTPOINT") (pintype "bidirectional"))
      (node (ref "U2") (pin "3") (pinfunction "A1_3") (pintype "bidirectional"))
      (node (ref "U3") (pin "3") (pinfunction "A1_3") (pintype "bidirectional"))
      (node (ref "U4") (pin "3") (pinfunction "A1_3") (pintype "bidirectional"))
      (node (ref "U5") (pin "3") (pinfunction "A1_3") (pintype "bidirectional"))
      (node (ref "U6") (pin "3") (pinfunction "A1_3") (pintype "bidirectional"))
      (node (ref "U7") (pin "3") (pinfunction "A1_3") (pintype "bidirectional"))
    )
    (net (code "150") (name "MOD_SDA") (class "Default")
      (node (ref "J3") (pin "23") (pinfunction "MODULES_SDA_23") (pintype "bidirectional"))
      (node (ref "R48") (pin "1") (pinfunction "1_1") (pintype "passive"))
      (node (ref "TP5") (pin "TESTPOINT") (pinfunction "TESTPOINT_TESTPOINT") (pintype "bidirectional"))
      (node (ref "U2") (pin "2") (pinfunction "A0_2") (pintype "bidirectional"))
      (node (ref "U3") (pin "2") (pinfunction "A0_2") (pintype "bidirectional"))
      (node (ref "U4") (pin "2") (pinfunction "A0_2") (pintype "bidirectional"))
      (node (ref "U5") (pin "2") (pinfunction "A0_2") (pintype "bidirectional"))
      (node (ref "U6") (pin "2") (pinfunction "A0_2") (pintype "bidirectional"))
      (node (ref "U7") (pin "2") (pinfunction "A0_2") (pintype "bidirectional"))
    )
    (net (code "151") (name "Net-(C2-Pad2)") (class "Default")
      (node (ref "C2") (pin "2") (pinfunction "2_2") (pintype "bidirectional"))
      (node (ref "R26") (pin "1") (pinfunction "1_1") (pintype "passive"))
      (node (ref "Y1") (pin "1") (pinfunction "1_1") (pintype "bidirectional"))
    )
    (net (code "152") (name "Net-(LED1001-ANODE)") (class "Default")
      (node (ref "LED1001") (pin "A") (pinfunction "ANODE_A") (pintype "bidirectional"))
      (node (ref "R1001") (pin "1") (pinfunction "1_1") (pintype "passive"))
    )
    (net (code "153") (name "Net-(LED1002-ANODE)") (class "Default")
      (node (ref "LED1002") (pin "A") (pinfunction "ANODE_A") (pintype "bidirectional"))
      (node (ref "R1002") (pin "1") (pinfunction "1_1") (pintype "passive"))
    )
    (net (code "154") (name "Net-(LED1003-ANODE)") (class "Default")
      (node (ref "LED1003") (pin "A") (pinfunction "ANODE_A") (pintype "bidirectional"))
      (node (ref "R1003") (pin "1") (pinfunction "1_1") (pintype "passive"))
    )
    (net (code "155") (name "Net-(LED1004-CATHODE)") (class "Default")
      (node (ref "LED1004") (pin "C") (pinfunction "CATHODE_C") (pintype "bidirectional"))
      (node (ref "R1004") (pin "2") (pinfunction "2_2") (pintype "passive"))
    )
    (net (code "156") (name "Net-(LED1005-CATHODE)") (class "Default")
      (node (ref "LED1005") (pin "C") (pinfunction "CATHODE_C") (pintype "bidirectional"))
      (node (ref "R1005") (pin "2") (pinfunction "2_2") (pintype "passive"))
    )
    (net (code "157") (name "Net-(LED1006-CATHODE)") (class "Default")
      (node (ref "LED1006") (pin "C") (pinfunction "CATHODE_C") (pintype "bidirectional"))
      (node (ref "R1006") (pin "2") (pinfunction "2_2") (pintype "passive"))
    )
    (net (code "158") (name "Net-(LED1007-ANODE)") (class "Default")
      (node (ref "LED1007") (pin "A") (pinfunction "ANODE_A") (pintype "bidirectional"))
      (node (ref "R1007") (pin "1") (pinfunction "1_1") (pintype "passive"))
    )
    (net (code "159") (name "Net-(LED1008-ANODE)") (class "Default")
      (node (ref "LED1008") (pin "A") (pinfunction "ANODE_A") (pintype "bidirectional"))
      (node (ref "R1008") (pin "1") (pinfunction "1_1") (pintype "passive"))
    )
    (net (code "160") (name "Net-(LED1009-ANODE)") (class "Default")
      (node (ref "LED1009") (pin "A") (pinfunction "ANODE_A") (pintype "bidirectional"))
      (node (ref "R1009") (pin "1") (pinfunction "1_1") (pintype "passive"))
    )
    (net (code "161") (name "Net-(LED1010-CATHODE)") (class "Default")
      (node (ref "LED1010") (pin "C") (pinfunction "CATHODE_C") (pintype "bidirectional"))
      (node (ref "R1010") (pin "2") (pinfunction "2_2") (pintype "passive"))
    )
    (net (code "162") (name "Net-(LED1011-CATHODE)") (class "Default")
      (node (ref "LED1011") (pin "C") (pinfunction "CATHODE_C") (pintype "bidirectional"))
      (node (ref "R1011") (pin "2") (pinfunction "2_2") (pintype "passive"))
    )
    (net (code "163") (name "Net-(LED1012-CATHODE)") (class "Default")
      (node (ref "LED1012") (pin "C") (pinfunction "CATHODE_C") (pintype "bidirectional"))
      (node (ref "R1012") (pin "2") (pinfunction "2_2") (pintype "passive"))
    )
    (net (code "164") (name "Net-(LED1013-ANODE)") (class "Default")
      (node (ref "LED1013") (pin "A") (pinfunction "ANODE_A") (pintype "bidirectional"))
      (node (ref "R1013") (pin "1") (pinfunction "1_1") (pintype "passive"))
    )
    (net (code "165") (name "Net-(LED1014-ANODE)") (class "Default")
      (node (ref "LED1014") (pin "A") (pinfunction "ANODE_A") (pintype "bidirectional"))
      (node (ref "R1014") (pin "1") (pinfunction "1_1") (pintype "passive"))
    )
    (net (code "166") (name "Net-(LED1015-ANODE)") (class "Default")
      (node (ref "LED1015") (pin "A") (pinfunction "ANODE_A") (pintype "bidirectional"))
      (node (ref "R1015") (pin "1") (pinfunction "1_1") (pintype "passive"))
    )
    (net (code "167") (name "Net-(LED1016-CATHODE)") (class "Default")
      (node (ref "LED1016") (pin "C") (pinfunction "CATHODE_C") (pintype "bidirectional"))
      (node (ref "R1016") (pin "2") (pinfunction "2_2") (pintype "passive"))
    )
    (net (code "168") (name "Net-(LED1017-CATHODE)") (class "Default")
      (node (ref "LED1017") (pin "C") (pinfunction "CATHODE_C") (pintype "bidirectional"))
      (node (ref "R1017") (pin "2") (pinfunction "2_2") (pintype "passive"))
    )
    (net (code "169") (name "Net-(LED1018-CATHODE)") (class "Default")
      (node (ref "LED1018") (pin "C") (pinfunction "CATHODE_C") (pintype "bidirectional"))
      (node (ref "R1018") (pin "2") (pinfunction "2_2") (pintype "passive"))
    )
    (net (code "170") (name "Net-(U1-DP0PUR)") (class "Default")
      (node (ref "R25") (pin "2") (pinfunction "2_2") (pintype "passive"))
      (node (ref "U1") (pin "2") (pinfunction "DP0PUR_2") (pintype "bidirectional"))
    )
    (net (code "171") (name "Net-(U1-XTAL1)") (class "Default")
      (node (ref "C1") (pin "2") (pinfunction "2_2") (pintype "bidirectional"))
      (node (ref "U1") (pin "45") (pinfunction "XTAL1_45") (pintype "bidirectional"))
      (node (ref "Y1") (pin "3") (pinfunction "2_3") (pintype "bidirectional"))
    )
    (net (code "172") (name "Net-(U1-XTAL2)") (class "Default")
      (node (ref "R26") (pin "2") (pinfunction "2_2") (pintype "passive"))
      (node (ref "U1") (pin "44") (pinfunction "XTAL2_44") (pintype "bidirectional"))
    )
    (net (code "173") (name "Net-(U20-D2+)") (class "Default")
      (node (ref "R13") (pin "1") (pinfunction "1_1") (pintype "passive"))
      (node (ref "U20") (pin "2") (pinfunction "D2+_2") (pintype "bidirectional"))
    )
    (net (code "174") (name "Net-(U20-D2-)") (class "Default")
      (node (ref "R14") (pin "1") (pinfunction "1_1") (pintype "passive"))
      (node (ref "U20") (pin "6") (pinfunction "D2-_6") (pintype "bidirectional"))
    )
    (net (code "175") (name "Net-(U21-D2+)") (class "Default")
      (node (ref "R15") (pin "1") (pinfunction "1_1") (pintype "passive"))
      (node (ref "U21") (pin "2") (pinfunction "D2+_2") (pintype "bidirectional"))
    )
    (net (code "176") (name "Net-(U21-D2-)") (class "Default")
      (node (ref "R16") (pin "1") (pinfunction "1_1") (pintype "passive"))
      (node (ref "U21") (pin "6") (pinfunction "D2-_6") (pintype "bidirectional"))
    )
    (net (code "177") (name "Net-(U22-D2+)") (class "Default")
      (node (ref "R17") (pin "1") (pinfunction "1_1") (pintype "passive"))
      (node (ref "U22") (pin "2") (pinfunction "D2+_2") (pintype "bidirectional"))
    )
    (net (code "178") (name "Net-(U22-D2-)") (class "Default")
      (node (ref "R18") (pin "1") (pinfunction "1_1") (pintype "passive"))
      (node (ref "U22") (pin "6") (pinfunction "D2-_6") (pintype "bidirectional"))
    )
    (net (code "179") (name "Net-(U23-D2+)") (class "Default")
      (node (ref "R19") (pin "1") (pinfunction "1_1") (pintype "passive"))
      (node (ref "U23") (pin "2") (pinfunction "D2+_2") (pintype "bidirectional"))
    )
    (net (code "180") (name "Net-(U23-D2-)") (class "Default")
      (node (ref "R20") (pin "1") (pinfunction "1_1") (pintype "passive"))
      (node (ref "U23") (pin "6") (pinfunction "D2-_6") (pintype "bidirectional"))
    )
    (net (code "181") (name "Net-(U24-D2+)") (class "Default")
      (node (ref "R21") (pin "1") (pinfunction "1_1") (pintype "passive"))
      (node (ref "U24") (pin "2") (pinfunction "D2+_2") (pintype "bidirectional"))
    )
    (net (code "182") (name "Net-(U24-D2-)") (class "Default")
      (node (ref "R22") (pin "1") (pinfunction "1_1") (pintype "passive"))
      (node (ref "U24") (pin "6") (pinfunction "D2-_6") (pintype "bidirectional"))
    )
    (net (code "183") (name "Net-(U25-D2+)") (class "Default")
      (node (ref "R23") (pin "1") (pinfunction "1_1") (pintype "passive"))
      (node (ref "U25") (pin "2") (pinfunction "D2+_2") (pintype "bidirectional"))
    )
    (net (code "184") (name "Net-(U25-D2-)") (class "Default")
      (node (ref "R24") (pin "1") (pinfunction "1_1") (pintype "passive"))
      (node (ref "U25") (pin "6") (pinfunction "D2-_6") (pintype "bidirectional"))
    )
    (net (code "185") (name "PPS") (class "Default")
      (node (ref "J3") (pin "25") (pinfunction "PPS_25") (pintype "bidirectional"))
      (node (ref "TP43") (pin "TESTPOINT") (pinfunction "TESTPOINT_TESTPOINT") (pintype "bidirectional"))
      (node (ref "U10") (pin "3") (pinfunction "A2_3") (pintype "bidirectional"))
      (node (ref "U11") (pin "3") (pinfunction "A2_3") (pintype "bidirectional"))
      (node (ref "U12") (pin "3") (pinfunction "A2_3") (pintype "bidirectional"))
      (node (ref "U13") (pin "3") (pinfunction "A2_3") (pintype "bidirectional"))
      (node (ref "U8") (pin "3") (pinfunction "A2_3") (pintype "bidirectional"))
      (node (ref "U9") (pin "3") (pinfunction "A2_3") (pintype "bidirectional"))
    )
    (net (code "186") (name "SMBCLK") (class "Default")
      (node (ref "J3") (pin "5") (pinfunction "SMBCLK_5") (pintype "bidirectional"))
      (node (ref "J4") (pin "5") (pinfunction "SMBCLK_5") (pintype "open_collector"))
      (node (ref "R46") (pin "1") (pinfunction "1_1") (pintype "passive"))
      (node (ref "TP2") (pin "TESTPOINT") (pinfunction "TESTPOINT_TESTPOINT") (pintype "bidirectional"))
      (node (ref "U26") (pin "1") (pinfunction "SCL_1") (pintype "bidirectional"))
      (node (ref "U27") (pin "1") (pinfunction "SCL_1") (pintype "bidirectional"))
      (node (ref "U28") (pin "1") (pinfunction "SCL_1") (pintype "bidirectional"))
      (node (ref "U29") (pin "1") (pinfunction "SCL_1") (pintype "bidirectional"))
      (node (ref "U30") (pin "1") (pinfunction "SCL_1") (pintype "bidirectional"))
      (node (ref "U31") (pin "1") (pinfunction "SCL_1") (pintype "bidirectional"))
    )
    (net (code "187") (name "SMBDATA") (class "Default")
      (node (ref "J3") (pin "3") (pinfunction "SMBDATA_3") (pintype "bidirectional"))
      (node (ref "J4") (pin "3") (pinfunction "SMBDATA_3") (pintype "open_collector"))
      (node (ref "R45") (pin "1") (pinfunction "1_1") (pintype "passive"))
      (node (ref "TP1") (pin "TESTPOINT") (pinfunction "TESTPOINT_TESTPOINT") (pintype "bidirectional"))
      (node (ref "U26") (pin "2") (pinfunction "SDA_2") (pintype "bidirectional"))
      (node (ref "U27") (pin "2") (pinfunction "SDA_2") (pintype "bidirectional"))
      (node (ref "U28") (pin "2") (pinfunction "SDA_2") (pintype "bidirectional"))
      (node (ref "U29") (pin "2") (pinfunction "SDA_2") (pintype "bidirectional"))
      (node (ref "U30") (pin "2") (pinfunction "SDA_2") (pintype "bidirectional"))
      (node (ref "U31") (pin "2") (pinfunction "SDA_2") (pintype "bidirectional"))
    )
    (net (code "188") (name "USB_SUSPEND_STATUS") (class "Default")
      (node (ref "TP42") (pin "TESTPOINT") (pinfunction "TESTPOINT_TESTPOINT") (pintype "bidirectional"))
      (node (ref "U1") (pin "1") (pinfunction "SUSPND_1") (pintype "bidirectional"))
    )
    (net (code "189") (name "VBATT+") (class "Default")
      (node (ref "J4") (pin "17") (pinfunction "VBATT+_17") (pintype "power_in"))
      (node (ref "J9") (pin "1") (pinfunction "1_1") (pintype "bidirectional"))
      (node (ref "TP13") (pin "TESTPOINT") (pinfunction "TESTPOINT_TESTPOINT") (pintype "bidirectional"))
    )
    (net (code "190") (name "VBATT-") (class "Default")
      (node (ref "J4") (pin "18") (pinfunction "VBATT-_18") (pintype "power_in"))
      (node (ref "J9") (pin "2") (pinfunction "2_2") (pintype "bidirectional"))
      (node (ref "TP14") (pin "TESTPOINT") (pinfunction "TESTPOINT_TESTPOINT") (pintype "bidirectional"))
    )
    (net (code "191") (name "VCC_BACKPLANE") (class "Default")
      (node (ref "C15") (pin "1") (pinfunction "1_1") (pintype "bidirectional"))
      (node (ref "C16") (pin "1") (pinfunction "1_1") (pintype "bidirectional"))
      (node (ref "C17") (pin "1") (pinfunction "1_1") (pintype "bidirectional"))
      (node (ref "C18") (pin "1") (pinfunction "1_1") (pintype "bidirectional"))
      (node (ref "C19") (pin "1") (pinfunction "1_1") (pintype "bidirectional"))
      (node (ref "C20") (pin "1") (pinfunction "1_1") (pintype "bidirectional"))
      (node (ref "C21") (pin "1") (pinfunction "1_1") (pintype "bidirectional"))
      (node (ref "C23") (pin "1") (pinfunction "1_1") (pintype "bidirectional"))
      (node (ref "C25") (pin "1") (pinfunction "1_1") (pintype "bidirectional"))
      (node (ref "C27") (pin "1") (pinfunction "1_1") (pintype "bidirectional"))
      (node (ref "C29") (pin "1") (pinfunction "1_1") (pintype "bidirectional"))
      (node (ref "C31") (pin "1") (pinfunction "1_1") (pintype "bidirectional"))
      (node (ref "C39") (pin "1") (pinfunction "1_1") (pintype "bidirectional"))
      (node (ref "C41") (pin "1") (pinfunction "1_1") (pintype "bidirectional"))
      (node (ref "C43") (pin "1") (pinfunction "1_1") (pintype "bidirectional"))
      (node (ref "C45") (pin "1") (pinfunction "1_1") (pintype "bidirectional"))
      (node (ref "C47") (pin "1") (pinfunction "1_1") (pintype "bidirectional"))
      (node (ref "C49") (pin "1") (pinfunction "1_1") (pintype "bidirectional"))
      (node (ref "C51") (pin "1") (pinfunction "1_1") (pintype "bidirectional"))
      (node (ref "C53") (pin "1") (pinfunction "1_1") (pintype "bidirectional"))
      (node (ref "C55") (pin "1") (pinfunction "1_1") (pintype "bidirectional"))
      (node (ref "C57") (pin "1") (pinfunction "1_1") (pintype "bidirectional"))
      (node (ref "C59") (pin "1") (pinfunction "1_1") (pintype "bidirectional"))
      (node (ref "C61") (pin "1") (pinfunction "1_1") (pintype "bidirectional"))
      (node (ref "C63") (pin "2") (pinfunction "2_2") (pintype "bidirectional"))
      (node (ref "C64") (pin "2") (pinfunction "2_2") (pintype "bidirectional"))
      (node (ref "C65") (pin "2") (pinfunction "2_2") (pintype "bidirectional"))
      (node (ref "C66") (pin "2") (pinfunction "2_2") (pintype "bidirectional"))
      (node (ref "C67") (pin "2") (pinfunction "2_2") (pintype "bidirectional"))
      (node (ref "C68") (pin "2") (pinfunction "2_2") (pintype "bidirectional"))
      (node (ref "C69") (pin "2") (pinfunction "2_2") (pintype "bidirectional"))
      (node (ref "C70") (pin "1") (pinfunction "1_1") (pintype "bidirectional"))
      (node (ref "C71") (pin "1") (pinfunction "1_1") (pintype "bidirectional"))
      (node (ref "C72") (pin "1") (pinfunction "1_1") (pintype "bidirectional"))
      (node (ref "C73") (pin "1") (pinfunction "1_1") (pintype "bidirectional"))
      (node (ref "C74") (pin "1") (pinfunction "1_1") (pintype "bidirectional"))
      (node (ref "C75") (pin "1") (pinfunction "1_1") (pintype "bidirectional"))
      (node (ref "C94") (pin "2") (pinfunction "2_2") (pintype "bidirectional"))
      (node (ref "J4") (pin "13") (pinfunction "VCC_BACKPLANE_13") (pintype "power_in"))
      (node (ref "R27") (pin "2") (pinfunction "2_2") (pintype "passive"))
      (node (ref "R28") (pin "2") (pinfunction "2_2") (pintype "passive"))
      (node (ref "R29") (pin "2") (pinfunction "2_2") (pintype "passive"))
      (node (ref "R30") (pin "2") (pinfunction "2_2") (pintype "passive"))
      (node (ref "R31") (pin "2") (pinfunction "2_2") (pintype "passive"))
      (node (ref "R32") (pin "2") (pinfunction "2_2") (pintype "passive"))
      (node (ref "R45") (pin "2") (pinfunction "2_2") (pintype "passive"))
      (node (ref "R46") (pin "2") (pinfunction "2_2") (pintype "passive"))
      (node (ref "R47") (pin "2") (pinfunction "2_2") (pintype "passive"))
      (node (ref "R48") (pin "2") (pinfunction "2_2") (pintype "passive"))
      (node (ref "R49") (pin "2") (pinfunction "2_2") (pintype "passive"))
      (node (ref "S10") (pin "3") (pinfunction "I0_3") (pintype "bidirectional"))
      (node (ref "S10") (pin "5") (pinfunction "VCC_5") (pintype "bidirectional"))
      (node (ref "S11") (pin "3") (pinfunction "I0_3") (pintype "bidirectional"))
      (node (ref "S11") (pin "5") (pinfunction "VCC_5") (pintype "bidirectional"))
      (node (ref "S12") (pin "3") (pinfunction "I0_3") (pintype "bidirectional"))
      (node (ref "S12") (pin "5") (pinfunction "VCC_5") (pintype "bidirectional"))
      (node (ref "S7") (pin "3") (pinfunction "I0_3") (pintype "bidirectional"))
      (node (ref "S7") (pin "5") (pinfunction "VCC_5") (pintype "bidirectional"))
      (node (ref "S8") (pin "3") (pinfunction "I0_3") (pintype "bidirectional"))
      (node (ref "S8") (pin "5") (pinfunction "VCC_5") (pintype "bidirectional"))
      (node (ref "S9") (pin "3") (pinfunction "I0_3") (pintype "bidirectional"))
      (node (ref "S9") (pin "5") (pinfunction "VCC_5") (pintype "bidirectional"))
      (node (ref "TP23") (pin "TESTPOINT") (pinfunction "TESTPOINT_TESTPOINT") (pintype "bidirectional"))
      (node (ref "TP8") (pin "TESTPOINT") (pinfunction "TESTPOINT_TESTPOINT") (pintype "bidirectional"))
      (node (ref "U1") (pin "46") (pinfunction "VCC_46") (pintype "bidirectional"))
      (node (ref "U1") (pin "47") (pinfunction "~{EXTMEM}_47") (pintype "bidirectional"))
      (node (ref "U1") (pin "8") (pinfunction "EEDATA/~{GANGED}_8") (pintype "bidirectional"))
      (node (ref "U1") (pin "9") (pinfunction "VCC_9") (pintype "bidirectional"))
      (node (ref "U10") (pin "1") (pinfunction "VCC_A_1") (pintype "bidirectional"))
      (node (ref "U10") (pin "5") (pinfunction "DIR_5") (pintype "bidirectional"))
      (node (ref "U11") (pin "1") (pinfunction "VCC_A_1") (pintype "bidirectional"))
      (node (ref "U11") (pin "5") (pinfunction "DIR_5") (pintype "bidirectional"))
      (node (ref "U12") (pin "1") (pinfunction "VCC_A_1") (pintype "bidirectional"))
      (node (ref "U12") (pin "5") (pinfunction "DIR_5") (pintype "bidirectional"))
      (node (ref "U13") (pin "1") (pinfunction "VCC_A_1") (pintype "bidirectional"))
      (node (ref "U13") (pin "5") (pinfunction "DIR_5") (pintype "bidirectional"))
      (node (ref "U14") (pin "1") (pinfunction "VCC_A_1") (pintype "bidirectional"))
      (node (ref "U15") (pin "1") (pinfunction "VCC_A_1") (pintype "bidirectional"))
      (node (ref "U16") (pin "1") (pinfunction "VCC_A_1") (pintype "bidirectional"))
      (node (ref "U17") (pin "1") (pinfunction "VCC_A_1") (pintype "bidirectional"))
      (node (ref "U18") (pin "1") (pinfunction "VCC_A_1") (pintype "bidirectional"))
      (node (ref "U19") (pin "1") (pinfunction "VCC_A_1") (pintype "bidirectional"))
      (node (ref "U2") (pin "1") (pinfunction "VCC_A_1") (pintype "bidirectional"))
      (node (ref "U20") (pin "9") (pinfunction "VCC_9") (pintype "bidirectional"))
      (node (ref "U21") (pin "9") (pinfunction "VCC_9") (pintype "bidirectional"))
      (node (ref "U22") (pin "9") (pinfunction "VCC_9") (pintype "bidirectional"))
      (node (ref "U23") (pin "9") (pinfunction "VCC_9") (pintype "bidirectional"))
      (node (ref "U24") (pin "9") (pinfunction "VCC_9") (pintype "bidirectional"))
      (node (ref "U25") (pin "9") (pinfunction "VCC_9") (pintype "bidirectional"))
      (node (ref "U26") (pin "18") (pinfunction "VCC_18") (pintype "bidirectional"))
      (node (ref "U27") (pin "18") (pinfunction "VCC_18") (pintype "bidirectional"))
      (node (ref "U27") (pin "5") (pinfunction "A0_5") (pintype "bidirectional"))
      (node (ref "U28") (pin "18") (pinfunction "VCC_18") (pintype "bidirectional"))
      (node (ref "U28") (pin "4") (pinfunction "A1_4") (pintype "bidirectional"))
      (node (ref "U29") (pin "18") (pinfunction "VCC_18") (pintype "bidirectional"))
      (node (ref "U29") (pin "3") (pinfunction "A2_3") (pintype "bidirectional"))
      (node (ref "U29") (pin "5") (pinfunction "A0_5") (pintype "bidirectional"))
      (node (ref "U3") (pin "1") (pinfunction "VCC_A_1") (pintype "bidirectional"))
      (node (ref "U30") (pin "18") (pinfunction "VCC_18") (pintype "bidirectional"))
      (node (ref "U30") (pin "3") (pinfunction "A2_3") (pintype "bidirectional"))
      (node (ref "U30") (pin "4") (pinfunction "A1_4") (pintype "bidirectional"))
      (node (ref "U31") (pin "18") (pinfunction "VCC_18") (pintype "bidirectional"))
      (node (ref "U31") (pin "3") (pinfunction "A2_3") (pintype "bidirectional"))
      (node (ref "U31") (pin "4") (pinfunction "A1_4") (pintype "bidirectional"))
      (node (ref "U31") (pin "5") (pinfunction "A0_5") (pintype "bidirectional"))
      (node (ref "U4") (pin "1") (pinfunction "VCC_A_1") (pintype "bidirectional"))
      (node (ref "U5") (pin "1") (pinfunction "VCC_A_1") (pintype "bidirectional"))
      (node (ref "U6") (pin "1") (pinfunction "VCC_A_1") (pintype "bidirectional"))
      (node (ref "U7") (pin "1") (pinfunction "VCC_A_1") (pintype "bidirectional"))
      (node (ref "U8") (pin "1") (pinfunction "VCC_A_1") (pintype "bidirectional"))
      (node (ref "U8") (pin "5") (pinfunction "DIR_5") (pintype "bidirectional"))
      (node (ref "U9") (pin "1") (pinfunction "VCC_A_1") (pintype "bidirectional"))
      (node (ref "U9") (pin "5") (pinfunction "DIR_5") (pintype "bidirectional"))
    )
    (net (code "192") (name "VCC_CONTROLLER") (class "Default")
      (node (ref "J3") (pin "2") (pinfunction "VCC_CONTROLLER_2") (pintype "bidirectional"))
      (node (ref "J4") (pin "2") (pinfunction "VCC_CONTROLLER_2") (pintype "power_in"))
      (node (ref "TP21") (pin "TESTPOINT") (pinfunction "TESTPOINT_TESTPOINT") (pintype "bidirectional"))
    )
    (net (code "193") (name "VCC_LINUX") (class "Default")
      (node (ref "J3") (pin "4") (pinfunction "VCC_LINUX_4") (pintype "bidirectional"))
      (node (ref "J4") (pin "4") (pinfunction "VCC_LINUX_4") (pintype "power_in"))
      (node (ref "TP22") (pin "TESTPOINT") (pinfunction "TESTPOINT_TESTPOINT") (pintype "bidirectional"))
    )
    (net (code "194") (name "VSOL+") (class "Default")
      (node (ref "J4") (pin "19") (pinfunction "VSOL+_19") (pintype "power_in"))
      (node (ref "J8") (pin "1") (pinfunction "1_1") (pintype "bidirectional"))
      (node (ref "TP11") (pin "TESTPOINT") (pinfunction "TESTPOINT_TESTPOINT") (pintype "bidirectional"))
    )
    (net (code "195") (name "VSOL-") (class "Default")
      (node (ref "J4") (pin "20") (pinfunction "VSOL-_20") (pintype "power_in"))
      (node (ref "J8") (pin "2") (pinfunction "2_2") (pintype "bidirectional"))
      (node (ref "TP12") (pin "TESTPOINT") (pinfunction "TESTPOINT_TESTPOINT") (pintype "bidirectional"))
    )
    (net (code "196") (name "unconnected-(D2-C-Pad2)") (class "Default")
      (node (ref "D2") (pin "2") (pinfunction "C_2") (pintype "bidirectional"))
    )
    (net (code "197") (name "unconnected-(D2-D-Pad4)") (class "Default")
      (node (ref "D2") (pin "4") (pinfunction "D_4") (pintype "bidirectional"))
    )
    (net (code "198") (name "unconnected-(D3-A-Pad8)") (class "Default")
      (node (ref "D3") (pin "8") (pinfunction "A_8") (pintype "bidirectional"))
    )
    (net (code "199") (name "unconnected-(D3-B-Pad6)") (class "Default")
      (node (ref "D3") (pin "6") (pinfunction "B_6") (pintype "bidirectional"))
    )
    (net (code "200") (name "unconnected-(U1-EECLK-Pad7)") (class "Default")
      (node (ref "U1") (pin "7") (pinfunction "EECLK_7") (pintype "bidirectional"))
    )
    (net (code "201") (name "unconnected-(U14-A2-Pad3)") (class "Default")
      (node (ref "U14") (pin "3") (pinfunction "A2_3") (pintype "bidirectional"))
    )
    (net (code "202") (name "unconnected-(U14-B2-Pad6)") (class "Default")
      (node (ref "U14") (pin "6") (pinfunction "B2_6") (pintype "bidirectional"))
    )
    (net (code "203") (name "unconnected-(U15-A2-Pad3)") (class "Default")
      (node (ref "U15") (pin "3") (pinfunction "A2_3") (pintype "bidirectional"))
    )
    (net (code "204") (name "unconnected-(U15-B2-Pad6)") (class "Default")
      (node (ref "U15") (pin "6") (pinfunction "B2_6") (pintype "bidirectional"))
    )
    (net (code "205") (name "unconnected-(U16-A2-Pad3)") (class "Default")
      (node (ref "U16") (pin "3") (pinfunction "A2_3") (pintype "bidirectional"))
    )
    (net (code "206") (name "unconnected-(U16-B2-Pad6)") (class "Default")
      (node (ref "U16") (pin "6") (pinfunction "B2_6") (pintype "bidirectional"))
    )
    (net (code "207") (name "unconnected-(U17-A2-Pad3)") (class "Default")
      (node (ref "U17") (pin "3") (pinfunction "A2_3") (pintype "bidirectional"))
    )
    (net (code "208") (name "unconnected-(U17-B2-Pad6)") (class "Default")
      (node (ref "U17") (pin "6") (pinfunction "B2_6") (pintype "bidirectional"))
    )
    (net (code "209") (name "unconnected-(U18-A2-Pad3)") (class "Default")
      (node (ref "U18") (pin "3") (pinfunction "A2_3") (pintype "bidirectional"))
    )
    (net (code "210") (name "unconnected-(U18-B2-Pad6)") (class "Default")
      (node (ref "U18") (pin "6") (pinfunction "B2_6") (pintype "bidirectional"))
    )
    (net (code "211") (name "unconnected-(U18-DIR-Pad5)") (class "Default")
      (node (ref "U18") (pin "5") (pinfunction "DIR_5") (pintype "bidirectional"))
    )
    (net (code "212") (name "unconnected-(U19-A2-Pad3)") (class "Default")
      (node (ref "U19") (pin "3") (pinfunction "A2_3") (pintype "bidirectional"))
    )
    (net (code "213") (name "unconnected-(U19-B2-Pad6)") (class "Default")
      (node (ref "U19") (pin "6") (pinfunction "B2_6") (pintype "bidirectional"))
    )
    (net (code "214") (name "unconnected-(U26-INT-Pad8)") (class "Default")
      (node (ref "U26") (pin "8") (pinfunction "INT_8") (pintype "bidirectional"))
    )
    (net (code "215") (name "unconnected-(U26-P3-Pad13)") (class "Default")
      (node (ref "U26") (pin "13") (pinfunction "P3_13") (pintype "bidirectional"))
    )
    (net (code "216") (name "unconnected-(U26-P4-Pad14)") (class "Default")
      (node (ref "U26") (pin "14") (pinfunction "P4_14") (pintype "bidirectional"))
    )
    (net (code "217") (name "unconnected-(U26-P5-Pad15)") (class "Default")
      (node (ref "U26") (pin "15") (pinfunction "P5_15") (pintype "bidirectional"))
    )
    (net (code "218") (name "unconnected-(U26-P6-Pad16)") (class "Default")
      (node (ref "U26") (pin "16") (pinfunction "P6_16") (pintype "bidirectional"))
    )
    (net (code "219") (name "unconnected-(U26-P7-Pad17)") (class "Default")
      (node (ref "U26") (pin "17") (pinfunction "P7_17") (pintype "bidirectional"))
    )
    (net (code "220") (name "unconnected-(U27-INT-Pad8)") (class "Default")
      (node (ref "U27") (pin "8") (pinfunction "INT_8") (pintype "bidirectional"))
    )
    (net (code "221") (name "unconnected-(U27-P3-Pad13)") (class "Default")
      (node (ref "U27") (pin "13") (pinfunction "P3_13") (pintype "bidirectional"))
    )
    (net (code "222") (name "unconnected-(U27-P4-Pad14)") (class "Default")
      (node (ref "U27") (pin "14") (pinfunction "P4_14") (pintype "bidirectional"))
    )
    (net (code "223") (name "unconnected-(U27-P5-Pad15)") (class "Default")
      (node (ref "U27") (pin "15") (pinfunction "P5_15") (pintype "bidirectional"))
    )
    (net (code "224") (name "unconnected-(U27-P6-Pad16)") (class "Default")
      (node (ref "U27") (pin "16") (pinfunction "P6_16") (pintype "bidirectional"))
    )
    (net (code "225") (name "unconnected-(U27-P7-Pad17)") (class "Default")
      (node (ref "U27") (pin "17") (pinfunction "P7_17") (pintype "bidirectional"))
    )
    (net (code "226") (name "unconnected-(U28-INT-Pad8)") (class "Default")
      (node (ref "U28") (pin "8") (pinfunction "INT_8") (pintype "bidirectional"))
    )
    (net (code "227") (name "unconnected-(U28-P3-Pad13)") (class "Default")
      (node (ref "U28") (pin "13") (pinfunction "P3_13") (pintype "bidirectional"))
    )
    (net (code "228") (name "unconnected-(U28-P4-Pad14)") (class "Default")
      (node (ref "U28") (pin "14") (pinfunction "P4_14") (pintype "bidirectional"))
    )
    (net (code "229") (name "unconnected-(U28-P5-Pad15)") (class "Default")
      (node (ref "U28") (pin "15") (pinfunction "P5_15") (pintype "bidirectional"))
    )
    (net (code "230") (name "unconnected-(U28-P6-Pad16)") (class "Default")
      (node (ref "U28") (pin "16") (pinfunction "P6_16") (pintype "bidirectional"))
    )
    (net (code "231") (name "unconnected-(U28-P7-Pad17)") (class "Default")
      (node (ref "U28") (pin "17") (pinfunction "P7_17") (pintype "bidirectional"))
    )
    (net (code "232") (name "unconnected-(U29-INT-Pad8)") (class "Default")
      (node (ref "U29") (pin "8") (pinfunction "INT_8") (pintype "bidirectional"))
    )
    (net (code "233") (name "unconnected-(U29-P3-Pad13)") (class "Default")
      (node (ref "U29") (pin "13") (pinfunction "P3_13") (pintype "bidirectional"))
    )
    (net (code "234") (name "unconnected-(U29-P4-Pad14)") (class "Default")
      (node (ref "U29") (pin "14") (pinfunction "P4_14") (pintype "bidirectional"))
    )
    (net (code "235") (name "unconnected-(U29-P5-Pad15)") (class "Default")
      (node (ref "U29") (pin "15") (pinfunction "P5_15") (pintype "bidirectional"))
    )
    (net (code "236") (name "unconnected-(U29-P6-Pad16)") (class "Default")
      (node (ref "U29") (pin "16") (pinfunction "P6_16") (pintype "bidirectional"))
    )
    (net (code "237") (name "unconnected-(U29-P7-Pad17)") (class "Default")
      (node (ref "U29") (pin "17") (pinfunction "P7_17") (pintype "bidirectional"))
    )
    (net (code "238") (name "unconnected-(U30-INT-Pad8)") (class "Default")
      (node (ref "U30") (pin "8") (pinfunction "INT_8") (pintype "bidirectional"))
    )
    (net (code "239") (name "unconnected-(U30-P3-Pad13)") (class "Default")
      (node (ref "U30") (pin "13") (pinfunction "P3_13") (pintype "bidirectional"))
    )
    (net (code "240") (name "unconnected-(U30-P4-Pad14)") (class "Default")
      (node (ref "U30") (pin "14") (pinfunction "P4_14") (pintype "bidirectional"))
    )
    (net (code "241") (name "unconnected-(U30-P5-Pad15)") (class "Default")
      (node (ref "U30") (pin "15") (pinfunction "P5_15") (pintype "bidirectional"))
    )
    (net (code "242") (name "unconnected-(U30-P6-Pad16)") (class "Default")
      (node (ref "U30") (pin "16") (pinfunction "P6_16") (pintype "bidirectional"))
    )
    (net (code "243") (name "unconnected-(U30-P7-Pad17)") (class "Default")
      (node (ref "U30") (pin "17") (pinfunction "P7_17") (pintype "bidirectional"))
    )
    (net (code "244") (name "unconnected-(U31-INT-Pad8)") (class "Default")
      (node (ref "U31") (pin "8") (pinfunction "INT_8") (pintype "bidirectional"))
    )
    (net (code "245") (name "unconnected-(U31-P3-Pad13)") (class "Default")
      (node (ref "U31") (pin "13") (pinfunction "P3_13") (pintype "bidirectional"))
    )
    (net (code "246") (name "unconnected-(U31-P4-Pad14)") (class "Default")
      (node (ref "U31") (pin "14") (pinfunction "P4_14") (pintype "bidirectional"))
    )
    (net (code "247") (name "unconnected-(U31-P5-Pad15)") (class "Default")
      (node (ref "U31") (pin "15") (pinfunction "P5_15") (pintype "bidirectional"))
    )
    (net (code "248") (name "unconnected-(U31-P6-Pad16)") (class "Default")
      (node (ref "U31") (pin "16") (pinfunction "P6_16") (pintype "bidirectional"))
    )
    (net (code "249") (name "unconnected-(U31-P7-Pad17)") (class "Default")
      (node (ref "U31") (pin "17") (pinfunction "P7_17") (pintype "bidirectional"))
    )
    (net (code "250") (name "~{BACKPLANE_RESET}") (class "Default")
      (node (ref "J3") (pin "22") (pinfunction "~{BACKPLANE_RESET}_22") (pintype "bidirectional"))
      (node (ref "R80") (pin "2") (pinfunction "2_2") (pintype "passive"))
      (node (ref "TP9") (pin "TESTPOINT") (pinfunction "TESTPOINT_TESTPOINT") (pintype "bidirectional"))
      (node (ref "U1") (pin "6") (pinfunction "~{RESET}_6") (pintype "bidirectional"))
      (node (ref "U26") (pin "6") (pinfunction "~{RESET}_6") (pintype "bidirectional"))
      (node (ref "U27") (pin "6") (pinfunction "~{RESET}_6") (pintype "bidirectional"))
      (node (ref "U28") (pin "6") (pinfunction "~{RESET}_6") (pintype "bidirectional"))
      (node (ref "U29") (pin "6") (pinfunction "~{RESET}_6") (pintype "bidirectional"))
      (node (ref "U30") (pin "6") (pinfunction "~{RESET}_6") (pintype "bidirectional"))
      (node (ref "U31") (pin "6") (pinfunction "~{RESET}_6") (pintype "bidirectional"))
    )
    (net (code "251") (name "~{SMBALERT}") (class "Default")
      (node (ref "J3") (pin "6") (pinfunction "~{SMBALERT}_6") (pintype "bidirectional"))
      (node (ref "J4") (pin "6") (pinfunction "~{SMBALERT}_6") (pintype "bidirectional"))
      (node (ref "R47") (pin "1") (pinfunction "1_1") (pintype "passive"))
      (node (ref "TP3") (pin "TESTPOINT") (pinfunction "TESTPOINT_TESTPOINT") (pintype "bidirectional"))
    )
  )
)
